# 780-00040_Rev1_Pg1_Super_Sniffer.net
KiCad netlist of a schematic drawn in Altium Designer
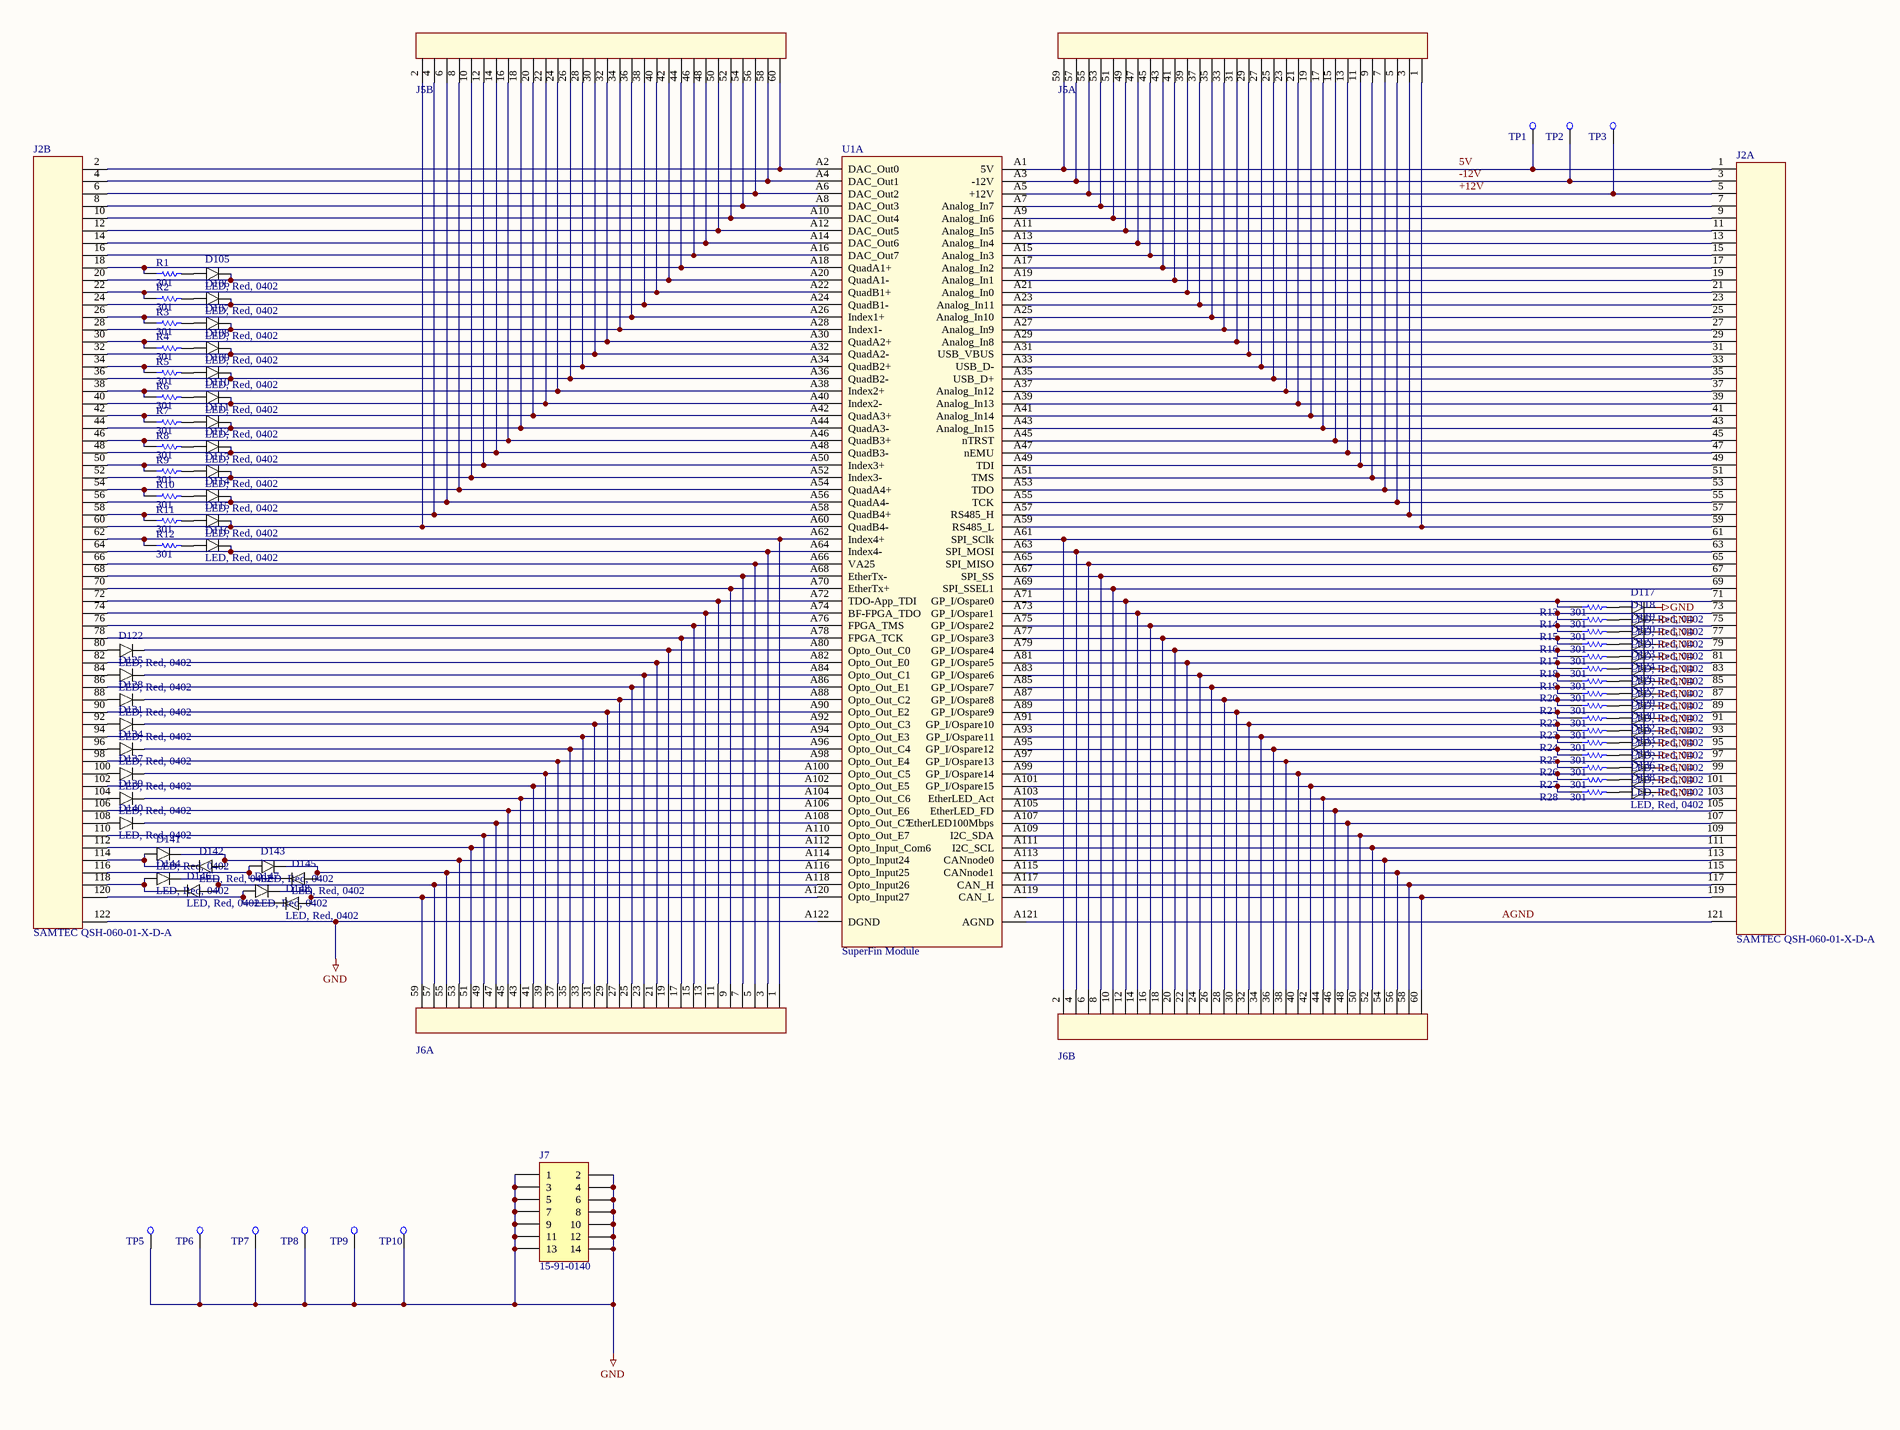
[diagram p0: 780-00040, Rev1, Pg1, Super Sniffer.SchDoc, left]
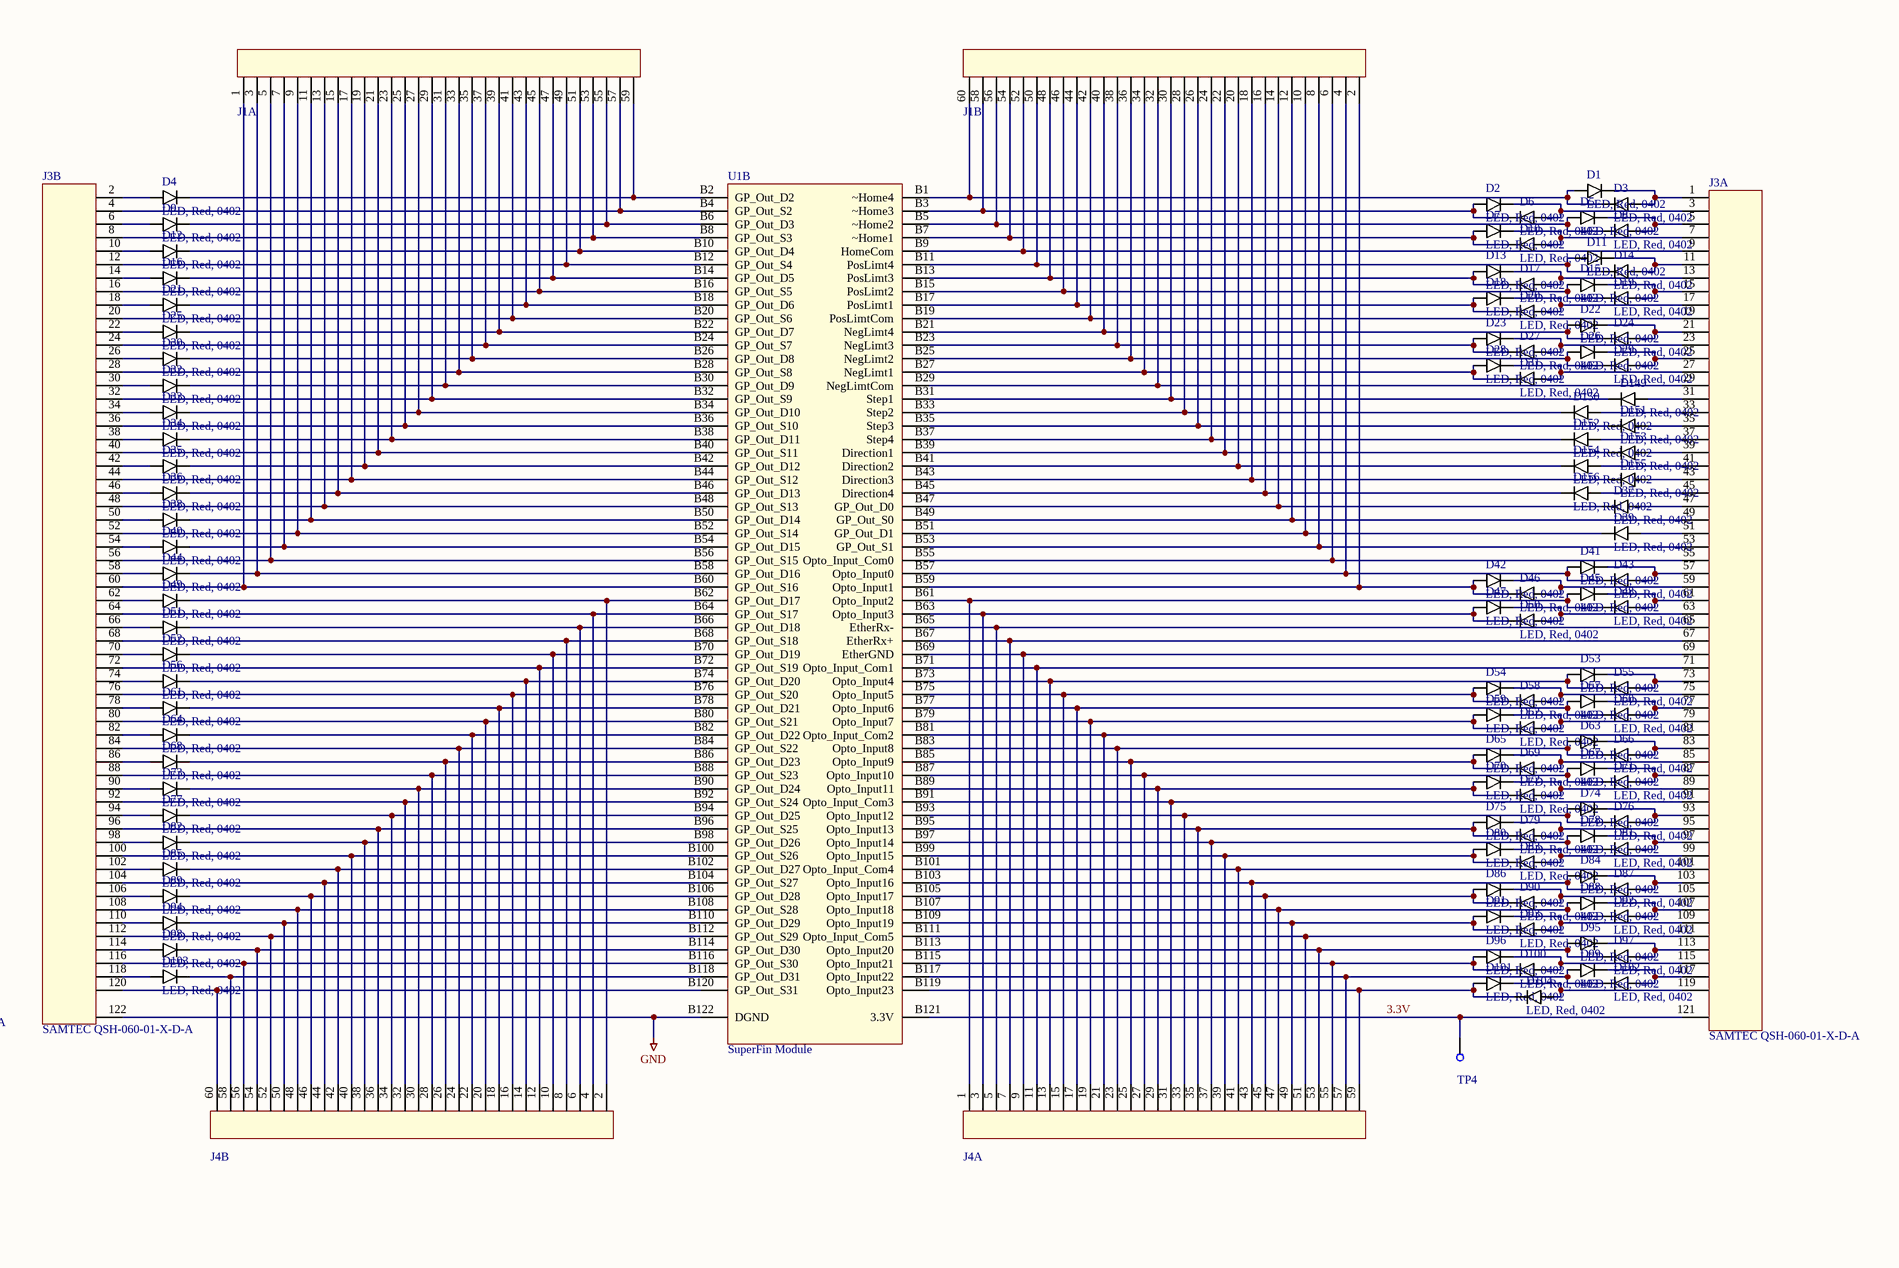
[diagram p1: 780-00040, Rev1, Pg1, Super Sniffer.SchDoc, right]

(export (version "E")
  (design (tool "Eeschema 10.0.6"))
  (components
    (comp (ref "D1")
      (value "LED, Red, 0402")
      (footprint "LED SMD 0402")
      (description "RED LED, 0402 SMD")
      (fields (field (name "MANUFACTURER") "Rohm") (field (name "Comment") "LED SMD 0402"))
      (libsource (lib "Richs Schematic Components") (part "LED SMD 0402"))
    )
    (comp (ref "D2")
      (value "LED, Red, 0402")
      (footprint "LED SMD 0402")
      (description "RED LED, 0402 SMD")
      (fields (field (name "MANUFACTURER") "Rohm") (field (name "Comment") "LED SMD 0402"))
      (libsource (lib "Richs Schematic Components") (part "LED SMD 0402"))
    )
    (comp (ref "D3")
      (value "LED, Red, 0402")
      (footprint "LED SMD 0402")
      (description "RED LED, 0402 SMD")
      (fields (field (name "MANUFACTURER") "Rohm") (field (name "Comment") "LED SMD 0402"))
      (libsource (lib "Richs Schematic Components") (part "LED SMD 0402"))
    )
    (comp (ref "D4")
      (value "LED, Red, 0402")
      (footprint "LED SMD 0402")
      (description "RED LED, 0402 SMD")
      (fields (field (name "MANUFACTURER") "Rohm") (field (name "Comment") "LED SMD 0402"))
      (libsource (lib "Richs Schematic Components") (part "LED SMD 0402"))
    )
    (comp (ref "D5")
      (value "LED, Red, 0402")
      (footprint "LED SMD 0402")
      (description "RED LED, 0402 SMD")
      (fields (field (name "MANUFACTURER") "Rohm") (field (name "Comment") "LED SMD 0402"))
      (libsource (lib "Richs Schematic Components") (part "LED SMD 0402"))
    )
    (comp (ref "D6")
      (value "LED, Red, 0402")
      (footprint "LED SMD 0402")
      (description "RED LED, 0402 SMD")
      (fields (field (name "MANUFACTURER") "Rohm") (field (name "Comment") "LED SMD 0402"))
      (libsource (lib "Richs Schematic Components") (part "LED SMD 0402"))
    )
    (comp (ref "D7")
      (value "LED, Red, 0402")
      (footprint "LED SMD 0402")
      (description "RED LED, 0402 SMD")
      (fields (field (name "MANUFACTURER") "Rohm") (field (name "Comment") "LED SMD 0402"))
      (libsource (lib "Richs Schematic Components") (part "LED SMD 0402"))
    )
    (comp (ref "D8")
      (value "LED, Red, 0402")
      (footprint "LED SMD 0402")
      (description "RED LED, 0402 SMD")
      (fields (field (name "MANUFACTURER") "Rohm") (field (name "Comment") "LED SMD 0402"))
      (libsource (lib "Richs Schematic Components") (part "LED SMD 0402"))
    )
    (comp (ref "D9")
      (value "LED, Red, 0402")
      (footprint "LED SMD 0402")
      (description "RED LED, 0402 SMD")
      (fields (field (name "MANUFACTURER") "Rohm") (field (name "Comment") "LED SMD 0402"))
      (libsource (lib "Richs Schematic Components") (part "LED SMD 0402"))
    )
    (comp (ref "D10")
      (value "LED, Red, 0402")
      (footprint "LED SMD 0402")
      (description "RED LED, 0402 SMD")
      (fields (field (name "MANUFACTURER") "Rohm") (field (name "Comment") "LED SMD 0402"))
      (libsource (lib "Richs Schematic Components") (part "LED SMD 0402"))
    )
    (comp (ref "D11")
      (value "LED, Red, 0402")
      (footprint "LED SMD 0402")
      (description "RED LED, 0402 SMD")
      (fields (field (name "MANUFACTURER") "Rohm") (field (name "Comment") "LED SMD 0402"))
      (libsource (lib "Richs Schematic Components") (part "LED SMD 0402"))
    )
    (comp (ref "D12")
      (value "LED, Red, 0402")
      (footprint "LED SMD 0402")
      (description "RED LED, 0402 SMD")
      (fields (field (name "MANUFACTURER") "Rohm") (field (name "Comment") "LED SMD 0402"))
      (libsource (lib "Richs Schematic Components") (part "LED SMD 0402"))
    )
    (comp (ref "D13")
      (value "LED, Red, 0402")
      (footprint "LED SMD 0402")
      (description "RED LED, 0402 SMD")
      (fields (field (name "MANUFACTURER") "Rohm") (field (name "Comment") "LED SMD 0402"))
      (libsource (lib "Richs Schematic Components") (part "LED SMD 0402"))
    )
    (comp (ref "D14")
      (value "LED, Red, 0402")
      (footprint "LED SMD 0402")
      (description "RED LED, 0402 SMD")
      (fields (field (name "MANUFACTURER") "Rohm") (field (name "Comment") "LED SMD 0402"))
      (libsource (lib "Richs Schematic Components") (part "LED SMD 0402"))
    )
    (comp (ref "D15")
      (value "LED, Red, 0402")
      (footprint "LED SMD 0402")
      (description "RED LED, 0402 SMD")
      (fields (field (name "MANUFACTURER") "Rohm") (field (name "Comment") "LED SMD 0402"))
      (libsource (lib "Richs Schematic Components") (part "LED SMD 0402"))
    )
    (comp (ref "D16")
      (value "LED, Red, 0402")
      (footprint "LED SMD 0402")
      (description "RED LED, 0402 SMD")
      (fields (field (name "MANUFACTURER") "Rohm") (field (name "Comment") "LED SMD 0402"))
      (libsource (lib "Richs Schematic Components") (part "LED SMD 0402"))
    )
    (comp (ref "D17")
      (value "LED, Red, 0402")
      (footprint "LED SMD 0402")
      (description "RED LED, 0402 SMD")
      (fields (field (name "MANUFACTURER") "Rohm") (field (name "Comment") "LED SMD 0402"))
      (libsource (lib "Richs Schematic Components") (part "LED SMD 0402"))
    )
    (comp (ref "D18")
      (value "LED, Red, 0402")
      (footprint "LED SMD 0402")
      (description "RED LED, 0402 SMD")
      (fields (field (name "MANUFACTURER") "Rohm") (field (name "Comment") "LED SMD 0402"))
      (libsource (lib "Richs Schematic Components") (part "LED SMD 0402"))
    )
    (comp (ref "D19")
      (value "LED, Red, 0402")
      (footprint "LED SMD 0402")
      (description "RED LED, 0402 SMD")
      (fields (field (name "MANUFACTURER") "Rohm") (field (name "Comment") "LED SMD 0402"))
      (libsource (lib "Richs Schematic Components") (part "LED SMD 0402"))
    )
    (comp (ref "D20")
      (value "LED, Red, 0402")
      (footprint "LED SMD 0402")
      (description "RED LED, 0402 SMD")
      (fields (field (name "MANUFACTURER") "Rohm") (field (name "Comment") "LED SMD 0402"))
      (libsource (lib "Richs Schematic Components") (part "LED SMD 0402"))
    )
    (comp (ref "D21")
      (value "LED, Red, 0402")
      (footprint "LED SMD 0402")
      (description "RED LED, 0402 SMD")
      (fields (field (name "MANUFACTURER") "Rohm") (field (name "Comment") "LED SMD 0402"))
      (libsource (lib "Richs Schematic Components") (part "LED SMD 0402"))
    )
    (comp (ref "D22")
      (value "LED, Red, 0402")
      (footprint "LED SMD 0402")
      (description "RED LED, 0402 SMD")
      (fields (field (name "MANUFACTURER") "Rohm") (field (name "Comment") "LED SMD 0402"))
      (libsource (lib "Richs Schematic Components") (part "LED SMD 0402"))
    )
    (comp (ref "D23")
      (value "LED, Red, 0402")
      (footprint "LED SMD 0402")
      (description "RED LED, 0402 SMD")
      (fields (field (name "MANUFACTURER") "Rohm") (field (name "Comment") "LED SMD 0402"))
      (libsource (lib "Richs Schematic Components") (part "LED SMD 0402"))
    )
    (comp (ref "D24")
      (value "LED, Red, 0402")
      (footprint "LED SMD 0402")
      (description "RED LED, 0402 SMD")
      (fields (field (name "MANUFACTURER") "Rohm") (field (name "Comment") "LED SMD 0402"))
      (libsource (lib "Richs Schematic Components") (part "LED SMD 0402"))
    )
    (comp (ref "D25")
      (value "LED, Red, 0402")
      (footprint "LED SMD 0402")
      (description "RED LED, 0402 SMD")
      (fields (field (name "MANUFACTURER") "Rohm") (field (name "Comment") "LED SMD 0402"))
      (libsource (lib "Richs Schematic Components") (part "LED SMD 0402"))
    )
    (comp (ref "D26")
      (value "LED, Red, 0402")
      (footprint "LED SMD 0402")
      (description "RED LED, 0402 SMD")
      (fields (field (name "MANUFACTURER") "Rohm") (field (name "Comment") "LED SMD 0402"))
      (libsource (lib "Richs Schematic Components") (part "LED SMD 0402"))
    )
    (comp (ref "D27")
      (value "LED, Red, 0402")
      (footprint "LED SMD 0402")
      (description "RED LED, 0402 SMD")
      (fields (field (name "MANUFACTURER") "Rohm") (field (name "Comment") "LED SMD 0402"))
      (libsource (lib "Richs Schematic Components") (part "LED SMD 0402"))
    )
    (comp (ref "D28")
      (value "LED, Red, 0402")
      (footprint "LED SMD 0402")
      (description "RED LED, 0402 SMD")
      (fields (field (name "MANUFACTURER") "Rohm") (field (name "Comment") "LED SMD 0402"))
      (libsource (lib "Richs Schematic Components") (part "LED SMD 0402"))
    )
    (comp (ref "D29")
      (value "LED, Red, 0402")
      (footprint "LED SMD 0402")
      (description "RED LED, 0402 SMD")
      (fields (field (name "MANUFACTURER") "Rohm") (field (name "Comment") "LED SMD 0402"))
      (libsource (lib "Richs Schematic Components") (part "LED SMD 0402"))
    )
    (comp (ref "D30")
      (value "LED, Red, 0402")
      (footprint "LED SMD 0402")
      (description "RED LED, 0402 SMD")
      (fields (field (name "MANUFACTURER") "Rohm") (field (name "Comment") "LED SMD 0402"))
      (libsource (lib "Richs Schematic Components") (part "LED SMD 0402"))
    )
    (comp (ref "D31")
      (value "LED, Red, 0402")
      (footprint "LED SMD 0402")
      (description "RED LED, 0402 SMD")
      (fields (field (name "MANUFACTURER") "Rohm") (field (name "Comment") "LED SMD 0402"))
      (libsource (lib "Richs Schematic Components") (part "LED SMD 0402"))
    )
    (comp (ref "D32")
      (value "LED, Red, 0402")
      (footprint "LED SMD 0402")
      (description "RED LED, 0402 SMD")
      (fields (field (name "MANUFACTURER") "Rohm") (field (name "Comment") "LED SMD 0402"))
      (libsource (lib "Richs Schematic Components") (part "LED SMD 0402"))
    )
    (comp (ref "D33")
      (value "LED, Red, 0402")
      (footprint "LED SMD 0402")
      (description "RED LED, 0402 SMD")
      (fields (field (name "MANUFACTURER") "Rohm") (field (name "Comment") "LED SMD 0402"))
      (libsource (lib "Richs Schematic Components") (part "LED SMD 0402"))
    )
    (comp (ref "D34")
      (value "LED, Red, 0402")
      (footprint "LED SMD 0402")
      (description "RED LED, 0402 SMD")
      (fields (field (name "MANUFACTURER") "Rohm") (field (name "Comment") "LED SMD 0402"))
      (libsource (lib "Richs Schematic Components") (part "LED SMD 0402"))
    )
    (comp (ref "D35")
      (value "LED, Red, 0402")
      (footprint "LED SMD 0402")
      (description "RED LED, 0402 SMD")
      (fields (field (name "MANUFACTURER") "Rohm") (field (name "Comment") "LED SMD 0402"))
      (libsource (lib "Richs Schematic Components") (part "LED SMD 0402"))
    )
    (comp (ref "D36")
      (value "LED, Red, 0402")
      (footprint "LED SMD 0402")
      (description "RED LED, 0402 SMD")
      (fields (field (name "MANUFACTURER") "Rohm") (field (name "Comment") "LED SMD 0402"))
      (libsource (lib "Richs Schematic Components") (part "LED SMD 0402"))
    )
    (comp (ref "D37")
      (value "LED, Red, 0402")
      (footprint "LED SMD 0402")
      (description "RED LED, 0402 SMD")
      (fields (field (name "MANUFACTURER") "Rohm") (field (name "Comment") "LED SMD 0402"))
      (libsource (lib "Richs Schematic Components") (part "LED SMD 0402"))
    )
    (comp (ref "D38")
      (value "LED, Red, 0402")
      (footprint "LED SMD 0402")
      (description "RED LED, 0402 SMD")
      (fields (field (name "MANUFACTURER") "Rohm") (field (name "Comment") "LED SMD 0402"))
      (libsource (lib "Richs Schematic Components") (part "LED SMD 0402"))
    )
    (comp (ref "D39")
      (value "LED, Red, 0402")
      (footprint "LED SMD 0402")
      (description "RED LED, 0402 SMD")
      (fields (field (name "MANUFACTURER") "Rohm") (field (name "Comment") "LED SMD 0402"))
      (libsource (lib "Richs Schematic Components") (part "LED SMD 0402"))
    )
    (comp (ref "D40")
      (value "LED, Red, 0402")
      (footprint "LED SMD 0402")
      (description "RED LED, 0402 SMD")
      (fields (field (name "MANUFACTURER") "Rohm") (field (name "Comment") "LED SMD 0402"))
      (libsource (lib "Richs Schematic Components") (part "LED SMD 0402"))
    )
    (comp (ref "D41")
      (value "LED, Red, 0402")
      (footprint "LED SMD 0402")
      (description "RED LED, 0402 SMD")
      (fields (field (name "MANUFACTURER") "Rohm") (field (name "Comment") "LED SMD 0402"))
      (libsource (lib "Richs Schematic Components") (part "LED SMD 0402"))
    )
    (comp (ref "D42")
      (value "LED, Red, 0402")
      (footprint "LED SMD 0402")
      (description "RED LED, 0402 SMD")
      (fields (field (name "MANUFACTURER") "Rohm") (field (name "Comment") "LED SMD 0402"))
      (libsource (lib "Richs Schematic Components") (part "LED SMD 0402"))
    )
    (comp (ref "D43")
      (value "LED, Red, 0402")
      (footprint "LED SMD 0402")
      (description "RED LED, 0402 SMD")
      (fields (field (name "MANUFACTURER") "Rohm") (field (name "Comment") "LED SMD 0402"))
      (libsource (lib "Richs Schematic Components") (part "LED SMD 0402"))
    )
    (comp (ref "D44")
      (value "LED, Red, 0402")
      (footprint "LED SMD 0402")
      (description "RED LED, 0402 SMD")
      (fields (field (name "MANUFACTURER") "Rohm") (field (name "Comment") "LED SMD 0402"))
      (libsource (lib "Richs Schematic Components") (part "LED SMD 0402"))
    )
    (comp (ref "D45")
      (value "LED, Red, 0402")
      (footprint "LED SMD 0402")
      (description "RED LED, 0402 SMD")
      (fields (field (name "MANUFACTURER") "Rohm") (field (name "Comment") "LED SMD 0402"))
      (libsource (lib "Richs Schematic Components") (part "LED SMD 0402"))
    )
    (comp (ref "D46")
      (value "LED, Red, 0402")
      (footprint "LED SMD 0402")
      (description "RED LED, 0402 SMD")
      (fields (field (name "MANUFACTURER") "Rohm") (field (name "Comment") "LED SMD 0402"))
      (libsource (lib "Richs Schematic Components") (part "LED SMD 0402"))
    )
    (comp (ref "D47")
      (value "LED, Red, 0402")
      (footprint "LED SMD 0402")
      (description "RED LED, 0402 SMD")
      (fields (field (name "MANUFACTURER") "Rohm") (field (name "Comment") "LED SMD 0402"))
      (libsource (lib "Richs Schematic Components") (part "LED SMD 0402"))
    )
    (comp (ref "D48")
      (value "LED, Red, 0402")
      (footprint "LED SMD 0402")
      (description "RED LED, 0402 SMD")
      (fields (field (name "MANUFACTURER") "Rohm") (field (name "Comment") "LED SMD 0402"))
      (libsource (lib "Richs Schematic Components") (part "LED SMD 0402"))
    )
    (comp (ref "D49")
      (value "LED, Red, 0402")
      (footprint "LED SMD 0402")
      (description "RED LED, 0402 SMD")
      (fields (field (name "MANUFACTURER") "Rohm") (field (name "Comment") "LED SMD 0402"))
      (libsource (lib "Richs Schematic Components") (part "LED SMD 0402"))
    )
    (comp (ref "D50")
      (value "LED, Red, 0402")
      (footprint "LED SMD 0402")
      (description "RED LED, 0402 SMD")
      (fields (field (name "MANUFACTURER") "Rohm") (field (name "Comment") "LED SMD 0402"))
      (libsource (lib "Richs Schematic Components") (part "LED SMD 0402"))
    )
    (comp (ref "D51")
      (value "LED, Red, 0402")
      (footprint "LED SMD 0402")
      (description "RED LED, 0402 SMD")
      (fields (field (name "MANUFACTURER") "Rohm") (field (name "Comment") "LED SMD 0402"))
      (libsource (lib "Richs Schematic Components") (part "LED SMD 0402"))
    )
    (comp (ref "D52")
      (value "LED, Red, 0402")
      (footprint "LED SMD 0402")
      (description "RED LED, 0402 SMD")
      (fields (field (name "MANUFACTURER") "Rohm") (field (name "Comment") "LED SMD 0402"))
      (libsource (lib "Richs Schematic Components") (part "LED SMD 0402"))
    )
    (comp (ref "D53")
      (value "LED, Red, 0402")
      (footprint "LED SMD 0402")
      (description "RED LED, 0402 SMD")
      (fields (field (name "MANUFACTURER") "Rohm") (field (name "Comment") "LED SMD 0402"))
      (libsource (lib "Richs Schematic Components") (part "LED SMD 0402"))
    )
    (comp (ref "D54")
      (value "LED, Red, 0402")
      (footprint "LED SMD 0402")
      (description "RED LED, 0402 SMD")
      (fields (field (name "MANUFACTURER") "Rohm") (field (name "Comment") "LED SMD 0402"))
      (libsource (lib "Richs Schematic Components") (part "LED SMD 0402"))
    )
    (comp (ref "D55")
      (value "LED, Red, 0402")
      (footprint "LED SMD 0402")
      (description "RED LED, 0402 SMD")
      (fields (field (name "MANUFACTURER") "Rohm") (field (name "Comment") "LED SMD 0402"))
      (libsource (lib "Richs Schematic Components") (part "LED SMD 0402"))
    )
    (comp (ref "D56")
      (value "LED, Red, 0402")
      (footprint "LED SMD 0402")
      (description "RED LED, 0402 SMD")
      (fields (field (name "MANUFACTURER") "Rohm") (field (name "Comment") "LED SMD 0402"))
      (libsource (lib "Richs Schematic Components") (part "LED SMD 0402"))
    )
    (comp (ref "D57")
      (value "LED, Red, 0402")
      (footprint "LED SMD 0402")
      (description "RED LED, 0402 SMD")
      (fields (field (name "MANUFACTURER") "Rohm") (field (name "Comment") "LED SMD 0402"))
      (libsource (lib "Richs Schematic Components") (part "LED SMD 0402"))
    )
    (comp (ref "D58")
      (value "LED, Red, 0402")
      (footprint "LED SMD 0402")
      (description "RED LED, 0402 SMD")
      (fields (field (name "MANUFACTURER") "Rohm") (field (name "Comment") "LED SMD 0402"))
      (libsource (lib "Richs Schematic Components") (part "LED SMD 0402"))
    )
    (comp (ref "D59")
      (value "LED, Red, 0402")
      (footprint "LED SMD 0402")
      (description "RED LED, 0402 SMD")
      (fields (field (name "MANUFACTURER") "Rohm") (field (name "Comment") "LED SMD 0402"))
      (libsource (lib "Richs Schematic Components") (part "LED SMD 0402"))
    )
    (comp (ref "D60")
      (value "LED, Red, 0402")
      (footprint "LED SMD 0402")
      (description "RED LED, 0402 SMD")
      (fields (field (name "MANUFACTURER") "Rohm") (field (name "Comment") "LED SMD 0402"))
      (libsource (lib "Richs Schematic Components") (part "LED SMD 0402"))
    )
    (comp (ref "D61")
      (value "LED, Red, 0402")
      (footprint "LED SMD 0402")
      (description "RED LED, 0402 SMD")
      (fields (field (name "MANUFACTURER") "Rohm") (field (name "Comment") "LED SMD 0402"))
      (libsource (lib "Richs Schematic Components") (part "LED SMD 0402"))
    )
    (comp (ref "D62")
      (value "LED, Red, 0402")
      (footprint "LED SMD 0402")
      (description "RED LED, 0402 SMD")
      (fields (field (name "MANUFACTURER") "Rohm") (field (name "Comment") "LED SMD 0402"))
      (libsource (lib "Richs Schematic Components") (part "LED SMD 0402"))
    )
    (comp (ref "D63")
      (value "LED, Red, 0402")
      (footprint "LED SMD 0402")
      (description "RED LED, 0402 SMD")
      (fields (field (name "MANUFACTURER") "Rohm") (field (name "Comment") "LED SMD 0402"))
      (libsource (lib "Richs Schematic Components") (part "LED SMD 0402"))
    )
    (comp (ref "D64")
      (value "LED, Red, 0402")
      (footprint "LED SMD 0402")
      (description "RED LED, 0402 SMD")
      (fields (field (name "MANUFACTURER") "Rohm") (field (name "Comment") "LED SMD 0402"))
      (libsource (lib "Richs Schematic Components") (part "LED SMD 0402"))
    )
    (comp (ref "D65")
      (value "LED, Red, 0402")
      (footprint "LED SMD 0402")
      (description "RED LED, 0402 SMD")
      (fields (field (name "MANUFACTURER") "Rohm") (field (name "Comment") "LED SMD 0402"))
      (libsource (lib "Richs Schematic Components") (part "LED SMD 0402"))
    )
    (comp (ref "D66")
      (value "LED, Red, 0402")
      (footprint "LED SMD 0402")
      (description "RED LED, 0402 SMD")
      (fields (field (name "MANUFACTURER") "Rohm") (field (name "Comment") "LED SMD 0402"))
      (libsource (lib "Richs Schematic Components") (part "LED SMD 0402"))
    )
    (comp (ref "D67")
      (value "LED, Red, 0402")
      (footprint "LED SMD 0402")
      (description "RED LED, 0402 SMD")
      (fields (field (name "MANUFACTURER") "Rohm") (field (name "Comment") "LED SMD 0402"))
      (libsource (lib "Richs Schematic Components") (part "LED SMD 0402"))
    )
    (comp (ref "D68")
      (value "LED, Red, 0402")
      (footprint "LED SMD 0402")
      (description "RED LED, 0402 SMD")
      (fields (field (name "MANUFACTURER") "Rohm") (field (name "Comment") "LED SMD 0402"))
      (libsource (lib "Richs Schematic Components") (part "LED SMD 0402"))
    )
    (comp (ref "D69")
      (value "LED, Red, 0402")
      (footprint "LED SMD 0402")
      (description "RED LED, 0402 SMD")
      (fields (field (name "MANUFACTURER") "Rohm") (field (name "Comment") "LED SMD 0402"))
      (libsource (lib "Richs Schematic Components") (part "LED SMD 0402"))
    )
    (comp (ref "D70")
      (value "LED, Red, 0402")
      (footprint "LED SMD 0402")
      (description "RED LED, 0402 SMD")
      (fields (field (name "MANUFACTURER") "Rohm") (field (name "Comment") "LED SMD 0402"))
      (libsource (lib "Richs Schematic Components") (part "LED SMD 0402"))
    )
    (comp (ref "D71")
      (value "LED, Red, 0402")
      (footprint "LED SMD 0402")
      (description "RED LED, 0402 SMD")
      (fields (field (name "MANUFACTURER") "Rohm") (field (name "Comment") "LED SMD 0402"))
      (libsource (lib "Richs Schematic Components") (part "LED SMD 0402"))
    )
    (comp (ref "D72")
      (value "LED, Red, 0402")
      (footprint "LED SMD 0402")
      (description "RED LED, 0402 SMD")
      (fields (field (name "MANUFACTURER") "Rohm") (field (name "Comment") "LED SMD 0402"))
      (libsource (lib "Richs Schematic Components") (part "LED SMD 0402"))
    )
    (comp (ref "D73")
      (value "LED, Red, 0402")
      (footprint "LED SMD 0402")
      (description "RED LED, 0402 SMD")
      (fields (field (name "MANUFACTURER") "Rohm") (field (name "Comment") "LED SMD 0402"))
      (libsource (lib "Richs Schematic Components") (part "LED SMD 0402"))
    )
    (comp (ref "D74")
      (value "LED, Red, 0402")
      (footprint "LED SMD 0402")
      (description "RED LED, 0402 SMD")
      (fields (field (name "MANUFACTURER") "Rohm") (field (name "Comment") "LED SMD 0402"))
      (libsource (lib "Richs Schematic Components") (part "LED SMD 0402"))
    )
    (comp (ref "D75")
      (value "LED, Red, 0402")
      (footprint "LED SMD 0402")
      (description "RED LED, 0402 SMD")
      (fields (field (name "MANUFACTURER") "Rohm") (field (name "Comment") "LED SMD 0402"))
      (libsource (lib "Richs Schematic Components") (part "LED SMD 0402"))
    )
    (comp (ref "D76")
      (value "LED, Red, 0402")
      (footprint "LED SMD 0402")
      (description "RED LED, 0402 SMD")
      (fields (field (name "MANUFACTURER") "Rohm") (field (name "Comment") "LED SMD 0402"))
      (libsource (lib "Richs Schematic Components") (part "LED SMD 0402"))
    )
    (comp (ref "D77")
      (value "LED, Red, 0402")
      (footprint "LED SMD 0402")
      (description "RED LED, 0402 SMD")
      (fields (field (name "MANUFACTURER") "Rohm") (field (name "Comment") "LED SMD 0402"))
      (libsource (lib "Richs Schematic Components") (part "LED SMD 0402"))
    )
    (comp (ref "D78")
      (value "LED, Red, 0402")
      (footprint "LED SMD 0402")
      (description "RED LED, 0402 SMD")
      (fields (field (name "MANUFACTURER") "Rohm") (field (name "Comment") "LED SMD 0402"))
      (libsource (lib "Richs Schematic Components") (part "LED SMD 0402"))
    )
    (comp (ref "D79")
      (value "LED, Red, 0402")
      (footprint "LED SMD 0402")
      (description "RED LED, 0402 SMD")
      (fields (field (name "MANUFACTURER") "Rohm") (field (name "Comment") "LED SMD 0402"))
      (libsource (lib "Richs Schematic Components") (part "LED SMD 0402"))
    )
    (comp (ref "D80")
      (value "LED, Red, 0402")
      (footprint "LED SMD 0402")
      (description "RED LED, 0402 SMD")
      (fields (field (name "MANUFACTURER") "Rohm") (field (name "Comment") "LED SMD 0402"))
      (libsource (lib "Richs Schematic Components") (part "LED SMD 0402"))
    )
    (comp (ref "D81")
      (value "LED, Red, 0402")
      (footprint "LED SMD 0402")
      (description "RED LED, 0402 SMD")
      (fields (field (name "MANUFACTURER") "Rohm") (field (name "Comment") "LED SMD 0402"))
      (libsource (lib "Richs Schematic Components") (part "LED SMD 0402"))
    )
    (comp (ref "D82")
      (value "LED, Red, 0402")
      (footprint "LED SMD 0402")
      (description "RED LED, 0402 SMD")
      (fields (field (name "MANUFACTURER") "Rohm") (field (name "Comment") "LED SMD 0402"))
      (libsource (lib "Richs Schematic Components") (part "LED SMD 0402"))
    )
    (comp (ref "D83")
      (value "LED, Red, 0402")
      (footprint "LED SMD 0402")
      (description "RED LED, 0402 SMD")
      (fields (field (name "MANUFACTURER") "Rohm") (field (name "Comment") "LED SMD 0402"))
      (libsource (lib "Richs Schematic Components") (part "LED SMD 0402"))
    )
    (comp (ref "D84")
      (value "LED, Red, 0402")
      (footprint "LED SMD 0402")
      (description "RED LED, 0402 SMD")
      (fields (field (name "MANUFACTURER") "Rohm") (field (name "Comment") "LED SMD 0402"))
      (libsource (lib "Richs Schematic Components") (part "LED SMD 0402"))
    )
    (comp (ref "D85")
      (value "LED, Red, 0402")
      (footprint "LED SMD 0402")
      (description "RED LED, 0402 SMD")
      (fields (field (name "MANUFACTURER") "Rohm") (field (name "Comment") "LED SMD 0402"))
      (libsource (lib "Richs Schematic Components") (part "LED SMD 0402"))
    )
    (comp (ref "D86")
      (value "LED, Red, 0402")
      (footprint "LED SMD 0402")
      (description "RED LED, 0402 SMD")
      (fields (field (name "MANUFACTURER") "Rohm") (field (name "Comment") "LED SMD 0402"))
      (libsource (lib "Richs Schematic Components") (part "LED SMD 0402"))
    )
    (comp (ref "D87")
      (value "LED, Red, 0402")
      (footprint "LED SMD 0402")
      (description "RED LED, 0402 SMD")
      (fields (field (name "MANUFACTURER") "Rohm") (field (name "Comment") "LED SMD 0402"))
      (libsource (lib "Richs Schematic Components") (part "LED SMD 0402"))
    )
    (comp (ref "D88")
      (value "LED, Red, 0402")
      (footprint "LED SMD 0402")
      (description "RED LED, 0402 SMD")
      (fields (field (name "MANUFACTURER") "Rohm") (field (name "Comment") "LED SMD 0402"))
      (libsource (lib "Richs Schematic Components") (part "LED SMD 0402"))
    )
    (comp (ref "D89")
      (value "LED, Red, 0402")
      (footprint "LED SMD 0402")
      (description "RED LED, 0402 SMD")
      (fields (field (name "MANUFACTURER") "Rohm") (field (name "Comment") "LED SMD 0402"))
      (libsource (lib "Richs Schematic Components") (part "LED SMD 0402"))
    )
    (comp (ref "D90")
      (value "LED, Red, 0402")
      (footprint "LED SMD 0402")
      (description "RED LED, 0402 SMD")
      (fields (field (name "MANUFACTURER") "Rohm") (field (name "Comment") "LED SMD 0402"))
      (libsource (lib "Richs Schematic Components") (part "LED SMD 0402"))
    )
    (comp (ref "D91")
      (value "LED, Red, 0402")
      (footprint "LED SMD 0402")
      (description "RED LED, 0402 SMD")
      (fields (field (name "MANUFACTURER") "Rohm") (field (name "Comment") "LED SMD 0402"))
      (libsource (lib "Richs Schematic Components") (part "LED SMD 0402"))
    )
    (comp (ref "D92")
      (value "LED, Red, 0402")
      (footprint "LED SMD 0402")
      (description "RED LED, 0402 SMD")
      (fields (field (name "MANUFACTURER") "Rohm") (field (name "Comment") "LED SMD 0402"))
      (libsource (lib "Richs Schematic Components") (part "LED SMD 0402"))
    )
    (comp (ref "D93")
      (value "LED, Red, 0402")
      (footprint "LED SMD 0402")
      (description "RED LED, 0402 SMD")
      (fields (field (name "MANUFACTURER") "Rohm") (field (name "Comment") "LED SMD 0402"))
      (libsource (lib "Richs Schematic Components") (part "LED SMD 0402"))
    )
    (comp (ref "D94")
      (value "LED, Red, 0402")
      (footprint "LED SMD 0402")
      (description "RED LED, 0402 SMD")
      (fields (field (name "MANUFACTURER") "Rohm") (field (name "Comment") "LED SMD 0402"))
      (libsource (lib "Richs Schematic Components") (part "LED SMD 0402"))
    )
    (comp (ref "D95")
      (value "LED, Red, 0402")
      (footprint "LED SMD 0402")
      (description "RED LED, 0402 SMD")
      (fields (field (name "MANUFACTURER") "Rohm") (field (name "Comment") "LED SMD 0402"))
      (libsource (lib "Richs Schematic Components") (part "LED SMD 0402"))
    )
    (comp (ref "D96")
      (value "LED, Red, 0402")
      (footprint "LED SMD 0402")
      (description "RED LED, 0402 SMD")
      (fields (field (name "MANUFACTURER") "Rohm") (field (name "Comment") "LED SMD 0402"))
      (libsource (lib "Richs Schematic Components") (part "LED SMD 0402"))
    )
    (comp (ref "D97")
      (value "LED, Red, 0402")
      (footprint "LED SMD 0402")
      (description "RED LED, 0402 SMD")
      (fields (field (name "MANUFACTURER") "Rohm") (field (name "Comment") "LED SMD 0402"))
      (libsource (lib "Richs Schematic Components") (part "LED SMD 0402"))
    )
    (comp (ref "D98")
      (value "LED, Red, 0402")
      (footprint "LED SMD 0402")
      (description "RED LED, 0402 SMD")
      (fields (field (name "MANUFACTURER") "Rohm") (field (name "Comment") "LED SMD 0402"))
      (libsource (lib "Richs Schematic Components") (part "LED SMD 0402"))
    )
    (comp (ref "D99")
      (value "LED, Red, 0402")
      (footprint "LED SMD 0402")
      (description "RED LED, 0402 SMD")
      (fields (field (name "MANUFACTURER") "Rohm") (field (name "Comment") "LED SMD 0402"))
      (libsource (lib "Richs Schematic Components") (part "LED SMD 0402"))
    )
    (comp (ref "D100")
      (value "LED, Red, 0402")
      (footprint "LED SMD 0402")
      (description "RED LED, 0402 SMD")
      (fields (field (name "MANUFACTURER") "Rohm") (field (name "Comment") "LED SMD 0402"))
      (libsource (lib "Richs Schematic Components") (part "LED SMD 0402"))
    )
    (comp (ref "D101")
      (value "LED, Red, 0402")
      (footprint "LED SMD 0402")
      (description "RED LED, 0402 SMD")
      (fields (field (name "MANUFACTURER") "Rohm") (field (name "Comment") "LED SMD 0402"))
      (libsource (lib "Richs Schematic Components") (part "LED SMD 0402"))
    )
    (comp (ref "D102")
      (value "LED, Red, 0402")
      (footprint "LED SMD 0402")
      (description "RED LED, 0402 SMD")
      (fields (field (name "MANUFACTURER") "Rohm") (field (name "Comment") "LED SMD 0402"))
      (libsource (lib "Richs Schematic Components") (part "LED SMD 0402"))
    )
    (comp (ref "D103")
      (value "LED, Red, 0402")
      (footprint "LED SMD 0402")
      (description "RED LED, 0402 SMD")
      (fields (field (name "MANUFACTURER") "Rohm") (field (name "Comment") "LED SMD 0402"))
      (libsource (lib "Richs Schematic Components") (part "LED SMD 0402"))
    )
    (comp (ref "D104")
      (value "LED, Red, 0402")
      (footprint "LED SMD 0402")
      (description "RED LED, 0402 SMD")
      (fields (field (name "MANUFACTURER") "Rohm") (field (name "Comment") "LED SMD 0402"))
      (libsource (lib "Richs Schematic Components") (part "LED SMD 0402"))
    )
    (comp (ref "D105")
      (value "LED, Red, 0402")
      (footprint "LED SMD 0402")
      (description "RED LED, 0402 SMD")
      (fields (field (name "MANUFACTURER") "Rohm") (field (name "Comment") "LED SMD 0402"))
      (libsource (lib "Richs Schematic Components") (part "LED SMD 0402"))
    )
    (comp (ref "D106")
      (value "LED, Red, 0402")
      (footprint "LED SMD 0402")
      (description "RED LED, 0402 SMD")
      (fields (field (name "MANUFACTURER") "Rohm") (field (name "Comment") "LED SMD 0402"))
      (libsource (lib "Richs Schematic Components") (part "LED SMD 0402"))
    )
    (comp (ref "D107")
      (value "LED, Red, 0402")
      (footprint "LED SMD 0402")
      (description "RED LED, 0402 SMD")
      (fields (field (name "MANUFACTURER") "Rohm") (field (name "Comment") "LED SMD 0402"))
      (libsource (lib "Richs Schematic Components") (part "LED SMD 0402"))
    )
    (comp (ref "D108")
      (value "LED, Red, 0402")
      (footprint "LED SMD 0402")
      (description "RED LED, 0402 SMD")
      (fields (field (name "MANUFACTURER") "Rohm") (field (name "Comment") "LED SMD 0402"))
      (libsource (lib "Richs Schematic Components") (part "LED SMD 0402"))
    )
    (comp (ref "D109")
      (value "LED, Red, 0402")
      (footprint "LED SMD 0402")
      (description "RED LED, 0402 SMD")
      (fields (field (name "MANUFACTURER") "Rohm") (field (name "Comment") "LED SMD 0402"))
      (libsource (lib "Richs Schematic Components") (part "LED SMD 0402"))
    )
    (comp (ref "D110")
      (value "LED, Red, 0402")
      (footprint "LED SMD 0402")
      (description "RED LED, 0402 SMD")
      (fields (field (name "MANUFACTURER") "Rohm") (field (name "Comment") "LED SMD 0402"))
      (libsource (lib "Richs Schematic Components") (part "LED SMD 0402"))
    )
    (comp (ref "D111")
      (value "LED, Red, 0402")
      (footprint "LED SMD 0402")
      (description "RED LED, 0402 SMD")
      (fields (field (name "MANUFACTURER") "Rohm") (field (name "Comment") "LED SMD 0402"))
      (libsource (lib "Richs Schematic Components") (part "LED SMD 0402"))
    )
    (comp (ref "D112")
      (value "LED, Red, 0402")
      (footprint "LED SMD 0402")
      (description "RED LED, 0402 SMD")
      (fields (field (name "MANUFACTURER") "Rohm") (field (name "Comment") "LED SMD 0402"))
      (libsource (lib "Richs Schematic Components") (part "LED SMD 0402"))
    )
    (comp (ref "D113")
      (value "LED, Red, 0402")
      (footprint "LED SMD 0402")
      (description "RED LED, 0402 SMD")
      (fields (field (name "MANUFACTURER") "Rohm") (field (name "Comment") "LED SMD 0402"))
      (libsource (lib "Richs Schematic Components") (part "LED SMD 0402"))
    )
    (comp (ref "D114")
      (value "LED, Red, 0402")
      (footprint "LED SMD 0402")
      (description "RED LED, 0402 SMD")
      (fields (field (name "MANUFACTURER") "Rohm") (field (name "Comment") "LED SMD 0402"))
      (libsource (lib "Richs Schematic Components") (part "LED SMD 0402"))
    )
    (comp (ref "D115")
      (value "LED, Red, 0402")
      (footprint "LED SMD 0402")
      (description "RED LED, 0402 SMD")
      (fields (field (name "MANUFACTURER") "Rohm") (field (name "Comment") "LED SMD 0402"))
      (libsource (lib "Richs Schematic Components") (part "LED SMD 0402"))
    )
    (comp (ref "D116")
      (value "LED, Red, 0402")
      (footprint "LED SMD 0402")
      (description "RED LED, 0402 SMD")
      (fields (field (name "MANUFACTURER") "Rohm") (field (name "Comment") "LED SMD 0402"))
      (libsource (lib "Richs Schematic Components") (part "LED SMD 0402"))
    )
    (comp (ref "D117")
      (value "LED, Red, 0402")
      (footprint "LED SMD 0402")
      (description "RED LED, 0402 SMD")
      (fields (field (name "MANUFACTURER") "Rohm") (field (name "Comment") "LED SMD 0402"))
      (libsource (lib "Richs Schematic Components") (part "LED SMD 0402"))
    )
    (comp (ref "D118")
      (value "LED, Red, 0402")
      (footprint "LED SMD 0402")
      (description "RED LED, 0402 SMD")
      (fields (field (name "MANUFACTURER") "Rohm") (field (name "Comment") "LED SMD 0402"))
      (libsource (lib "Richs Schematic Components") (part "LED SMD 0402"))
    )
    (comp (ref "D119")
      (value "LED, Red, 0402")
      (footprint "LED SMD 0402")
      (description "RED LED, 0402 SMD")
      (fields (field (name "MANUFACTURER") "Rohm") (field (name "Comment") "LED SMD 0402"))
      (libsource (lib "Richs Schematic Components") (part "LED SMD 0402"))
    )
    (comp (ref "D120")
      (value "LED, Red, 0402")
      (footprint "LED SMD 0402")
      (description "RED LED, 0402 SMD")
      (fields (field (name "MANUFACTURER") "Rohm") (field (name "Comment") "LED SMD 0402"))
      (libsource (lib "Richs Schematic Components") (part "LED SMD 0402"))
    )
    (comp (ref "D121")
      (value "LED, Red, 0402")
      (footprint "LED SMD 0402")
      (description "RED LED, 0402 SMD")
      (fields (field (name "MANUFACTURER") "Rohm") (field (name "Comment") "LED SMD 0402"))
      (libsource (lib "Richs Schematic Components") (part "LED SMD 0402"))
    )
    (comp (ref "D122")
      (value "LED, Red, 0402")
      (footprint "LED SMD 0402")
      (description "RED LED, 0402 SMD")
      (fields (field (name "MANUFACTURER") "Rohm") (field (name "Comment") "LED SMD 0402"))
      (libsource (lib "Richs Schematic Components") (part "LED SMD 0402"))
    )
    (comp (ref "D123")
      (value "LED, Red, 0402")
      (footprint "LED SMD 0402")
      (description "RED LED, 0402 SMD")
      (fields (field (name "MANUFACTURER") "Rohm") (field (name "Comment") "LED SMD 0402"))
      (libsource (lib "Richs Schematic Components") (part "LED SMD 0402"))
    )
    (comp (ref "D124")
      (value "LED, Red, 0402")
      (footprint "LED SMD 0402")
      (description "RED LED, 0402 SMD")
      (fields (field (name "MANUFACTURER") "Rohm") (field (name "Comment") "LED SMD 0402"))
      (libsource (lib "Richs Schematic Components") (part "LED SMD 0402"))
    )
    (comp (ref "D125")
      (value "LED, Red, 0402")
      (footprint "LED SMD 0402")
      (description "RED LED, 0402 SMD")
      (fields (field (name "MANUFACTURER") "Rohm") (field (name "Comment") "LED SMD 0402"))
      (libsource (lib "Richs Schematic Components") (part "LED SMD 0402"))
    )
    (comp (ref "D126")
      (value "LED, Red, 0402")
      (footprint "LED SMD 0402")
      (description "RED LED, 0402 SMD")
      (fields (field (name "MANUFACTURER") "Rohm") (field (name "Comment") "LED SMD 0402"))
      (libsource (lib "Richs Schematic Components") (part "LED SMD 0402"))
    )
    (comp (ref "D127")
      (value "LED, Red, 0402")
      (footprint "LED SMD 0402")
      (description "RED LED, 0402 SMD")
      (fields (field (name "MANUFACTURER") "Rohm") (field (name "Comment") "LED SMD 0402"))
      (libsource (lib "Richs Schematic Components") (part "LED SMD 0402"))
    )
    (comp (ref "D128")
      (value "LED, Red, 0402")
      (footprint "LED SMD 0402")
      (description "RED LED, 0402 SMD")
      (fields (field (name "MANUFACTURER") "Rohm") (field (name "Comment") "LED SMD 0402"))
      (libsource (lib "Richs Schematic Components") (part "LED SMD 0402"))
    )
    (comp (ref "D129")
      (value "LED, Red, 0402")
      (footprint "LED SMD 0402")
      (description "RED LED, 0402 SMD")
      (fields (field (name "MANUFACTURER") "Rohm") (field (name "Comment") "LED SMD 0402"))
      (libsource (lib "Richs Schematic Components") (part "LED SMD 0402"))
    )
    (comp (ref "D130")
      (value "LED, Red, 0402")
      (footprint "LED SMD 0402")
      (description "RED LED, 0402 SMD")
      (fields (field (name "MANUFACTURER") "Rohm") (field (name "Comment") "LED SMD 0402"))
      (libsource (lib "Richs Schematic Components") (part "LED SMD 0402"))
    )
    (comp (ref "D131")
      (value "LED, Red, 0402")
      (footprint "LED SMD 0402")
      (description "RED LED, 0402 SMD")
      (fields (field (name "MANUFACTURER") "Rohm") (field (name "Comment") "LED SMD 0402"))
      (libsource (lib "Richs Schematic Components") (part "LED SMD 0402"))
    )
    (comp (ref "D132")
      (value "LED, Red, 0402")
      (footprint "LED SMD 0402")
      (description "RED LED, 0402 SMD")
      (fields (field (name "MANUFACTURER") "Rohm") (field (name "Comment") "LED SMD 0402"))
      (libsource (lib "Richs Schematic Components") (part "LED SMD 0402"))
    )
    (comp (ref "D133")
      (value "LED, Red, 0402")
      (footprint "LED SMD 0402")
      (description "RED LED, 0402 SMD")
      (fields (field (name "MANUFACTURER") "Rohm") (field (name "Comment") "LED SMD 0402"))
      (libsource (lib "Richs Schematic Components") (part "LED SMD 0402"))
    )
    (comp (ref "D134")
      (value "LED, Red, 0402")
      (footprint "LED SMD 0402")
      (description "RED LED, 0402 SMD")
      (fields (field (name "MANUFACTURER") "Rohm") (field (name "Comment") "LED SMD 0402"))
      (libsource (lib "Richs Schematic Components") (part "LED SMD 0402"))
    )
    (comp (ref "D135")
      (value "LED, Red, 0402")
      (footprint "LED SMD 0402")
      (description "RED LED, 0402 SMD")
      (fields (field (name "MANUFACTURER") "Rohm") (field (name "Comment") "LED SMD 0402"))
      (libsource (lib "Richs Schematic Components") (part "LED SMD 0402"))
    )
    (comp (ref "D136")
      (value "LED, Red, 0402")
      (footprint "LED SMD 0402")
      (description "RED LED, 0402 SMD")
      (fields (field (name "MANUFACTURER") "Rohm") (field (name "Comment") "LED SMD 0402"))
      (libsource (lib "Richs Schematic Components") (part "LED SMD 0402"))
    )
    (comp (ref "D137")
      (value "LED, Red, 0402")
      (footprint "LED SMD 0402")
      (description "RED LED, 0402 SMD")
      (fields (field (name "MANUFACTURER") "Rohm") (field (name "Comment") "LED SMD 0402"))
      (libsource (lib "Richs Schematic Components") (part "LED SMD 0402"))
    )
    (comp (ref "D138")
      (value "LED, Red, 0402")
      (footprint "LED SMD 0402")
      (description "RED LED, 0402 SMD")
      (fields (field (name "MANUFACTURER") "Rohm") (field (name "Comment") "LED SMD 0402"))
      (libsource (lib "Richs Schematic Components") (part "LED SMD 0402"))
    )
    (comp (ref "D139")
      (value "LED, Red, 0402")
      (footprint "LED SMD 0402")
      (description "RED LED, 0402 SMD")
      (fields (field (name "MANUFACTURER") "Rohm") (field (name "Comment") "LED SMD 0402"))
      (libsource (lib "Richs Schematic Components") (part "LED SMD 0402"))
    )
    (comp (ref "D140")
      (value "LED, Red, 0402")
      (footprint "LED SMD 0402")
      (description "RED LED, 0402 SMD")
      (fields (field (name "MANUFACTURER") "Rohm") (field (name "Comment") "LED SMD 0402"))
      (libsource (lib "Richs Schematic Components") (part "LED SMD 0402"))
    )
    (comp (ref "D141")
      (value "LED, Red, 0402")
      (footprint "LED SMD 0402")
      (description "RED LED, 0402 SMD")
      (fields (field (name "MANUFACTURER") "Rohm") (field (name "Comment") "LED SMD 0402"))
      (libsource (lib "Richs Schematic Components") (part "LED SMD 0402"))
    )
    (comp (ref "D142")
      (value "LED, Red, 0402")
      (footprint "LED SMD 0402")
      (description "RED LED, 0402 SMD")
      (fields (field (name "MANUFACTURER") "Rohm") (field (name "Comment") "LED SMD 0402"))
      (libsource (lib "Richs Schematic Components") (part "LED SMD 0402"))
    )
    (comp (ref "D143")
      (value "LED, Red, 0402")
      (footprint "LED SMD 0402")
      (description "RED LED, 0402 SMD")
      (fields (field (name "MANUFACTURER") "Rohm") (field (name "Comment") "LED SMD 0402"))
      (libsource (lib "Richs Schematic Components") (part "LED SMD 0402"))
    )
    (comp (ref "D144")
      (value "LED, Red, 0402")
      (footprint "LED SMD 0402")
      (description "RED LED, 0402 SMD")
      (fields (field (name "MANUFACTURER") "Rohm") (field (name "Comment") "LED SMD 0402"))
      (libsource (lib "Richs Schematic Components") (part "LED SMD 0402"))
    )
    (comp (ref "D145")
      (value "LED, Red, 0402")
      (footprint "LED SMD 0402")
      (description "RED LED, 0402 SMD")
      (fields (field (name "MANUFACTURER") "Rohm") (field (name "Comment") "LED SMD 0402"))
      (libsource (lib "Richs Schematic Components") (part "LED SMD 0402"))
    )
    (comp (ref "D146")
      (value "LED, Red, 0402")
      (footprint "LED SMD 0402")
      (description "RED LED, 0402 SMD")
      (fields (field (name "MANUFACTURER") "Rohm") (field (name "Comment") "LED SMD 0402"))
      (libsource (lib "Richs Schematic Components") (part "LED SMD 0402"))
    )
    (comp (ref "D147")
      (value "LED, Red, 0402")
      (footprint "LED SMD 0402")
      (description "RED LED, 0402 SMD")
      (fields (field (name "MANUFACTURER") "Rohm") (field (name "Comment") "LED SMD 0402"))
      (libsource (lib "Richs Schematic Components") (part "LED SMD 0402"))
    )
    (comp (ref "D148")
      (value "LED, Red, 0402")
      (footprint "LED SMD 0402")
      (description "RED LED, 0402 SMD")
      (fields (field (name "MANUFACTURER") "Rohm") (field (name "Comment") "LED SMD 0402"))
      (libsource (lib "Richs Schematic Components") (part "LED SMD 0402"))
    )
    (comp (ref "D149")
      (value "LED, Red, 0402")
      (footprint "LED SMD 0402")
      (description "RED LED, 0402 SMD")
      (fields (field (name "MANUFACTURER") "Rohm") (field (name "Comment") "LED SMD 0402"))
      (libsource (lib "Richs Schematic Components") (part "LED SMD 0402"))
    )
    (comp (ref "D150")
      (value "LED, Red, 0402")
      (footprint "LED SMD 0402")
      (description "RED LED, 0402 SMD")
      (fields (field (name "MANUFACTURER") "Rohm") (field (name "Comment") "LED SMD 0402"))
      (libsource (lib "Richs Schematic Components") (part "LED SMD 0402"))
    )
    (comp (ref "D151")
      (value "LED, Red, 0402")
      (footprint "LED SMD 0402")
      (description "RED LED, 0402 SMD")
      (fields (field (name "MANUFACTURER") "Rohm") (field (name "Comment") "LED SMD 0402"))
      (libsource (lib "Richs Schematic Components") (part "LED SMD 0402"))
    )
    (comp (ref "D152")
      (value "LED, Red, 0402")
      (footprint "LED SMD 0402")
      (description "RED LED, 0402 SMD")
      (fields (field (name "MANUFACTURER") "Rohm") (field (name "Comment") "LED SMD 0402"))
      (libsource (lib "Richs Schematic Components") (part "LED SMD 0402"))
    )
    (comp (ref "D153")
      (value "LED, Red, 0402")
      (footprint "LED SMD 0402")
      (description "RED LED, 0402 SMD")
      (fields (field (name "MANUFACTURER") "Rohm") (field (name "Comment") "LED SMD 0402"))
      (libsource (lib "Richs Schematic Components") (part "LED SMD 0402"))
    )
    (comp (ref "D154")
      (value "LED, Red, 0402")
      (footprint "LED SMD 0402")
      (description "RED LED, 0402 SMD")
      (fields (field (name "MANUFACTURER") "Rohm") (field (name "Comment") "LED SMD 0402"))
      (libsource (lib "Richs Schematic Components") (part "LED SMD 0402"))
    )
    (comp (ref "D155")
      (value "LED, Red, 0402")
      (footprint "LED SMD 0402")
      (description "RED LED, 0402 SMD")
      (fields (field (name "MANUFACTURER") "Rohm") (field (name "Comment") "LED SMD 0402"))
      (libsource (lib "Richs Schematic Components") (part "LED SMD 0402"))
    )
    (comp (ref "D156")
      (value "LED, Red, 0402")
      (footprint "LED SMD 0402")
      (description "RED LED, 0402 SMD")
      (fields (field (name "MANUFACTURER") "Rohm") (field (name "Comment") "LED SMD 0402"))
      (libsource (lib "Richs Schematic Components") (part "LED SMD 0402"))
    )
    (comp (ref "J1")
      (value "HDR 2x30   0.1\"")
      (footprint "HEADER 2X30")
      (fields (field (name "MANUFACTURER") "FCI"))
      (libsource (lib "") (part "HDR 2x30   0.1{dblquote}_1"))
    )
    (comp (ref "J2")
      (value "SAMTEC QSH-060-01-X-D-A")
      (footprint "QSH-060-010-X-D-A")
      (fields (field (name "MANUFACTURER") "SAMTEC"))
      (libsource (lib "") (part "QSH-060-01-X-D-A_1"))
    )
    (comp (ref "J3")
      (value "SAMTEC QSH-060-01-X-D-A")
      (footprint "QSH-060-010-X-D-A")
      (fields (field (name "MANUFACTURER") "SAMTEC"))
      (libsource (lib "") (part "QSH-060-01-X-D-A_1"))
    )
    (comp (ref "J4")
      (value "HDR 2x30   0.1\"")
      (footprint "HEADER 2X30")
      (fields (field (name "MANUFACTURER") "FCI"))
      (libsource (lib "Richs Schematic Components") (part "HDR 2x30   0.1{dblquote}"))
    )
    (comp (ref "J5")
      (value "HDR 2x30   0.1\"")
      (footprint "HEADER 2X30")
      (fields (field (name "MANUFACTURER") "FCI"))
      (libsource (lib "") (part "HDR 2x30   0.1{dblquote}_1"))
    )
    (comp (ref "J6")
      (value "HDR 2x30   0.1\"")
      (footprint "HEADER 2X30")
      (fields (field (name "MANUFACTURER") "FCI"))
      (libsource (lib "Richs Schematic Components") (part "HDR 2x30   0.1{dblquote}"))
    )
    (comp (ref "J7")
      (value "15-91-0140")
      (footprint "HDR2X7")
      (description "Header, 7-Pin, Dual row")
      (fields (field (name "MANUFACTURER") "Molex/Waldom"))
      (libsource (lib "Miscellaneous Connectors") (part "Header 7X2"))
    )
    (comp (ref "R1")
      (value "301")
      (footprint "SMD_0805")
      (description "Resistor 0805")
      (fields (field (name "MANUFACTURER") "Vishay/Dale") (field (name "Comment") "Res 0805"))
      (libsource (lib "Richs Schematic Components") (part "Res SMD"))
    )
    (comp (ref "R2")
      (value "301")
      (footprint "SMD_0805")
      (description "Resistor 0805")
      (fields (field (name "MANUFACTURER") "Vishay/Dale") (field (name "Comment") "Res 0805"))
      (libsource (lib "Richs Schematic Components") (part "Res SMD"))
    )
    (comp (ref "R3")
      (value "301")
      (footprint "SMD_0805")
      (description "Resistor 0805")
      (fields (field (name "MANUFACTURER") "Vishay/Dale") (field (name "Comment") "Res 0805"))
      (libsource (lib "Richs Schematic Components") (part "Res SMD"))
    )
    (comp (ref "R4")
      (value "301")
      (footprint "SMD_0805")
      (description "Resistor 0805")
      (fields (field (name "MANUFACTURER") "Vishay/Dale") (field (name "Comment") "Res 0805"))
      (libsource (lib "Richs Schematic Components") (part "Res SMD"))
    )
    (comp (ref "R5")
      (value "301")
      (footprint "SMD_0805")
      (description "Resistor 0805")
      (fields (field (name "MANUFACTURER") "Vishay/Dale") (field (name "Comment") "Res 0805"))
      (libsource (lib "Richs Schematic Components") (part "Res SMD"))
    )
    (comp (ref "R6")
      (value "301")
      (footprint "SMD_0805")
      (description "Resistor 0805")
      (fields (field (name "MANUFACTURER") "Vishay/Dale") (field (name "Comment") "Res 0805"))
      (libsource (lib "Richs Schematic Components") (part "Res SMD"))
    )
    (comp (ref "R7")
      (value "301")
      (footprint "SMD_0805")
      (description "Resistor 0805")
      (fields (field (name "MANUFACTURER") "Vishay/Dale") (field (name "Comment") "Res 0805"))
      (libsource (lib "Richs Schematic Components") (part "Res SMD"))
    )
    (comp (ref "R8")
      (value "301")
      (footprint "SMD_0805")
      (description "Resistor 0805")
      (fields (field (name "MANUFACTURER") "Vishay/Dale") (field (name "Comment") "Res 0805"))
      (libsource (lib "Richs Schematic Components") (part "Res SMD"))
    )
    (comp (ref "R9")
      (value "301")
      (footprint "SMD_0805")
      (description "Resistor 0805")
      (fields (field (name "MANUFACTURER") "Vishay/Dale") (field (name "Comment") "Res 0805"))
      (libsource (lib "Richs Schematic Components") (part "Res SMD"))
    )
    (comp (ref "R10")
      (value "301")
      (footprint "SMD_0805")
      (description "Resistor 0805")
      (fields (field (name "MANUFACTURER") "Vishay/Dale") (field (name "Comment") "Res 0805"))
      (libsource (lib "Richs Schematic Components") (part "Res SMD"))
    )
    (comp (ref "R11")
      (value "301")
      (footprint "SMD_0805")
      (description "Resistor 0805")
      (fields (field (name "MANUFACTURER") "Vishay/Dale") (field (name "Comment") "Res 0805"))
      (libsource (lib "Richs Schematic Components") (part "Res SMD"))
    )
    (comp (ref "R12")
      (value "301")
      (footprint "SMD_0805")
      (description "Resistor 0805")
      (fields (field (name "MANUFACTURER") "Vishay/Dale") (field (name "Comment") "Res 0805"))
      (libsource (lib "Richs Schematic Components") (part "Res SMD"))
    )
    (comp (ref "R13")
      (value "301")
      (footprint "SMD_0805")
      (description "Resistor 0805")
      (fields (field (name "MANUFACTURER") "Vishay/Dale") (field (name "Comment") "Res 0805"))
      (libsource (lib "Richs Schematic Components") (part "Res SMD"))
    )
    (comp (ref "R14")
      (value "301")
      (footprint "SMD_0805")
      (description "Resistor 0805")
      (fields (field (name "MANUFACTURER") "Vishay/Dale") (field (name "Comment") "Res 0805"))
      (libsource (lib "Richs Schematic Components") (part "Res SMD"))
    )
    (comp (ref "R15")
      (value "301")
      (footprint "SMD_0805")
      (description "Resistor 0805")
      (fields (field (name "MANUFACTURER") "Vishay/Dale") (field (name "Comment") "Res 0805"))
      (libsource (lib "Richs Schematic Components") (part "Res SMD"))
    )
    (comp (ref "R16")
      (value "301")
      (footprint "SMD_0805")
      (description "Resistor 0805")
      (fields (field (name "MANUFACTURER") "Vishay/Dale") (field (name "Comment") "Res 0805"))
      (libsource (lib "Richs Schematic Components") (part "Res SMD"))
    )
    (comp (ref "R17")
      (value "301")
      (footprint "SMD_0805")
      (description "Resistor 0805")
      (fields (field (name "MANUFACTURER") "Vishay/Dale") (field (name "Comment") "Res 0805"))
      (libsource (lib "Richs Schematic Components") (part "Res SMD"))
    )
    (comp (ref "R18")
      (value "301")
      (footprint "SMD_0805")
      (description "Resistor 0805")
      (fields (field (name "MANUFACTURER") "Vishay/Dale") (field (name "Comment") "Res 0805"))
      (libsource (lib "Richs Schematic Components") (part "Res SMD"))
    )
    (comp (ref "R19")
      (value "301")
      (footprint "SMD_0805")
      (description "Resistor 0805")
      (fields (field (name "MANUFACTURER") "Vishay/Dale") (field (name "Comment") "Res 0805"))
      (libsource (lib "Richs Schematic Components") (part "Res SMD"))
    )
    (comp (ref "R20")
      (value "301")
      (footprint "SMD_0805")
      (description "Resistor 0805")
      (fields (field (name "MANUFACTURER") "Vishay/Dale") (field (name "Comment") "Res 0805"))
      (libsource (lib "Richs Schematic Components") (part "Res SMD"))
    )
    (comp (ref "R21")
      (value "301")
      (footprint "SMD_0805")
      (description "Resistor 0805")
      (fields (field (name "MANUFACTURER") "Vishay/Dale") (field (name "Comment") "Res 0805"))
      (libsource (lib "Richs Schematic Components") (part "Res SMD"))
    )
    (comp (ref "R22")
      (value "301")
      (footprint "SMD_0805")
      (description "Resistor 0805")
      (fields (field (name "MANUFACTURER") "Vishay/Dale") (field (name "Comment") "Res 0805"))
      (libsource (lib "Richs Schematic Components") (part "Res SMD"))
    )
    (comp (ref "R23")
      (value "301")
      (footprint "SMD_0805")
      (description "Resistor 0805")
      (fields (field (name "MANUFACTURER") "Vishay/Dale") (field (name "Comment") "Res 0805"))
      (libsource (lib "Richs Schematic Components") (part "Res SMD"))
    )
    (comp (ref "R24")
      (value "301")
      (footprint "SMD_0805")
      (description "Resistor 0805")
      (fields (field (name "MANUFACTURER") "Vishay/Dale") (field (name "Comment") "Res 0805"))
      (libsource (lib "Richs Schematic Components") (part "Res SMD"))
    )
    (comp (ref "R25")
      (value "301")
      (footprint "SMD_0805")
      (description "Resistor 0805")
      (fields (field (name "MANUFACTURER") "Vishay/Dale") (field (name "Comment") "Res 0805"))
      (libsource (lib "Richs Schematic Components") (part "Res SMD"))
    )
    (comp (ref "R26")
      (value "301")
      (footprint "SMD_0805")
      (description "Resistor 0805")
      (fields (field (name "MANUFACTURER") "Vishay/Dale") (field (name "Comment") "Res 0805"))
      (libsource (lib "Richs Schematic Components") (part "Res SMD"))
    )
    (comp (ref "R27")
      (value "301")
      (footprint "SMD_0805")
      (description "Resistor 0805")
      (fields (field (name "MANUFACTURER") "Vishay/Dale") (field (name "Comment") "Res 0805"))
      (libsource (lib "Richs Schematic Components") (part "Res SMD"))
    )
    (comp (ref "R28")
      (value "301")
      (footprint "SMD_0805")
      (description "Resistor 0805")
      (fields (field (name "MANUFACTURER") "Vishay/Dale") (field (name "Comment") "Res 0805"))
      (libsource (lib "Richs Schematic Components") (part "Res SMD"))
    )
    (comp (ref "TP1")
      (value "Test point")
      (footprint "Protel 99SE BANKS PCB:PAD_80D_052H")
      (description "Test Point")
      (fields (field (name "MANUFACTURER") "Keystone"))
      (libsource (lib "Richs Schematic Components") (part "Test point"))
    )
    (comp (ref "TP2")
      (value "Test point")
      (footprint "Protel 99SE BANKS PCB:PAD_80D_052H")
      (description "Test Point")
      (fields (field (name "MANUFACTURER") "Keystone"))
      (libsource (lib "Richs Schematic Components") (part "Test point"))
    )
    (comp (ref "TP3")
      (value "Test point")
      (footprint "Protel 99SE BANKS PCB:PAD_80D_052H")
      (description "Test Point")
      (fields (field (name "MANUFACTURER") "Keystone"))
      (libsource (lib "Richs Schematic Components") (part "Test point"))
    )
    (comp (ref "TP4")
      (value "Test point")
      (footprint "Protel 99SE BANKS PCB:PAD_80D_052H")
      (description "Test Point")
      (fields (field (name "MANUFACTURER") "Keystone"))
      (libsource (lib "Richs Schematic Components") (part "Test point"))
    )
    (comp (ref "TP5")
      (value "Test point")
      (footprint "Protel 99SE BANKS PCB:PAD_80D_052H")
      (description "Test Point")
      (fields (field (name "MANUFACTURER") "Keystone"))
      (libsource (lib "Richs Schematic Components") (part "Test point"))
    )
    (comp (ref "TP6")
      (value "Test point")
      (footprint "Protel 99SE BANKS PCB:PAD_80D_052H")
      (description "Test Point")
      (fields (field (name "MANUFACTURER") "Keystone"))
      (libsource (lib "Richs Schematic Components") (part "Test point"))
    )
    (comp (ref "TP7")
      (value "Test point")
      (footprint "Protel 99SE BANKS PCB:PAD_80D_052H")
      (description "Test Point")
      (fields (field (name "MANUFACTURER") "Keystone"))
      (libsource (lib "Richs Schematic Components") (part "Test point"))
    )
    (comp (ref "TP8")
      (value "Test point")
      (footprint "Protel 99SE BANKS PCB:PAD_80D_052H")
      (description "Test Point")
      (fields (field (name "MANUFACTURER") "Keystone"))
      (libsource (lib "Richs Schematic Components") (part "Test point"))
    )
    (comp (ref "TP9")
      (value "Test point")
      (footprint "Protel 99SE BANKS PCB:PAD_80D_052H")
      (description "Test Point")
      (fields (field (name "MANUFACTURER") "Keystone"))
      (libsource (lib "Richs Schematic Components") (part "Test point"))
    )
    (comp (ref "TP10")
      (value "Test point")
      (footprint "Protel 99SE BANKS PCB:PAD_80D_052H")
      (description "Test Point")
      (fields (field (name "MANUFACTURER") "Keystone"))
      (libsource (lib "Richs Schematic Components") (part "Test point"))
    )
    (comp (ref "U1")
      (value "SuperFin Module")
      (footprint "SuperFin Footprint")
      (libsource (lib "Richs Schematic Components") (part "SuperFin Module"))
    )
  )
  (nets
    (net (code "1") (name "/+12V") (class "Default")
      (node (ref "J2") (pin "5") (pintype "passive"))
      (node (ref "J5") (pin "55") (pintype "passive"))
      (node (ref "TP3") (pin "1") (pinfunction "TP_1") (pintype "passive"))
      (node (ref "U1") (pin "A5") (pinfunction "+12V_A5") (pintype "passive"))
    )
    (net (code "2") (name "/-12V") (class "Default")
      (node (ref "J2") (pin "3") (pintype "passive"))
      (node (ref "J5") (pin "57") (pintype "passive"))
      (node (ref "TP2") (pin "1") (pinfunction "TP_1") (pintype "passive"))
      (node (ref "U1") (pin "A3") (pinfunction "-12V_A3") (pintype "passive"))
    )
    (net (code "3") (name "/3.3V") (class "Default")
      (node (ref "J3") (pin "121") (pintype "passive"))
      (node (ref "TP4") (pin "1") (pinfunction "TP_1") (pintype "passive"))
      (node (ref "U1") (pin "B121") (pinfunction "3.3V_B121") (pintype "passive"))
    )
    (net (code "4") (name "/5V") (class "Default")
      (node (ref "J2") (pin "1") (pinfunction "GND_1") (pintype "passive"))
      (node (ref "J5") (pin "59") (pintype "passive"))
      (node (ref "TP1") (pin "1") (pinfunction "TP_1") (pintype "passive"))
      (node (ref "U1") (pin "A1") (pinfunction "5V_A1") (pintype "passive"))
    )
    (net (code "5") (name "/AGND") (class "Default")
      (node (ref "J2") (pin "121") (pintype "passive"))
      (node (ref "U1") (pin "A121") (pinfunction "AGND_A121") (pintype "passive"))
    )
    (net (code "6") (name "GND") (class "Default")
      (node (ref "D117") (pin "1") (pinfunction "Cathode_1") (pintype "passive"))
      (node (ref "D118") (pin "1") (pinfunction "Cathode_1") (pintype "passive"))
      (node (ref "D119") (pin "1") (pinfunction "Cathode_1") (pintype "passive"))
      (node (ref "D120") (pin "1") (pinfunction "Cathode_1") (pintype "passive"))
      (node (ref "D121") (pin "1") (pinfunction "Cathode_1") (pintype "passive"))
      (node (ref "D123") (pin "1") (pinfunction "Cathode_1") (pintype "passive"))
      (node (ref "D124") (pin "1") (pinfunction "Cathode_1") (pintype "passive"))
      (node (ref "D126") (pin "1") (pinfunction "Cathode_1") (pintype "passive"))
      (node (ref "D127") (pin "1") (pinfunction "Cathode_1") (pintype "passive"))
      (node (ref "D129") (pin "1") (pinfunction "Cathode_1") (pintype "passive"))
      (node (ref "D130") (pin "1") (pinfunction "Cathode_1") (pintype "passive"))
      (node (ref "D132") (pin "1") (pinfunction "Cathode_1") (pintype "passive"))
      (node (ref "D133") (pin "1") (pinfunction "Cathode_1") (pintype "passive"))
      (node (ref "D135") (pin "1") (pinfunction "Cathode_1") (pintype "passive"))
      (node (ref "D136") (pin "1") (pinfunction "Cathode_1") (pintype "passive"))
      (node (ref "D138") (pin "1") (pinfunction "Cathode_1") (pintype "passive"))
      (node (ref "J2") (pin "122") (pintype "passive"))
      (node (ref "J3") (pin "122") (pintype "passive"))
      (node (ref "J7") (pin "1") (pinfunction "1_1") (pintype "passive"))
      (node (ref "J7") (pin "10") (pinfunction "10_10") (pintype "passive"))
      (node (ref "J7") (pin "11") (pinfunction "11_11") (pintype "passive"))
      (node (ref "J7") (pin "12") (pinfunction "12_12") (pintype "passive"))
      (node (ref "J7") (pin "13") (pinfunction "13_13") (pintype "passive"))
      (node (ref "J7") (pin "14") (pinfunction "14_14") (pintype "passive"))
      (node (ref "J7") (pin "2") (pinfunction "2_2") (pintype "passive"))
      (node (ref "J7") (pin "3") (pinfunction "3_3") (pintype "passive"))
      (node (ref "J7") (pin "4") (pinfunction "4_4") (pintype "passive"))
      (node (ref "J7") (pin "5") (pinfunction "5_5") (pintype "passive"))
      (node (ref "J7") (pin "6") (pinfunction "6_6") (pintype "passive"))
      (node (ref "J7") (pin "7") (pinfunction "7_7") (pintype "passive"))
      (node (ref "J7") (pin "8") (pinfunction "8_8") (pintype "passive"))
      (node (ref "J7") (pin "9") (pinfunction "9_9") (pintype "passive"))
      (node (ref "TP10") (pin "1") (pinfunction "TP_1") (pintype "passive"))
      (node (ref "TP5") (pin "1") (pinfunction "TP_1") (pintype "passive"))
      (node (ref "TP6") (pin "1") (pinfunction "TP_1") (pintype "passive"))
      (node (ref "TP7") (pin "1") (pinfunction "TP_1") (pintype "passive"))
      (node (ref "TP8") (pin "1") (pinfunction "TP_1") (pintype "passive"))
      (node (ref "TP9") (pin "1") (pinfunction "TP_1") (pintype "passive"))
      (node (ref "U1") (pin "A122") (pinfunction "DGND_A122") (pintype "passive"))
      (node (ref "U1") (pin "B122") (pinfunction "DGND_B122") (pintype "passive"))
    )
    (net (code "7") (name "Net-(D1-Anode)") (class "Default")
      (node (ref "D1") (pin "2") (pinfunction "Anode_2") (pintype "passive"))
      (node (ref "D3") (pin "1") (pinfunction "Cathode_1") (pintype "passive"))
      (node (ref "J1") (pin "60") (pintype "passive"))
      (node (ref "U1") (pin "B1") (pinfunction "~Home4_B1") (pintype "passive"))
    )
    (net (code "8") (name "Net-(D1-Cathode)") (class "Default")
      (node (ref "D1") (pin "1") (pinfunction "Cathode_1") (pintype "passive"))
      (node (ref "D3") (pin "2") (pinfunction "Anode_2") (pintype "passive"))
      (node (ref "J3") (pin "1") (pinfunction "GND_1") (pintype "passive"))
    )
    (net (code "9") (name "Net-(D2-Anode)") (class "Default")
      (node (ref "D2") (pin "2") (pinfunction "Anode_2") (pintype "passive"))
      (node (ref "D6") (pin "1") (pinfunction "Cathode_1") (pintype "passive"))
      (node (ref "J1") (pin "58") (pintype "passive"))
      (node (ref "U1") (pin "B3") (pinfunction "~Home3_B3") (pintype "passive"))
    )
    (net (code "10") (name "Net-(D2-Cathode)") (class "Default")
      (node (ref "D2") (pin "1") (pinfunction "Cathode_1") (pintype "passive"))
      (node (ref "D6") (pin "2") (pinfunction "Anode_2") (pintype "passive"))
      (node (ref "J3") (pin "3") (pintype "passive"))
    )
    (net (code "11") (name "Net-(D4-Anode)") (class "Default")
      (node (ref "D4") (pin "2") (pinfunction "Anode_2") (pintype "passive"))
      (node (ref "J3") (pin "2") (pintype "passive"))
    )
    (net (code "12") (name "Net-(D4-Cathode)") (class "Default")
      (node (ref "D4") (pin "1") (pinfunction "Cathode_1") (pintype "passive"))
      (node (ref "J1") (pin "59") (pintype "passive"))
      (node (ref "U1") (pin "B2") (pinfunction "GP_Out_D2_B2") (pintype "passive"))
    )
    (net (code "13") (name "Net-(D5-Anode)") (class "Default")
      (node (ref "D5") (pin "2") (pinfunction "Anode_2") (pintype "passive"))
      (node (ref "D8") (pin "1") (pinfunction "Cathode_1") (pintype "passive"))
      (node (ref "J1") (pin "56") (pintype "passive"))
      (node (ref "U1") (pin "B5") (pinfunction "~Home2_B5") (pintype "passive"))
    )
    (net (code "14") (name "Net-(D5-Cathode)") (class "Default")
      (node (ref "D5") (pin "1") (pinfunction "Cathode_1") (pintype "passive"))
      (node (ref "D8") (pin "2") (pinfunction "Anode_2") (pintype "passive"))
      (node (ref "J3") (pin "5") (pintype "passive"))
    )
    (net (code "15") (name "Net-(D9-Anode)") (class "Default")
      (node (ref "D9") (pin "2") (pinfunction "Anode_2") (pintype "passive"))
      (node (ref "J3") (pin "6") (pintype "passive"))
    )
    (net (code "16") (name "Net-(D9-Cathode)") (class "Default")
      (node (ref "D9") (pin "1") (pinfunction "Cathode_1") (pintype "passive"))
      (node (ref "J1") (pin "55") (pintype "passive"))
      (node (ref "U1") (pin "B6") (pinfunction "GP_Out_D3_B6") (pintype "passive"))
    )
    (net (code "17") (name "Net-(D10-Anode)") (class "Default")
      (node (ref "D10") (pin "2") (pinfunction "Anode_2") (pintype "passive"))
      (node (ref "D7") (pin "1") (pinfunction "Cathode_1") (pintype "passive"))
      (node (ref "J3") (pin "7") (pintype "passive"))
    )
    (net (code "18") (name "Net-(D10-Cathode)") (class "Default")
      (node (ref "D10") (pin "1") (pinfunction "Cathode_1") (pintype "passive"))
      (node (ref "D7") (pin "2") (pinfunction "Anode_2") (pintype "passive"))
      (node (ref "J1") (pin "54") (pintype "passive"))
      (node (ref "U1") (pin "B7") (pinfunction "~Home1_B7") (pintype "passive"))
    )
    (net (code "19") (name "Net-(D11-Anode)") (class "Default")
      (node (ref "D11") (pin "2") (pinfunction "Anode_2") (pintype "passive"))
      (node (ref "D14") (pin "1") (pinfunction "Cathode_1") (pintype "passive"))
      (node (ref "J1") (pin "50") (pintype "passive"))
      (node (ref "U1") (pin "B11") (pinfunction "PosLimt4_B11") (pintype "passive"))
    )
    (net (code "20") (name "Net-(D11-Cathode)") (class "Default")
      (node (ref "D11") (pin "1") (pinfunction "Cathode_1") (pintype "passive"))
      (node (ref "D14") (pin "2") (pinfunction "Anode_2") (pintype "passive"))
      (node (ref "J3") (pin "11") (pintype "passive"))
    )
    (net (code "21") (name "Net-(D12-Anode)") (class "Default")
      (node (ref "D12") (pin "2") (pinfunction "Anode_2") (pintype "passive"))
      (node (ref "J3") (pin "10") (pintype "passive"))
    )
    (net (code "22") (name "Net-(D12-Cathode)") (class "Default")
      (node (ref "D12") (pin "1") (pinfunction "Cathode_1") (pintype "passive"))
      (node (ref "J1") (pin "51") (pintype "passive"))
      (node (ref "U1") (pin "B10") (pinfunction "GP_Out_D4_B10") (pintype "passive"))
    )
    (net (code "23") (name "Net-(D13-Anode)") (class "Default")
      (node (ref "D13") (pin "2") (pinfunction "Anode_2") (pintype "passive"))
      (node (ref "D17") (pin "1") (pinfunction "Cathode_1") (pintype "passive"))
      (node (ref "J1") (pin "48") (pintype "passive"))
      (node (ref "U1") (pin "B13") (pinfunction "PosLimt3_B13") (pintype "passive"))
    )
    (net (code "24") (name "Net-(D13-Cathode)") (class "Default")
      (node (ref "D13") (pin "1") (pinfunction "Cathode_1") (pintype "passive"))
      (node (ref "D17") (pin "2") (pinfunction "Anode_2") (pintype "passive"))
      (node (ref "J3") (pin "13") (pintype "passive"))
    )
    (net (code "25") (name "Net-(D15-Anode)") (class "Default")
      (node (ref "D15") (pin "2") (pinfunction "Anode_2") (pintype "passive"))
      (node (ref "D19") (pin "1") (pinfunction "Cathode_1") (pintype "passive"))
      (node (ref "J1") (pin "46") (pintype "passive"))
      (node (ref "U1") (pin "B15") (pinfunction "PosLimt2_B15") (pintype "passive"))
    )
    (net (code "26") (name "Net-(D15-Cathode)") (class "Default")
      (node (ref "D15") (pin "1") (pinfunction "Cathode_1") (pintype "passive"))
      (node (ref "D19") (pin "2") (pinfunction "Anode_2") (pintype "passive"))
      (node (ref "J3") (pin "15") (pintype "passive"))
    )
    (net (code "27") (name "Net-(D16-Anode)") (class "Default")
      (node (ref "D16") (pin "2") (pinfunction "Anode_2") (pintype "passive"))
      (node (ref "J3") (pin "14") (pintype "passive"))
    )
    (net (code "28") (name "Net-(D16-Cathode)") (class "Default")
      (node (ref "D16") (pin "1") (pinfunction "Cathode_1") (pintype "passive"))
      (node (ref "J1") (pin "47") (pintype "passive"))
      (node (ref "U1") (pin "B14") (pinfunction "GP_Out_D5_B14") (pintype "passive"))
    )
    (net (code "29") (name "Net-(D18-Anode)") (class "Default")
      (node (ref "D18") (pin "2") (pinfunction "Anode_2") (pintype "passive"))
      (node (ref "D20") (pin "1") (pinfunction "Cathode_1") (pintype "passive"))
      (node (ref "J1") (pin "44") (pintype "passive"))
      (node (ref "U1") (pin "B17") (pinfunction "PosLimt1_B17") (pintype "passive"))
    )
    (net (code "30") (name "Net-(D18-Cathode)") (class "Default")
      (node (ref "D18") (pin "1") (pinfunction "Cathode_1") (pintype "passive"))
      (node (ref "D20") (pin "2") (pinfunction "Anode_2") (pintype "passive"))
      (node (ref "J3") (pin "17") (pintype "passive"))
    )
    (net (code "31") (name "Net-(D21-Anode)") (class "Default")
      (node (ref "D21") (pin "2") (pinfunction "Anode_2") (pintype "passive"))
      (node (ref "J3") (pin "18") (pintype "passive"))
    )
    (net (code "32") (name "Net-(D21-Cathode)") (class "Default")
      (node (ref "D21") (pin "1") (pinfunction "Cathode_1") (pintype "passive"))
      (node (ref "J1") (pin "43") (pintype "passive"))
      (node (ref "U1") (pin "B18") (pinfunction "GP_Out_D6_B18") (pintype "passive"))
    )
    (net (code "33") (name "Net-(D22-Anode)") (class "Default")
      (node (ref "D22") (pin "2") (pinfunction "Anode_2") (pintype "passive"))
      (node (ref "D24") (pin "1") (pinfunction "Cathode_1") (pintype "passive"))
      (node (ref "J1") (pin "40") (pintype "passive"))
      (node (ref "U1") (pin "B21") (pinfunction "NegLimt4_B21") (pintype "passive"))
    )
    (net (code "34") (name "Net-(D22-Cathode)") (class "Default")
      (node (ref "D22") (pin "1") (pinfunction "Cathode_1") (pintype "passive"))
      (node (ref "D24") (pin "2") (pinfunction "Anode_2") (pintype "passive"))
      (node (ref "J3") (pin "21") (pintype "passive"))
    )
    (net (code "35") (name "Net-(D23-Anode)") (class "Default")
      (node (ref "D23") (pin "2") (pinfunction "Anode_2") (pintype "passive"))
      (node (ref "D27") (pin "1") (pinfunction "Cathode_1") (pintype "passive"))
      (node (ref "J1") (pin "38") (pintype "passive"))
      (node (ref "U1") (pin "B23") (pinfunction "NegLimt3_B23") (pintype "passive"))
    )
    (net (code "36") (name "Net-(D23-Cathode)") (class "Default")
      (node (ref "D23") (pin "1") (pinfunction "Cathode_1") (pintype "passive"))
      (node (ref "D27") (pin "2") (pinfunction "Anode_2") (pintype "passive"))
      (node (ref "J3") (pin "23") (pintype "passive"))
    )
    (net (code "37") (name "Net-(D25-Anode)") (class "Default")
      (node (ref "D25") (pin "2") (pinfunction "Anode_2") (pintype "passive"))
      (node (ref "J3") (pin "22") (pintype "passive"))
    )
    (net (code "38") (name "Net-(D25-Cathode)") (class "Default")
      (node (ref "D25") (pin "1") (pinfunction "Cathode_1") (pintype "passive"))
      (node (ref "J1") (pin "39") (pintype "passive"))
      (node (ref "U1") (pin "B22") (pinfunction "GP_Out_D7_B22") (pintype "passive"))
    )
    (net (code "39") (name "Net-(D26-Anode)") (class "Default")
      (node (ref "D26") (pin "2") (pinfunction "Anode_2") (pintype "passive"))
      (node (ref "D29") (pin "1") (pinfunction "Cathode_1") (pintype "passive"))
      (node (ref "J1") (pin "36") (pintype "passive"))
      (node (ref "U1") (pin "B25") (pinfunction "NegLimt2_B25") (pintype "passive"))
    )
    (net (code "40") (name "Net-(D26-Cathode)") (class "Default")
      (node (ref "D26") (pin "1") (pinfunction "Cathode_1") (pintype "passive"))
      (node (ref "D29") (pin "2") (pinfunction "Anode_2") (pintype "passive"))
      (node (ref "J3") (pin "25") (pintype "passive"))
    )
    (net (code "41") (name "Net-(D28-Anode)") (class "Default")
      (node (ref "D28") (pin "2") (pinfunction "Anode_2") (pintype "passive"))
      (node (ref "D31") (pin "1") (pinfunction "Cathode_1") (pintype "passive"))
      (node (ref "J1") (pin "34") (pintype "passive"))
      (node (ref "U1") (pin "B27") (pinfunction "NegLimt1_B27") (pintype "passive"))
    )
    (net (code "42") (name "Net-(D28-Cathode)") (class "Default")
      (node (ref "D28") (pin "1") (pinfunction "Cathode_1") (pintype "passive"))
      (node (ref "D31") (pin "2") (pinfunction "Anode_2") (pintype "passive"))
      (node (ref "J3") (pin "27") (pintype "passive"))
    )
    (net (code "43") (name "Net-(D30-Anode)") (class "Default")
      (node (ref "D30") (pin "2") (pinfunction "Anode_2") (pintype "passive"))
      (node (ref "J3") (pin "26") (pintype "passive"))
    )
    (net (code "44") (name "Net-(D30-Cathode)") (class "Default")
      (node (ref "D30") (pin "1") (pinfunction "Cathode_1") (pintype "passive"))
      (node (ref "J1") (pin "35") (pintype "passive"))
      (node (ref "U1") (pin "B26") (pinfunction "GP_Out_D8_B26") (pintype "passive"))
    )
    (net (code "45") (name "Net-(D32-Anode)") (class "Default")
      (node (ref "D32") (pin "2") (pinfunction "Anode_2") (pintype "passive"))
      (node (ref "J3") (pin "30") (pintype "passive"))
    )
    (net (code "46") (name "Net-(D32-Cathode)") (class "Default")
      (node (ref "D32") (pin "1") (pinfunction "Cathode_1") (pintype "passive"))
      (node (ref "J1") (pin "31") (pintype "passive"))
      (node (ref "U1") (pin "B30") (pinfunction "GP_Out_D9_B30") (pintype "passive"))
    )
    (net (code "47") (name "Net-(D33-Anode)") (class "Default")
      (node (ref "D33") (pin "2") (pinfunction "Anode_2") (pintype "passive"))
      (node (ref "J3") (pin "34") (pintype "passive"))
    )
    (net (code "48") (name "Net-(D33-Cathode)") (class "Default")
      (node (ref "D33") (pin "1") (pinfunction "Cathode_1") (pintype "passive"))
      (node (ref "J1") (pin "27") (pintype "passive"))
      (node (ref "U1") (pin "B34") (pinfunction "GP_Out_D10_B34") (pintype "passive"))
    )
    (net (code "49") (name "Net-(D34-Anode)") (class "Default")
      (node (ref "D34") (pin "2") (pinfunction "Anode_2") (pintype "passive"))
      (node (ref "J3") (pin "38") (pintype "passive"))
    )
    (net (code "50") (name "Net-(D34-Cathode)") (class "Default")
      (node (ref "D34") (pin "1") (pinfunction "Cathode_1") (pintype "passive"))
      (node (ref "J1") (pin "23") (pintype "passive"))
      (node (ref "U1") (pin "B38") (pinfunction "GP_Out_D11_B38") (pintype "passive"))
    )
    (net (code "51") (name "Net-(D35-Anode)") (class "Default")
      (node (ref "D35") (pin "2") (pinfunction "Anode_2") (pintype "passive"))
      (node (ref "J3") (pin "42") (pintype "passive"))
    )
    (net (code "52") (name "Net-(D35-Cathode)") (class "Default")
      (node (ref "D35") (pin "1") (pinfunction "Cathode_1") (pintype "passive"))
      (node (ref "J1") (pin "19") (pintype "passive"))
      (node (ref "U1") (pin "B42") (pinfunction "GP_Out_D12_B42") (pintype "passive"))
    )
    (net (code "53") (name "Net-(D36-Anode)") (class "Default")
      (node (ref "D36") (pin "2") (pinfunction "Anode_2") (pintype "passive"))
      (node (ref "J3") (pin "46") (pintype "passive"))
    )
    (net (code "54") (name "Net-(D36-Cathode)") (class "Default")
      (node (ref "D36") (pin "1") (pinfunction "Cathode_1") (pintype "passive"))
      (node (ref "J1") (pin "15") (pintype "passive"))
      (node (ref "U1") (pin "B46") (pinfunction "GP_Out_D13_B46") (pintype "passive"))
    )
    (net (code "55") (name "Net-(D37-Anode)") (class "Default")
      (node (ref "D37") (pin "2") (pinfunction "Anode_2") (pintype "passive"))
      (node (ref "J3") (pin "47") (pintype "passive"))
    )
    (net (code "56") (name "Net-(D37-Cathode)") (class "Default")
      (node (ref "D37") (pin "1") (pinfunction "Cathode_1") (pintype "passive"))
      (node (ref "J1") (pin "14") (pintype "passive"))
      (node (ref "U1") (pin "B47") (pinfunction "GP_Out_D0_B47") (pintype "passive"))
    )
    (net (code "57") (name "Net-(D38-Anode)") (class "Default")
      (node (ref "D38") (pin "2") (pinfunction "Anode_2") (pintype "passive"))
      (node (ref "J3") (pin "50") (pintype "passive"))
    )
    (net (code "58") (name "Net-(D38-Cathode)") (class "Default")
      (node (ref "D38") (pin "1") (pinfunction "Cathode_1") (pintype "passive"))
      (node (ref "J1") (pin "11") (pintype "passive"))
      (node (ref "U1") (pin "B50") (pinfunction "GP_Out_D14_B50") (pintype "passive"))
    )
    (net (code "59") (name "Net-(D39-Anode)") (class "Default")
      (node (ref "D39") (pin "2") (pinfunction "Anode_2") (pintype "passive"))
      (node (ref "J3") (pin "51") (pintype "passive"))
    )
    (net (code "60") (name "Net-(D39-Cathode)") (class "Default")
      (node (ref "D39") (pin "1") (pinfunction "Cathode_1") (pintype "passive"))
      (node (ref "J1") (pin "10") (pintype "passive"))
      (node (ref "U1") (pin "B51") (pinfunction "GP_Out_D1_B51") (pintype "passive"))
    )
    (net (code "61") (name "Net-(D40-Anode)") (class "Default")
      (node (ref "D40") (pin "2") (pinfunction "Anode_2") (pintype "passive"))
      (node (ref "J3") (pin "54") (pintype "passive"))
    )
    (net (code "62") (name "Net-(D40-Cathode)") (class "Default")
      (node (ref "D40") (pin "1") (pinfunction "Cathode_1") (pintype "passive"))
      (node (ref "J1") (pin "7") (pintype "passive"))
      (node (ref "U1") (pin "B54") (pinfunction "GP_Out_D15_B54") (pintype "passive"))
    )
    (net (code "63") (name "Net-(D41-Anode)") (class "Default")
      (node (ref "D41") (pin "2") (pinfunction "Anode_2") (pintype "passive"))
      (node (ref "D43") (pin "1") (pinfunction "Cathode_1") (pintype "passive"))
      (node (ref "J1") (pin "4") (pintype "passive"))
      (node (ref "U1") (pin "B57") (pinfunction "Opto_Input0_B57") (pintype "passive"))
    )
    (net (code "64") (name "Net-(D41-Cathode)") (class "Default")
      (node (ref "D41") (pin "1") (pinfunction "Cathode_1") (pintype "passive"))
      (node (ref "D43") (pin "2") (pinfunction "Anode_2") (pintype "passive"))
      (node (ref "J3") (pin "57") (pintype "passive"))
    )
    (net (code "65") (name "Net-(D42-Anode)") (class "Default")
      (node (ref "D42") (pin "2") (pinfunction "Anode_2") (pintype "passive"))
      (node (ref "D46") (pin "1") (pinfunction "Cathode_1") (pintype "passive"))
      (node (ref "J1") (pin "2") (pintype "passive"))
      (node (ref "U1") (pin "B59") (pinfunction "Opto_Input1_B59") (pintype "passive"))
    )
    (net (code "66") (name "Net-(D42-Cathode)") (class "Default")
      (node (ref "D42") (pin "1") (pinfunction "Cathode_1") (pintype "passive"))
      (node (ref "D46") (pin "2") (pinfunction "Anode_2") (pintype "passive"))
      (node (ref "J3") (pin "59") (pintype "passive"))
    )
    (net (code "67") (name "Net-(D44-Anode)") (class "Default")
      (node (ref "D44") (pin "2") (pinfunction "Anode_2") (pintype "passive"))
      (node (ref "J3") (pin "58") (pintype "passive"))
    )
    (net (code "68") (name "Net-(D44-Cathode)") (class "Default")
      (node (ref "D44") (pin "1") (pinfunction "Cathode_1") (pintype "passive"))
      (node (ref "J1") (pin "3") (pintype "passive"))
      (node (ref "U1") (pin "B58") (pinfunction "GP_Out_D16_B58") (pintype "passive"))
    )
    (net (code "69") (name "Net-(D45-Anode)") (class "Default")
      (node (ref "D45") (pin "2") (pinfunction "Anode_2") (pintype "passive"))
      (node (ref "D48") (pin "1") (pinfunction "Cathode_1") (pintype "passive"))
      (node (ref "J4") (pin "1") (pintype "passive"))
      (node (ref "U1") (pin "B61") (pinfunction "Opto_Input2_B61") (pintype "passive"))
    )
    (net (code "70") (name "Net-(D45-Cathode)") (class "Default")
      (node (ref "D45") (pin "1") (pinfunction "Cathode_1") (pintype "passive"))
      (node (ref "D48") (pin "2") (pinfunction "Anode_2") (pintype "passive"))
      (node (ref "J3") (pin "61") (pintype "passive"))
    )
    (net (code "71") (name "Net-(D47-Anode)") (class "Default")
      (node (ref "D47") (pin "2") (pinfunction "Anode_2") (pintype "passive"))
      (node (ref "D50") (pin "1") (pinfunction "Cathode_1") (pintype "passive"))
      (node (ref "J4") (pin "3") (pintype "passive"))
      (node (ref "U1") (pin "B63") (pinfunction "Opto_Input3_B63") (pintype "passive"))
    )
    (net (code "72") (name "Net-(D47-Cathode)") (class "Default")
      (node (ref "D47") (pin "1") (pinfunction "Cathode_1") (pintype "passive"))
      (node (ref "D50") (pin "2") (pinfunction "Anode_2") (pintype "passive"))
      (node (ref "J3") (pin "63") (pintype "passive"))
    )
    (net (code "73") (name "Net-(D49-Anode)") (class "Default")
      (node (ref "D49") (pin "2") (pinfunction "Anode_2") (pintype "passive"))
      (node (ref "J3") (pin "62") (pintype "passive"))
    )
    (net (code "74") (name "Net-(D49-Cathode)") (class "Default")
      (node (ref "D49") (pin "1") (pinfunction "Cathode_1") (pintype "passive"))
      (node (ref "J4") (pin "2") (pintype "passive"))
      (node (ref "U1") (pin "B62") (pinfunction "GP_Out_D17_B62") (pintype "passive"))
    )
    (net (code "75") (name "Net-(D51-Anode)") (class "Default")
      (node (ref "D51") (pin "2") (pinfunction "Anode_2") (pintype "passive"))
      (node (ref "J3") (pin "66") (pintype "passive"))
    )
    (net (code "76") (name "Net-(D51-Cathode)") (class "Default")
      (node (ref "D51") (pin "1") (pinfunction "Cathode_1") (pintype "passive"))
      (node (ref "J4") (pin "6") (pintype "passive"))
      (node (ref "U1") (pin "B66") (pinfunction "GP_Out_D18_B66") (pintype "passive"))
    )
    (net (code "77") (name "Net-(D52-Anode)") (class "Default")
      (node (ref "D52") (pin "2") (pinfunction "Anode_2") (pintype "passive"))
      (node (ref "J3") (pin "70") (pintype "passive"))
    )
    (net (code "78") (name "Net-(D52-Cathode)") (class "Default")
      (node (ref "D52") (pin "1") (pinfunction "Cathode_1") (pintype "passive"))
      (node (ref "J4") (pin "10") (pintype "passive"))
      (node (ref "U1") (pin "B70") (pinfunction "GP_Out_D19_B70") (pintype "passive"))
    )
    (net (code "79") (name "Net-(D53-Anode)") (class "Default")
      (node (ref "D53") (pin "2") (pinfunction "Anode_2") (pintype "passive"))
      (node (ref "D55") (pin "1") (pinfunction "Cathode_1") (pintype "passive"))
      (node (ref "J4") (pin "13") (pintype "passive"))
      (node (ref "U1") (pin "B73") (pinfunction "Opto_Input4_B73") (pintype "passive"))
    )
    (net (code "80") (name "Net-(D53-Cathode)") (class "Default")
      (node (ref "D53") (pin "1") (pinfunction "Cathode_1") (pintype "passive"))
      (node (ref "D55") (pin "2") (pinfunction "Anode_2") (pintype "passive"))
      (node (ref "J3") (pin "73") (pintype "passive"))
    )
    (net (code "81") (name "Net-(D54-Anode)") (class "Default")
      (node (ref "D54") (pin "2") (pinfunction "Anode_2") (pintype "passive"))
      (node (ref "D58") (pin "1") (pinfunction "Cathode_1") (pintype "passive"))
      (node (ref "J4") (pin "15") (pintype "passive"))
      (node (ref "U1") (pin "B75") (pinfunction "Opto_Input5_B75") (pintype "passive"))
    )
    (net (code "82") (name "Net-(D54-Cathode)") (class "Default")
      (node (ref "D54") (pin "1") (pinfunction "Cathode_1") (pintype "passive"))
      (node (ref "D58") (pin "2") (pinfunction "Anode_2") (pintype "passive"))
      (node (ref "J3") (pin "75") (pintype "passive"))
    )
    (net (code "83") (name "Net-(D56-Anode)") (class "Default")
      (node (ref "D56") (pin "2") (pinfunction "Anode_2") (pintype "passive"))
      (node (ref "J3") (pin "74") (pintype "passive"))
    )
    (net (code "84") (name "Net-(D56-Cathode)") (class "Default")
      (node (ref "D56") (pin "1") (pinfunction "Cathode_1") (pintype "passive"))
      (node (ref "J4") (pin "14") (pintype "passive"))
      (node (ref "U1") (pin "B74") (pinfunction "GP_Out_D20_B74") (pintype "passive"))
    )
    (net (code "85") (name "Net-(D57-Anode)") (class "Default")
      (node (ref "D57") (pin "2") (pinfunction "Anode_2") (pintype "passive"))
      (node (ref "D60") (pin "1") (pinfunction "Cathode_1") (pintype "passive"))
      (node (ref "J4") (pin "17") (pintype "passive"))
      (node (ref "U1") (pin "B77") (pinfunction "Opto_Input6_B77") (pintype "passive"))
    )
    (net (code "86") (name "Net-(D57-Cathode)") (class "Default")
      (node (ref "D57") (pin "1") (pinfunction "Cathode_1") (pintype "passive"))
      (node (ref "D60") (pin "2") (pinfunction "Anode_2") (pintype "passive"))
      (node (ref "J3") (pin "77") (pintype "passive"))
    )
    (net (code "87") (name "Net-(D59-Anode)") (class "Default")
      (node (ref "D59") (pin "2") (pinfunction "Anode_2") (pintype "passive"))
      (node (ref "D62") (pin "1") (pinfunction "Cathode_1") (pintype "passive"))
      (node (ref "J4") (pin "19") (pintype "passive"))
      (node (ref "U1") (pin "B79") (pinfunction "Opto_Input7_B79") (pintype "passive"))
    )
    (net (code "88") (name "Net-(D59-Cathode)") (class "Default")
      (node (ref "D59") (pin "1") (pinfunction "Cathode_1") (pintype "passive"))
      (node (ref "D62") (pin "2") (pinfunction "Anode_2") (pintype "passive"))
      (node (ref "J3") (pin "79") (pintype "passive"))
    )
    (net (code "89") (name "Net-(D61-Anode)") (class "Default")
      (node (ref "D61") (pin "2") (pinfunction "Anode_2") (pintype "passive"))
      (node (ref "J3") (pin "78") (pintype "passive"))
    )
    (net (code "90") (name "Net-(D61-Cathode)") (class "Default")
      (node (ref "D61") (pin "1") (pinfunction "Cathode_1") (pintype "passive"))
      (node (ref "J4") (pin "18") (pintype "passive"))
      (node (ref "U1") (pin "B78") (pinfunction "GP_Out_D21_B78") (pintype "passive"))
    )
    (net (code "91") (name "Net-(D63-Anode)") (class "Default")
      (node (ref "D63") (pin "2") (pinfunction "Anode_2") (pintype "passive"))
      (node (ref "D66") (pin "1") (pinfunction "Cathode_1") (pintype "passive"))
      (node (ref "J4") (pin "23") (pintype "passive"))
      (node (ref "U1") (pin "B83") (pinfunction "Opto_Input8_B83") (pintype "passive"))
    )
    (net (code "92") (name "Net-(D63-Cathode)") (class "Default")
      (node (ref "D63") (pin "1") (pinfunction "Cathode_1") (pintype "passive"))
      (node (ref "D66") (pin "2") (pinfunction "Anode_2") (pintype "passive"))
      (node (ref "J3") (pin "83") (pintype "passive"))
    )
    (net (code "93") (name "Net-(D64-Anode)") (class "Default")
      (node (ref "D64") (pin "2") (pinfunction "Anode_2") (pintype "passive"))
      (node (ref "J3") (pin "82") (pintype "passive"))
    )
    (net (code "94") (name "Net-(D64-Cathode)") (class "Default")
      (node (ref "D64") (pin "1") (pinfunction "Cathode_1") (pintype "passive"))
      (node (ref "J4") (pin "22") (pintype "passive"))
      (node (ref "U1") (pin "B82") (pinfunction "GP_Out_D22_B82") (pintype "passive"))
    )
    (net (code "95") (name "Net-(D65-Anode)") (class "Default")
      (node (ref "D65") (pin "2") (pinfunction "Anode_2") (pintype "passive"))
      (node (ref "D69") (pin "1") (pinfunction "Cathode_1") (pintype "passive"))
      (node (ref "J4") (pin "25") (pintype "passive"))
      (node (ref "U1") (pin "B85") (pinfunction "Opto_Input9_B85") (pintype "passive"))
    )
    (net (code "96") (name "Net-(D65-Cathode)") (class "Default")
      (node (ref "D65") (pin "1") (pinfunction "Cathode_1") (pintype "passive"))
      (node (ref "D69") (pin "2") (pinfunction "Anode_2") (pintype "passive"))
      (node (ref "J3") (pin "85") (pintype "passive"))
    )
    (net (code "97") (name "Net-(D67-Anode)") (class "Default")
      (node (ref "D67") (pin "2") (pinfunction "Anode_2") (pintype "passive"))
      (node (ref "D71") (pin "1") (pinfunction "Cathode_1") (pintype "passive"))
      (node (ref "J4") (pin "27") (pintype "passive"))
      (node (ref "U1") (pin "B87") (pinfunction "Opto_Input10_B87") (pintype "passive"))
    )
    (net (code "98") (name "Net-(D67-Cathode)") (class "Default")
      (node (ref "D67") (pin "1") (pinfunction "Cathode_1") (pintype "passive"))
      (node (ref "D71") (pin "2") (pinfunction "Anode_2") (pintype "passive"))
      (node (ref "J3") (pin "87") (pintype "passive"))
    )
    (net (code "99") (name "Net-(D68-Anode)") (class "Default")
      (node (ref "D68") (pin "2") (pinfunction "Anode_2") (pintype "passive"))
      (node (ref "J3") (pin "86") (pintype "passive"))
    )
    (net (code "100") (name "Net-(D68-Cathode)") (class "Default")
      (node (ref "D68") (pin "1") (pinfunction "Cathode_1") (pintype "passive"))
      (node (ref "J4") (pin "26") (pintype "passive"))
      (node (ref "U1") (pin "B86") (pinfunction "GP_Out_D23_B86") (pintype "passive"))
    )
    (net (code "101") (name "Net-(D70-Anode)") (class "Default")
      (node (ref "D70") (pin "2") (pinfunction "Anode_2") (pintype "passive"))
      (node (ref "D72") (pin "1") (pinfunction "Cathode_1") (pintype "passive"))
      (node (ref "J4") (pin "29") (pintype "passive"))
      (node (ref "U1") (pin "B89") (pinfunction "Opto_Input11_B89") (pintype "passive"))
    )
    (net (code "102") (name "Net-(D70-Cathode)") (class "Default")
      (node (ref "D70") (pin "1") (pinfunction "Cathode_1") (pintype "passive"))
      (node (ref "D72") (pin "2") (pinfunction "Anode_2") (pintype "passive"))
      (node (ref "J3") (pin "89") (pintype "passive"))
    )
    (net (code "103") (name "Net-(D73-Anode)") (class "Default")
      (node (ref "D73") (pin "2") (pinfunction "Anode_2") (pintype "passive"))
      (node (ref "J3") (pin "90") (pintype "passive"))
    )
    (net (code "104") (name "Net-(D73-Cathode)") (class "Default")
      (node (ref "D73") (pin "1") (pinfunction "Cathode_1") (pintype "passive"))
      (node (ref "J4") (pin "30") (pintype "passive"))
      (node (ref "U1") (pin "B90") (pinfunction "GP_Out_D24_B90") (pintype "passive"))
    )
    (net (code "105") (name "Net-(D74-Anode)") (class "Default")
      (node (ref "D74") (pin "2") (pinfunction "Anode_2") (pintype "passive"))
      (node (ref "D76") (pin "1") (pinfunction "Cathode_1") (pintype "passive"))
      (node (ref "J4") (pin "33") (pintype "passive"))
      (node (ref "U1") (pin "B93") (pinfunction "Opto_Input12_B93") (pintype "passive"))
    )
    (net (code "106") (name "Net-(D74-Cathode)") (class "Default")
      (node (ref "D74") (pin "1") (pinfunction "Cathode_1") (pintype "passive"))
      (node (ref "D76") (pin "2") (pinfunction "Anode_2") (pintype "passive"))
      (node (ref "J3") (pin "93") (pintype "passive"))
    )
    (net (code "107") (name "Net-(D75-Anode)") (class "Default")
      (node (ref "D75") (pin "2") (pinfunction "Anode_2") (pintype "passive"))
      (node (ref "D79") (pin "1") (pinfunction "Cathode_1") (pintype "passive"))
      (node (ref "J4") (pin "35") (pintype "passive"))
      (node (ref "U1") (pin "B95") (pinfunction "Opto_Input13_B95") (pintype "passive"))
    )
    (net (code "108") (name "Net-(D75-Cathode)") (class "Default")
      (node (ref "D75") (pin "1") (pinfunction "Cathode_1") (pintype "passive"))
      (node (ref "D79") (pin "2") (pinfunction "Anode_2") (pintype "passive"))
      (node (ref "J3") (pin "95") (pintype "passive"))
    )
    (net (code "109") (name "Net-(D77-Anode)") (class "Default")
      (node (ref "D77") (pin "2") (pinfunction "Anode_2") (pintype "passive"))
      (node (ref "J3") (pin "94") (pintype "passive"))
    )
    (net (code "110") (name "Net-(D77-Cathode)") (class "Default")
      (node (ref "D77") (pin "1") (pinfunction "Cathode_1") (pintype "passive"))
      (node (ref "J4") (pin "34") (pintype "passive"))
      (node (ref "U1") (pin "B94") (pinfunction "GP_Out_D25_B94") (pintype "passive"))
    )
    (net (code "111") (name "Net-(D78-Anode)") (class "Default")
      (node (ref "D78") (pin "2") (pinfunction "Anode_2") (pintype "passive"))
      (node (ref "D81") (pin "1") (pinfunction "Cathode_1") (pintype "passive"))
      (node (ref "J4") (pin "37") (pintype "passive"))
      (node (ref "U1") (pin "B97") (pinfunction "Opto_Input14_B97") (pintype "passive"))
    )
    (net (code "112") (name "Net-(D78-Cathode)") (class "Default")
      (node (ref "D78") (pin "1") (pinfunction "Cathode_1") (pintype "passive"))
      (node (ref "D81") (pin "2") (pinfunction "Anode_2") (pintype "passive"))
      (node (ref "J3") (pin "97") (pintype "passive"))
    )
    (net (code "113") (name "Net-(D80-Anode)") (class "Default")
      (node (ref "D80") (pin "2") (pinfunction "Anode_2") (pintype "passive"))
      (node (ref "D83") (pin "1") (pinfunction "Cathode_1") (pintype "passive"))
      (node (ref "J4") (pin "39") (pintype "passive"))
      (node (ref "U1") (pin "B99") (pinfunction "Opto_Input15_B99") (pintype "passive"))
    )
    (net (code "114") (name "Net-(D80-Cathode)") (class "Default")
      (node (ref "D80") (pin "1") (pinfunction "Cathode_1") (pintype "passive"))
      (node (ref "D83") (pin "2") (pinfunction "Anode_2") (pintype "passive"))
      (node (ref "J3") (pin "99") (pintype "passive"))
    )
    (net (code "115") (name "Net-(D82-Anode)") (class "Default")
      (node (ref "D82") (pin "2") (pinfunction "Anode_2") (pintype "passive"))
      (node (ref "J3") (pin "98") (pintype "passive"))
    )
    (net (code "116") (name "Net-(D82-Cathode)") (class "Default")
      (node (ref "D82") (pin "1") (pinfunction "Cathode_1") (pintype "passive"))
      (node (ref "J4") (pin "38") (pintype "passive"))
      (node (ref "U1") (pin "B98") (pinfunction "GP_Out_D26_B98") (pintype "passive"))
    )
    (net (code "117") (name "Net-(D84-Anode)") (class "Default")
      (node (ref "D84") (pin "2") (pinfunction "Anode_2") (pintype "passive"))
      (node (ref "D87") (pin "1") (pinfunction "Cathode_1") (pintype "passive"))
      (node (ref "J4") (pin "43") (pintype "passive"))
      (node (ref "U1") (pin "B103") (pinfunction "Opto_Input16_B103") (pintype "passive"))
    )
    (net (code "118") (name "Net-(D84-Cathode)") (class "Default")
      (node (ref "D84") (pin "1") (pinfunction "Cathode_1") (pintype "passive"))
      (node (ref "D87") (pin "2") (pinfunction "Anode_2") (pintype "passive"))
      (node (ref "J3") (pin "103") (pintype "passive"))
    )
    (net (code "119") (name "Net-(D85-Anode)") (class "Default")
      (node (ref "D85") (pin "2") (pinfunction "Anode_2") (pintype "passive"))
      (node (ref "J3") (pin "102") (pintype "passive"))
    )
    (net (code "120") (name "Net-(D85-Cathode)") (class "Default")
      (node (ref "D85") (pin "1") (pinfunction "Cathode_1") (pintype "passive"))
      (node (ref "J4") (pin "42") (pintype "passive"))
      (node (ref "U1") (pin "B102") (pinfunction "GP_Out_D27_B102") (pintype "passive"))
    )
    (net (code "121") (name "Net-(D86-Anode)") (class "Default")
      (node (ref "D86") (pin "2") (pinfunction "Anode_2") (pintype "passive"))
      (node (ref "D90") (pin "1") (pinfunction "Cathode_1") (pintype "passive"))
      (node (ref "J4") (pin "45") (pintype "passive"))
      (node (ref "U1") (pin "B105") (pinfunction "Opto_Input17_B105") (pintype "passive"))
    )
    (net (code "122") (name "Net-(D86-Cathode)") (class "Default")
      (node (ref "D86") (pin "1") (pinfunction "Cathode_1") (pintype "passive"))
      (node (ref "D90") (pin "2") (pinfunction "Anode_2") (pintype "passive"))
      (node (ref "J3") (pin "105") (pintype "passive"))
    )
    (net (code "123") (name "Net-(D88-Anode)") (class "Default")
      (node (ref "D88") (pin "2") (pinfunction "Anode_2") (pintype "passive"))
      (node (ref "D92") (pin "1") (pinfunction "Cathode_1") (pintype "passive"))
      (node (ref "J4") (pin "47") (pintype "passive"))
      (node (ref "U1") (pin "B107") (pinfunction "Opto_Input18_B107") (pintype "passive"))
    )
    (net (code "124") (name "Net-(D88-Cathode)") (class "Default")
      (node (ref "D88") (pin "1") (pinfunction "Cathode_1") (pintype "passive"))
      (node (ref "D92") (pin "2") (pinfunction "Anode_2") (pintype "passive"))
      (node (ref "J3") (pin "107") (pintype "passive"))
    )
    (net (code "125") (name "Net-(D89-Anode)") (class "Default")
      (node (ref "D89") (pin "2") (pinfunction "Anode_2") (pintype "passive"))
      (node (ref "J3") (pin "106") (pintype "passive"))
    )
    (net (code "126") (name "Net-(D89-Cathode)") (class "Default")
      (node (ref "D89") (pin "1") (pinfunction "Cathode_1") (pintype "passive"))
      (node (ref "J4") (pin "46") (pintype "passive"))
      (node (ref "U1") (pin "B106") (pinfunction "GP_Out_D28_B106") (pintype "passive"))
    )
    (net (code "127") (name "Net-(D91-Anode)") (class "Default")
      (node (ref "D91") (pin "2") (pinfunction "Anode_2") (pintype "passive"))
      (node (ref "D93") (pin "1") (pinfunction "Cathode_1") (pintype "passive"))
      (node (ref "J4") (pin "49") (pintype "passive"))
      (node (ref "U1") (pin "B109") (pinfunction "Opto_Input19_B109") (pintype "passive"))
    )
    (net (code "128") (name "Net-(D91-Cathode)") (class "Default")
      (node (ref "D91") (pin "1") (pinfunction "Cathode_1") (pintype "passive"))
      (node (ref "D93") (pin "2") (pinfunction "Anode_2") (pintype "passive"))
      (node (ref "J3") (pin "109") (pintype "passive"))
    )
    (net (code "129") (name "Net-(D94-Anode)") (class "Default")
      (node (ref "D94") (pin "2") (pinfunction "Anode_2") (pintype "passive"))
      (node (ref "J3") (pin "110") (pintype "passive"))
    )
    (net (code "130") (name "Net-(D94-Cathode)") (class "Default")
      (node (ref "D94") (pin "1") (pinfunction "Cathode_1") (pintype "passive"))
      (node (ref "J4") (pin "50") (pintype "passive"))
      (node (ref "U1") (pin "B110") (pinfunction "GP_Out_D29_B110") (pintype "passive"))
    )
    (net (code "131") (name "Net-(D95-Anode)") (class "Default")
      (node (ref "D95") (pin "2") (pinfunction "Anode_2") (pintype "passive"))
      (node (ref "D97") (pin "1") (pinfunction "Cathode_1") (pintype "passive"))
      (node (ref "J4") (pin "53") (pintype "passive"))
      (node (ref "U1") (pin "B113") (pinfunction "Opto_Input20_B113") (pintype "passive"))
    )
    (net (code "132") (name "Net-(D95-Cathode)") (class "Default")
      (node (ref "D95") (pin "1") (pinfunction "Cathode_1") (pintype "passive"))
      (node (ref "D97") (pin "2") (pinfunction "Anode_2") (pintype "passive"))
      (node (ref "J3") (pin "113") (pintype "passive"))
    )
    (net (code "133") (name "Net-(D98-Anode)") (class "Default")
      (node (ref "D98") (pin "2") (pinfunction "Anode_2") (pintype "passive"))
      (node (ref "J3") (pin "114") (pintype "passive"))
    )
    (net (code "134") (name "Net-(D98-Cathode)") (class "Default")
      (node (ref "D98") (pin "1") (pinfunction "Cathode_1") (pintype "passive"))
      (node (ref "J4") (pin "54") (pintype "passive"))
      (node (ref "U1") (pin "B114") (pinfunction "GP_Out_D30_B114") (pintype "passive"))
    )
    (net (code "135") (name "Net-(D100-Anode)") (class "Default")
      (node (ref "D100") (pin "2") (pinfunction "Anode_2") (pintype "passive"))
      (node (ref "D96") (pin "1") (pinfunction "Cathode_1") (pintype "passive"))
      (node (ref "J3") (pin "115") (pintype "passive"))
    )
    (net (code "136") (name "Net-(D100-Cathode)") (class "Default")
      (node (ref "D100") (pin "1") (pinfunction "Cathode_1") (pintype "passive"))
      (node (ref "D96") (pin "2") (pinfunction "Anode_2") (pintype "passive"))
      (node (ref "J4") (pin "55") (pintype "passive"))
      (node (ref "U1") (pin "B115") (pinfunction "Opto_Input21_B115") (pintype "passive"))
    )
    (net (code "137") (name "Net-(D101-Anode)") (class "Default")
      (node (ref "D101") (pin "2") (pinfunction "Anode_2") (pintype "passive"))
      (node (ref "D104") (pin "1") (pinfunction "Cathode_1") (pintype "passive"))
      (node (ref "J4") (pin "59") (pintype "passive"))
      (node (ref "U1") (pin "B119") (pinfunction "Opto_Input23_B119") (pintype "passive"))
    )
    (net (code "138") (name "Net-(D101-Cathode)") (class "Default")
      (node (ref "D101") (pin "1") (pinfunction "Cathode_1") (pintype "passive"))
      (node (ref "D104") (pin "2") (pinfunction "Anode_2") (pintype "passive"))
      (node (ref "J3") (pin "119") (pintype "passive"))
    )
    (net (code "139") (name "Net-(D102-Anode)") (class "Default")
      (node (ref "D102") (pin "2") (pinfunction "Anode_2") (pintype "passive"))
      (node (ref "D99") (pin "1") (pinfunction "Cathode_1") (pintype "passive"))
      (node (ref "J3") (pin "117") (pintype "passive"))
    )
    (net (code "140") (name "Net-(D102-Cathode)") (class "Default")
      (node (ref "D102") (pin "1") (pinfunction "Cathode_1") (pintype "passive"))
      (node (ref "D99") (pin "2") (pinfunction "Anode_2") (pintype "passive"))
      (node (ref "J4") (pin "57") (pintype "passive"))
      (node (ref "U1") (pin "B117") (pinfunction "Opto_Input22_B117") (pintype "passive"))
    )
    (net (code "141") (name "Net-(D103-Anode)") (class "Default")
      (node (ref "D103") (pin "2") (pinfunction "Anode_2") (pintype "passive"))
      (node (ref "J3") (pin "118") (pintype "passive"))
    )
    (net (code "142") (name "Net-(D103-Cathode)") (class "Default")
      (node (ref "D103") (pin "1") (pinfunction "Cathode_1") (pintype "passive"))
      (node (ref "J4") (pin "58") (pintype "passive"))
      (node (ref "U1") (pin "B118") (pinfunction "GP_Out_D31_B118") (pintype "passive"))
    )
    (net (code "143") (name "Net-(D105-Anode)") (class "Default")
      (node (ref "D105") (pin "2") (pinfunction "Anode_2") (pintype "passive"))
      (node (ref "R1") (pin "2") (pinfunction "2_2") (pintype "passive"))
    )
    (net (code "144") (name "Net-(D105-Cathode)") (class "Default")
      (node (ref "D105") (pin "1") (pinfunction "Cathode_1") (pintype "passive"))
      (node (ref "J2") (pin "20") (pintype "passive"))
      (node (ref "J5") (pin "42") (pintype "passive"))
      (node (ref "U1") (pin "A20") (pinfunction "QuadA1-_A20") (pintype "passive"))
    )
    (net (code "145") (name "Net-(D106-Anode)") (class "Default")
      (node (ref "D106") (pin "2") (pinfunction "Anode_2") (pintype "passive"))
      (node (ref "R2") (pin "2") (pinfunction "2_2") (pintype "passive"))
    )
    (net (code "146") (name "Net-(D106-Cathode)") (class "Default")
      (node (ref "D106") (pin "1") (pinfunction "Cathode_1") (pintype "passive"))
      (node (ref "J2") (pin "24") (pintype "passive"))
      (node (ref "J5") (pin "38") (pintype "passive"))
      (node (ref "U1") (pin "A24") (pinfunction "QuadB1-_A24") (pintype "passive"))
    )
    (net (code "147") (name "Net-(D107-Anode)") (class "Default")
      (node (ref "D107") (pin "2") (pinfunction "Anode_2") (pintype "passive"))
      (node (ref "R3") (pin "2") (pinfunction "2_2") (pintype "passive"))
    )
    (net (code "148") (name "Net-(D107-Cathode)") (class "Default")
      (node (ref "D107") (pin "1") (pinfunction "Cathode_1") (pintype "passive"))
      (node (ref "J2") (pin "28") (pintype "passive"))
      (node (ref "J5") (pin "34") (pintype "passive"))
      (node (ref "U1") (pin "A28") (pinfunction "Index1-_A28") (pintype "passive"))
    )
    (net (code "149") (name "Net-(D108-Anode)") (class "Default")
      (node (ref "D108") (pin "2") (pinfunction "Anode_2") (pintype "passive"))
      (node (ref "R4") (pin "2") (pinfunction "2_2") (pintype "passive"))
    )
    (net (code "150") (name "Net-(D108-Cathode)") (class "Default")
      (node (ref "D108") (pin "1") (pinfunction "Cathode_1") (pintype "passive"))
      (node (ref "J2") (pin "32") (pintype "passive"))
      (node (ref "J5") (pin "30") (pintype "passive"))
      (node (ref "U1") (pin "A32") (pinfunction "QuadA2-_A32") (pintype "passive"))
    )
    (net (code "151") (name "Net-(D109-Anode)") (class "Default")
      (node (ref "D109") (pin "2") (pinfunction "Anode_2") (pintype "passive"))
      (node (ref "R5") (pin "2") (pinfunction "2_2") (pintype "passive"))
    )
    (net (code "152") (name "Net-(D109-Cathode)") (class "Default")
      (node (ref "D109") (pin "1") (pinfunction "Cathode_1") (pintype "passive"))
      (node (ref "J2") (pin "36") (pintype "passive"))
      (node (ref "J5") (pin "26") (pintype "passive"))
      (node (ref "U1") (pin "A36") (pinfunction "QuadB2-_A36") (pintype "passive"))
    )
    (net (code "153") (name "Net-(D110-Anode)") (class "Default")
      (node (ref "D110") (pin "2") (pinfunction "Anode_2") (pintype "passive"))
      (node (ref "R6") (pin "2") (pinfunction "2_2") (pintype "passive"))
    )
    (net (code "154") (name "Net-(D110-Cathode)") (class "Default")
      (node (ref "D110") (pin "1") (pinfunction "Cathode_1") (pintype "passive"))
      (node (ref "J2") (pin "40") (pintype "passive"))
      (node (ref "J5") (pin "22") (pintype "passive"))
      (node (ref "U1") (pin "A40") (pinfunction "Index2-_A40") (pintype "passive"))
    )
    (net (code "155") (name "Net-(D111-Anode)") (class "Default")
      (node (ref "D111") (pin "2") (pinfunction "Anode_2") (pintype "passive"))
      (node (ref "R7") (pin "2") (pinfunction "2_2") (pintype "passive"))
    )
    (net (code "156") (name "Net-(D111-Cathode)") (class "Default")
      (node (ref "D111") (pin "1") (pinfunction "Cathode_1") (pintype "passive"))
      (node (ref "J2") (pin "44") (pintype "passive"))
      (node (ref "J5") (pin "18") (pintype "passive"))
      (node (ref "U1") (pin "A44") (pinfunction "QuadA3-_A44") (pintype "passive"))
    )
    (net (code "157") (name "Net-(D112-Anode)") (class "Default")
      (node (ref "D112") (pin "2") (pinfunction "Anode_2") (pintype "passive"))
      (node (ref "R8") (pin "2") (pinfunction "2_2") (pintype "passive"))
    )
    (net (code "158") (name "Net-(D112-Cathode)") (class "Default")
      (node (ref "D112") (pin "1") (pinfunction "Cathode_1") (pintype "passive"))
      (node (ref "J2") (pin "48") (pintype "passive"))
      (node (ref "J5") (pin "14") (pintype "passive"))
      (node (ref "U1") (pin "A48") (pinfunction "QuadB3-_A48") (pintype "passive"))
    )
    (net (code "159") (name "Net-(D113-Anode)") (class "Default")
      (node (ref "D113") (pin "2") (pinfunction "Anode_2") (pintype "passive"))
      (node (ref "R9") (pin "2") (pinfunction "2_2") (pintype "passive"))
    )
    (net (code "160") (name "Net-(D113-Cathode)") (class "Default")
      (node (ref "D113") (pin "1") (pinfunction "Cathode_1") (pintype "passive"))
      (node (ref "J2") (pin "52") (pintype "passive"))
      (node (ref "J5") (pin "10") (pintype "passive"))
      (node (ref "U1") (pin "A52") (pinfunction "Index3-_A52") (pintype "passive"))
    )
    (net (code "161") (name "Net-(D114-Anode)") (class "Default")
      (node (ref "D114") (pin "2") (pinfunction "Anode_2") (pintype "passive"))
      (node (ref "R10") (pin "2") (pinfunction "2_2") (pintype "passive"))
    )
    (net (code "162") (name "Net-(D114-Cathode)") (class "Default")
      (node (ref "D114") (pin "1") (pinfunction "Cathode_1") (pintype "passive"))
      (node (ref "J2") (pin "56") (pintype "passive"))
      (node (ref "J5") (pin "6") (pintype "passive"))
      (node (ref "U1") (pin "A56") (pinfunction "QuadA4-_A56") (pintype "passive"))
    )
    (net (code "163") (name "Net-(D115-Anode)") (class "Default")
      (node (ref "D115") (pin "2") (pinfunction "Anode_2") (pintype "passive"))
      (node (ref "R11") (pin "2") (pinfunction "2_2") (pintype "passive"))
    )
    (net (code "164") (name "Net-(D115-Cathode)") (class "Default")
      (node (ref "D115") (pin "1") (pinfunction "Cathode_1") (pintype "passive"))
      (node (ref "J2") (pin "60") (pintype "passive"))
      (node (ref "J5") (pin "2") (pintype "passive"))
      (node (ref "U1") (pin "A60") (pinfunction "QuadB4-_A60") (pintype "passive"))
    )
    (net (code "165") (name "Net-(D116-Anode)") (class "Default")
      (node (ref "D116") (pin "2") (pinfunction "Anode_2") (pintype "passive"))
      (node (ref "R12") (pin "2") (pinfunction "2_2") (pintype "passive"))
    )
    (net (code "166") (name "Net-(D116-Cathode)") (class "Default")
      (node (ref "D116") (pin "1") (pinfunction "Cathode_1") (pintype "passive"))
      (node (ref "J2") (pin "64") (pintype "passive"))
      (node (ref "J6") (pin "3") (pintype "passive"))
      (node (ref "U1") (pin "A64") (pinfunction "Index4-_A64") (pintype "passive"))
    )
    (net (code "167") (name "Net-(D117-Anode)") (class "Default")
      (node (ref "D117") (pin "2") (pinfunction "Anode_2") (pintype "passive"))
      (node (ref "R13") (pin "2") (pinfunction "2_2") (pintype "passive"))
    )
    (net (code "168") (name "Net-(D118-Anode)") (class "Default")
      (node (ref "D118") (pin "2") (pinfunction "Anode_2") (pintype "passive"))
      (node (ref "R14") (pin "2") (pinfunction "2_2") (pintype "passive"))
    )
    (net (code "169") (name "Net-(D119-Anode)") (class "Default")
      (node (ref "D119") (pin "2") (pinfunction "Anode_2") (pintype "passive"))
      (node (ref "R15") (pin "2") (pinfunction "2_2") (pintype "passive"))
    )
    (net (code "170") (name "Net-(D120-Anode)") (class "Default")
      (node (ref "D120") (pin "2") (pinfunction "Anode_2") (pintype "passive"))
      (node (ref "R16") (pin "2") (pinfunction "2_2") (pintype "passive"))
    )
    (net (code "171") (name "Net-(D121-Anode)") (class "Default")
      (node (ref "D121") (pin "2") (pinfunction "Anode_2") (pintype "passive"))
      (node (ref "R17") (pin "2") (pinfunction "2_2") (pintype "passive"))
    )
    (net (code "172") (name "Net-(D122-Anode)") (class "Default")
      (node (ref "D122") (pin "2") (pinfunction "Anode_2") (pintype "passive"))
      (node (ref "J2") (pin "80") (pintype "passive"))
    )
    (net (code "173") (name "Net-(D122-Cathode)") (class "Default")
      (node (ref "D122") (pin "1") (pinfunction "Cathode_1") (pintype "passive"))
      (node (ref "J6") (pin "19") (pintype "passive"))
      (node (ref "U1") (pin "A80") (pinfunction "Opto_Out_C0_A80") (pintype "passive"))
    )
    (net (code "174") (name "Net-(D123-Anode)") (class "Default")
      (node (ref "D123") (pin "2") (pinfunction "Anode_2") (pintype "passive"))
      (node (ref "R18") (pin "2") (pinfunction "2_2") (pintype "passive"))
    )
    (net (code "175") (name "Net-(D124-Anode)") (class "Default")
      (node (ref "D124") (pin "2") (pinfunction "Anode_2") (pintype "passive"))
      (node (ref "R19") (pin "2") (pinfunction "2_2") (pintype "passive"))
    )
    (net (code "176") (name "Net-(D125-Anode)") (class "Default")
      (node (ref "D125") (pin "2") (pinfunction "Anode_2") (pintype "passive"))
      (node (ref "J2") (pin "84") (pintype "passive"))
    )
    (net (code "177") (name "Net-(D125-Cathode)") (class "Default")
      (node (ref "D125") (pin "1") (pinfunction "Cathode_1") (pintype "passive"))
      (node (ref "J6") (pin "23") (pintype "passive"))
      (node (ref "U1") (pin "A84") (pinfunction "Opto_Out_C1_A84") (pintype "passive"))
    )
    (net (code "178") (name "Net-(D126-Anode)") (class "Default")
      (node (ref "D126") (pin "2") (pinfunction "Anode_2") (pintype "passive"))
      (node (ref "R20") (pin "2") (pinfunction "2_2") (pintype "passive"))
    )
    (net (code "179") (name "Net-(D127-Anode)") (class "Default")
      (node (ref "D127") (pin "2") (pinfunction "Anode_2") (pintype "passive"))
      (node (ref "R21") (pin "2") (pinfunction "2_2") (pintype "passive"))
    )
    (net (code "180") (name "Net-(D128-Anode)") (class "Default")
      (node (ref "D128") (pin "2") (pinfunction "Anode_2") (pintype "passive"))
      (node (ref "J2") (pin "88") (pintype "passive"))
    )
    (net (code "181") (name "Net-(D128-Cathode)") (class "Default")
      (node (ref "D128") (pin "1") (pinfunction "Cathode_1") (pintype "passive"))
      (node (ref "J6") (pin "27") (pintype "passive"))
      (node (ref "U1") (pin "A88") (pinfunction "Opto_Out_C2_A88") (pintype "passive"))
    )
    (net (code "182") (name "Net-(D129-Anode)") (class "Default")
      (node (ref "D129") (pin "2") (pinfunction "Anode_2") (pintype "passive"))
      (node (ref "R22") (pin "2") (pinfunction "2_2") (pintype "passive"))
    )
    (net (code "183") (name "Net-(D130-Anode)") (class "Default")
      (node (ref "D130") (pin "2") (pinfunction "Anode_2") (pintype "passive"))
      (node (ref "R23") (pin "2") (pinfunction "2_2") (pintype "passive"))
    )
    (net (code "184") (name "Net-(D131-Anode)") (class "Default")
      (node (ref "D131") (pin "2") (pinfunction "Anode_2") (pintype "passive"))
      (node (ref "J2") (pin "92") (pintype "passive"))
    )
    (net (code "185") (name "Net-(D131-Cathode)") (class "Default")
      (node (ref "D131") (pin "1") (pinfunction "Cathode_1") (pintype "passive"))
      (node (ref "J6") (pin "31") (pintype "passive"))
      (node (ref "U1") (pin "A92") (pinfunction "Opto_Out_C3_A92") (pintype "passive"))
    )
    (net (code "186") (name "Net-(D132-Anode)") (class "Default")
      (node (ref "D132") (pin "2") (pinfunction "Anode_2") (pintype "passive"))
      (node (ref "R24") (pin "2") (pinfunction "2_2") (pintype "passive"))
    )
    (net (code "187") (name "Net-(D133-Anode)") (class "Default")
      (node (ref "D133") (pin "2") (pinfunction "Anode_2") (pintype "passive"))
      (node (ref "R25") (pin "2") (pinfunction "2_2") (pintype "passive"))
    )
    (net (code "188") (name "Net-(D134-Anode)") (class "Default")
      (node (ref "D134") (pin "2") (pinfunction "Anode_2") (pintype "passive"))
      (node (ref "J2") (pin "96") (pintype "passive"))
    )
    (net (code "189") (name "Net-(D134-Cathode)") (class "Default")
      (node (ref "D134") (pin "1") (pinfunction "Cathode_1") (pintype "passive"))
      (node (ref "J6") (pin "35") (pintype "passive"))
      (node (ref "U1") (pin "A96") (pinfunction "Opto_Out_C4_A96") (pintype "passive"))
    )
    (net (code "190") (name "Net-(D135-Anode)") (class "Default")
      (node (ref "D135") (pin "2") (pinfunction "Anode_2") (pintype "passive"))
      (node (ref "R26") (pin "2") (pinfunction "2_2") (pintype "passive"))
    )
    (net (code "191") (name "Net-(D136-Anode)") (class "Default")
      (node (ref "D136") (pin "2") (pinfunction "Anode_2") (pintype "passive"))
      (node (ref "R27") (pin "2") (pinfunction "2_2") (pintype "passive"))
    )
    (net (code "192") (name "Net-(D137-Anode)") (class "Default")
      (node (ref "D137") (pin "2") (pinfunction "Anode_2") (pintype "passive"))
      (node (ref "J2") (pin "100") (pintype "passive"))
    )
    (net (code "193") (name "Net-(D137-Cathode)") (class "Default")
      (node (ref "D137") (pin "1") (pinfunction "Cathode_1") (pintype "passive"))
      (node (ref "J6") (pin "39") (pintype "passive"))
      (node (ref "U1") (pin "A100") (pinfunction "Opto_Out_C5_A100") (pintype "passive"))
    )
    (net (code "194") (name "Net-(D138-Anode)") (class "Default")
      (node (ref "D138") (pin "2") (pinfunction "Anode_2") (pintype "passive"))
      (node (ref "R28") (pin "2") (pinfunction "2_2") (pintype "passive"))
    )
    (net (code "195") (name "Net-(D139-Anode)") (class "Default")
      (node (ref "D139") (pin "2") (pinfunction "Anode_2") (pintype "passive"))
      (node (ref "J2") (pin "104") (pintype "passive"))
    )
    (net (code "196") (name "Net-(D139-Cathode)") (class "Default")
      (node (ref "D139") (pin "1") (pinfunction "Cathode_1") (pintype "passive"))
      (node (ref "J6") (pin "43") (pintype "passive"))
      (node (ref "U1") (pin "A104") (pinfunction "Opto_Out_C6_A104") (pintype "passive"))
    )
    (net (code "197") (name "Net-(D140-Anode)") (class "Default")
      (node (ref "D140") (pin "2") (pinfunction "Anode_2") (pintype "passive"))
      (node (ref "J2") (pin "108") (pintype "passive"))
    )
    (net (code "198") (name "Net-(D140-Cathode)") (class "Default")
      (node (ref "D140") (pin "1") (pinfunction "Cathode_1") (pintype "passive"))
      (node (ref "J6") (pin "47") (pintype "passive"))
      (node (ref "U1") (pin "A108") (pinfunction "Opto_Out_C7_A108") (pintype "passive"))
    )
    (net (code "199") (name "Net-(D141-Anode)") (class "Default")
      (node (ref "D141") (pin "2") (pinfunction "Anode_2") (pintype "passive"))
      (node (ref "D142") (pin "1") (pinfunction "Cathode_1") (pintype "passive"))
      (node (ref "J2") (pin "114") (pintype "passive"))
    )
    (net (code "200") (name "Net-(D141-Cathode)") (class "Default")
      (node (ref "D141") (pin "1") (pinfunction "Cathode_1") (pintype "passive"))
      (node (ref "D142") (pin "2") (pinfunction "Anode_2") (pintype "passive"))
      (node (ref "J6") (pin "53") (pintype "passive"))
      (node (ref "U1") (pin "A114") (pinfunction "Opto_Input24_A114") (pintype "passive"))
    )
    (net (code "201") (name "Net-(D143-Anode)") (class "Default")
      (node (ref "D143") (pin "2") (pinfunction "Anode_2") (pintype "passive"))
      (node (ref "D145") (pin "1") (pinfunction "Cathode_1") (pintype "passive"))
      (node (ref "J2") (pin "116") (pintype "passive"))
    )
    (net (code "202") (name "Net-(D143-Cathode)") (class "Default")
      (node (ref "D143") (pin "1") (pinfunction "Cathode_1") (pintype "passive"))
      (node (ref "D145") (pin "2") (pinfunction "Anode_2") (pintype "passive"))
      (node (ref "J6") (pin "55") (pintype "passive"))
      (node (ref "U1") (pin "A116") (pinfunction "Opto_Input25_A116") (pintype "passive"))
    )
    (net (code "203") (name "Net-(D144-Anode)") (class "Default")
      (node (ref "D144") (pin "2") (pinfunction "Anode_2") (pintype "passive"))
      (node (ref "D146") (pin "1") (pinfunction "Cathode_1") (pintype "passive"))
      (node (ref "J2") (pin "118") (pintype "passive"))
    )
    (net (code "204") (name "Net-(D144-Cathode)") (class "Default")
      (node (ref "D144") (pin "1") (pinfunction "Cathode_1") (pintype "passive"))
      (node (ref "D146") (pin "2") (pinfunction "Anode_2") (pintype "passive"))
      (node (ref "J6") (pin "57") (pintype "passive"))
      (node (ref "U1") (pin "A118") (pinfunction "Opto_Input26_A118") (pintype "passive"))
    )
    (net (code "205") (name "Net-(D147-Anode)") (class "Default")
      (node (ref "D147") (pin "2") (pinfunction "Anode_2") (pintype "passive"))
      (node (ref "D148") (pin "1") (pinfunction "Cathode_1") (pintype "passive"))
      (node (ref "J2") (pin "120") (pintype "passive"))
    )
    (net (code "206") (name "Net-(D147-Cathode)") (class "Default")
      (node (ref "D147") (pin "1") (pinfunction "Cathode_1") (pintype "passive"))
      (node (ref "D148") (pin "2") (pinfunction "Anode_2") (pintype "passive"))
      (node (ref "J6") (pin "59") (pintype "passive"))
      (node (ref "U1") (pin "A120") (pinfunction "Opto_Input27_A120") (pintype "passive"))
    )
    (net (code "207") (name "Net-(D149-Anode)") (class "Default")
      (node (ref "D149") (pin "2") (pinfunction "Anode_2") (pintype "passive"))
      (node (ref "J3") (pin "31") (pintype "passive"))
    )
    (net (code "208") (name "Net-(D149-Cathode)") (class "Default")
      (node (ref "D149") (pin "1") (pinfunction "Cathode_1") (pintype "passive"))
      (node (ref "J1") (pin "30") (pintype "passive"))
      (node (ref "U1") (pin "B31") (pinfunction "Step1_B31") (pintype "passive"))
    )
    (net (code "209") (name "Net-(D150-Anode)") (class "Default")
      (node (ref "D150") (pin "2") (pinfunction "Anode_2") (pintype "passive"))
      (node (ref "J3") (pin "33") (pintype "passive"))
    )
    (net (code "210") (name "Net-(D150-Cathode)") (class "Default")
      (node (ref "D150") (pin "1") (pinfunction "Cathode_1") (pintype "passive"))
      (node (ref "J1") (pin "28") (pintype "passive"))
      (node (ref "U1") (pin "B33") (pinfunction "Step2_B33") (pintype "passive"))
    )
    (net (code "211") (name "Net-(D151-Anode)") (class "Default")
      (node (ref "D151") (pin "2") (pinfunction "Anode_2") (pintype "passive"))
      (node (ref "J3") (pin "35") (pintype "passive"))
    )
    (net (code "212") (name "Net-(D151-Cathode)") (class "Default")
      (node (ref "D151") (pin "1") (pinfunction "Cathode_1") (pintype "passive"))
      (node (ref "J1") (pin "26") (pintype "passive"))
      (node (ref "U1") (pin "B35") (pinfunction "Step3_B35") (pintype "passive"))
    )
    (net (code "213") (name "Net-(D152-Anode)") (class "Default")
      (node (ref "D152") (pin "2") (pinfunction "Anode_2") (pintype "passive"))
      (node (ref "J3") (pin "37") (pintype "passive"))
    )
    (net (code "214") (name "Net-(D152-Cathode)") (class "Default")
      (node (ref "D152") (pin "1") (pinfunction "Cathode_1") (pintype "passive"))
      (node (ref "J1") (pin "24") (pintype "passive"))
      (node (ref "U1") (pin "B37") (pinfunction "Step4_B37") (pintype "passive"))
    )
    (net (code "215") (name "Net-(D153-Anode)") (class "Default")
      (node (ref "D153") (pin "2") (pinfunction "Anode_2") (pintype "passive"))
      (node (ref "J3") (pin "39") (pintype "passive"))
    )
    (net (code "216") (name "Net-(D153-Cathode)") (class "Default")
      (node (ref "D153") (pin "1") (pinfunction "Cathode_1") (pintype "passive"))
      (node (ref "J1") (pin "22") (pintype "passive"))
      (node (ref "U1") (pin "B39") (pinfunction "Direction1_B39") (pintype "passive"))
    )
    (net (code "217") (name "Net-(D154-Anode)") (class "Default")
      (node (ref "D154") (pin "2") (pinfunction "Anode_2") (pintype "passive"))
      (node (ref "J3") (pin "41") (pintype "passive"))
    )
    (net (code "218") (name "Net-(D154-Cathode)") (class "Default")
      (node (ref "D154") (pin "1") (pinfunction "Cathode_1") (pintype "passive"))
      (node (ref "J1") (pin "20") (pintype "passive"))
      (node (ref "U1") (pin "B41") (pinfunction "Direction2_B41") (pintype "passive"))
    )
    (net (code "219") (name "Net-(D155-Anode)") (class "Default")
      (node (ref "D155") (pin "2") (pinfunction "Anode_2") (pintype "passive"))
      (node (ref "J3") (pin "43") (pintype "passive"))
    )
    (net (code "220") (name "Net-(D155-Cathode)") (class "Default")
      (node (ref "D155") (pin "1") (pinfunction "Cathode_1") (pintype "passive"))
      (node (ref "J1") (pin "18") (pintype "passive"))
      (node (ref "U1") (pin "B43") (pinfunction "Direction3_B43") (pintype "passive"))
    )
    (net (code "221") (name "Net-(D156-Anode)") (class "Default")
      (node (ref "D156") (pin "2") (pinfunction "Anode_2") (pintype "passive"))
      (node (ref "J3") (pin "45") (pintype "passive"))
    )
    (net (code "222") (name "Net-(D156-Cathode)") (class "Default")
      (node (ref "D156") (pin "1") (pinfunction "Cathode_1") (pintype "passive"))
      (node (ref "J1") (pin "16") (pintype "passive"))
      (node (ref "U1") (pin "B45") (pinfunction "Direction4_B45") (pintype "passive"))
    )
    (net (code "223") (name "Net-(U1A-Analog_In0)") (class "Default")
      (node (ref "J2") (pin "21") (pintype "passive"))
      (node (ref "J5") (pin "39") (pintype "passive"))
      (node (ref "U1") (pin "A21") (pinfunction "Analog_In0_A21") (pintype "passive"))
    )
    (net (code "224") (name "Net-(U1A-Analog_In1)") (class "Default")
      (node (ref "J2") (pin "19") (pintype "passive"))
      (node (ref "J5") (pin "41") (pintype "passive"))
      (node (ref "U1") (pin "A19") (pinfunction "Analog_In1_A19") (pintype "passive"))
    )
    (net (code "225") (name "Net-(U1A-Analog_In2)") (class "Default")
      (node (ref "J2") (pin "17") (pintype "passive"))
      (node (ref "J5") (pin "43") (pintype "passive"))
      (node (ref "U1") (pin "A17") (pinfunction "Analog_In2_A17") (pintype "passive"))
    )
    (net (code "226") (name "Net-(U1A-Analog_In3)") (class "Default")
      (node (ref "J2") (pin "15") (pintype "passive"))
      (node (ref "J5") (pin "45") (pintype "passive"))
      (node (ref "U1") (pin "A15") (pinfunction "Analog_In3_A15") (pintype "passive"))
    )
    (net (code "227") (name "Net-(U1A-Analog_In4)") (class "Default")
      (node (ref "J2") (pin "13") (pintype "passive"))
      (node (ref "J5") (pin "47") (pintype "passive"))
      (node (ref "U1") (pin "A13") (pinfunction "Analog_In4_A13") (pintype "passive"))
    )
    (net (code "228") (name "Net-(U1A-Analog_In5)") (class "Default")
      (node (ref "J2") (pin "11") (pintype "passive"))
      (node (ref "J5") (pin "49") (pintype "passive"))
      (node (ref "U1") (pin "A11") (pinfunction "Analog_In5_A11") (pintype "passive"))
    )
    (net (code "229") (name "Net-(U1A-Analog_In6)") (class "Default")
      (node (ref "J2") (pin "9") (pintype "passive"))
      (node (ref "J5") (pin "51") (pintype "passive"))
      (node (ref "U1") (pin "A9") (pinfunction "Analog_In6_A9") (pintype "passive"))
    )
    (net (code "230") (name "Net-(U1A-Analog_In7)") (class "Default")
      (node (ref "J2") (pin "7") (pintype "passive"))
      (node (ref "J5") (pin "53") (pintype "passive"))
      (node (ref "U1") (pin "A7") (pinfunction "Analog_In7_A7") (pintype "passive"))
    )
    (net (code "231") (name "Net-(U1A-Analog_In8)") (class "Default")
      (node (ref "J2") (pin "29") (pintype "passive"))
      (node (ref "J5") (pin "31") (pintype "passive"))
      (node (ref "U1") (pin "A29") (pinfunction "Analog_In8_A29") (pintype "passive"))
    )
    (net (code "232") (name "Net-(U1A-Analog_In9)") (class "Default")
      (node (ref "J2") (pin "27") (pintype "passive"))
      (node (ref "J5") (pin "33") (pintype "passive"))
      (node (ref "U1") (pin "A27") (pinfunction "Analog_In9_A27") (pintype "passive"))
    )
    (net (code "233") (name "Net-(U1A-Analog_In10)") (class "Default")
      (node (ref "J2") (pin "25") (pintype "passive"))
      (node (ref "J5") (pin "35") (pintype "passive"))
      (node (ref "U1") (pin "A25") (pinfunction "Analog_In10_A25") (pintype "passive"))
    )
    (net (code "234") (name "Net-(U1A-Analog_In11)") (class "Default")
      (node (ref "J2") (pin "23") (pintype "passive"))
      (node (ref "J5") (pin "37") (pintype "passive"))
      (node (ref "U1") (pin "A23") (pinfunction "Analog_In11_A23") (pintype "passive"))
    )
    (net (code "235") (name "Net-(U1A-Analog_In12)") (class "Default")
      (node (ref "J2") (pin "37") (pintype "passive"))
      (node (ref "J5") (pin "23") (pintype "passive"))
      (node (ref "U1") (pin "A37") (pinfunction "Analog_In12_A37") (pintype "passive"))
    )
    (net (code "236") (name "Net-(U1A-Analog_In13)") (class "Default")
      (node (ref "J2") (pin "39") (pintype "passive"))
      (node (ref "J5") (pin "21") (pintype "passive"))
      (node (ref "U1") (pin "A39") (pinfunction "Analog_In13_A39") (pintype "passive"))
    )
    (net (code "237") (name "Net-(U1A-Analog_In14)") (class "Default")
      (node (ref "J2") (pin "41") (pintype "passive"))
      (node (ref "J5") (pin "19") (pintype "passive"))
      (node (ref "U1") (pin "A41") (pinfunction "Analog_In14_A41") (pintype "passive"))
    )
    (net (code "238") (name "Net-(U1A-Analog_In15)") (class "Default")
      (node (ref "J2") (pin "43") (pintype "passive"))
      (node (ref "J5") (pin "17") (pintype "passive"))
      (node (ref "U1") (pin "A43") (pinfunction "Analog_In15_A43") (pintype "passive"))
    )
    (net (code "239") (name "Net-(U1A-BF-FPGA_TDO)") (class "Default")
      (node (ref "J2") (pin "74") (pintype "passive"))
      (node (ref "J6") (pin "13") (pintype "passive"))
      (node (ref "U1") (pin "A74") (pinfunction "BF-FPGA_TDO_A74") (pintype "passive"))
    )
    (net (code "240") (name "Net-(U1A-CAN_H)") (class "Default")
      (node (ref "J2") (pin "117") (pintype "passive"))
      (node (ref "J6") (pin "58") (pintype "passive"))
      (node (ref "U1") (pin "A117") (pinfunction "CAN_H_A117") (pintype "passive"))
    )
    (net (code "241") (name "Net-(U1A-CAN_L)") (class "Default")
      (node (ref "J2") (pin "119") (pintype "passive"))
      (node (ref "J6") (pin "60") (pintype "passive"))
      (node (ref "U1") (pin "A119") (pinfunction "CAN_L_A119") (pintype "passive"))
    )
    (net (code "242") (name "Net-(U1A-CANnode0)") (class "Default")
      (node (ref "J2") (pin "113") (pintype "passive"))
      (node (ref "J6") (pin "54") (pintype "passive"))
      (node (ref "U1") (pin "A113") (pinfunction "CANnode0_A113") (pintype "passive"))
    )
    (net (code "243") (name "Net-(U1A-CANnode1)") (class "Default")
      (node (ref "J2") (pin "115") (pintype "passive"))
      (node (ref "J6") (pin "56") (pintype "passive"))
      (node (ref "U1") (pin "A115") (pinfunction "CANnode1_A115") (pintype "passive"))
    )
    (net (code "244") (name "Net-(U1A-DAC_Out0)") (class "Default")
      (node (ref "J2") (pin "2") (pintype "passive"))
      (node (ref "J5") (pin "60") (pintype "passive"))
      (node (ref "U1") (pin "A2") (pinfunction "DAC_Out0_A2") (pintype "passive"))
    )
    (net (code "245") (name "Net-(U1A-DAC_Out1)") (class "Default")
      (node (ref "J2") (pin "4") (pintype "passive"))
      (node (ref "J5") (pin "58") (pintype "passive"))
      (node (ref "U1") (pin "A4") (pinfunction "DAC_Out1_A4") (pintype "passive"))
    )
    (net (code "246") (name "Net-(U1A-DAC_Out2)") (class "Default")
      (node (ref "J2") (pin "6") (pintype "passive"))
      (node (ref "J5") (pin "56") (pintype "passive"))
      (node (ref "U1") (pin "A6") (pinfunction "DAC_Out2_A6") (pintype "passive"))
    )
    (net (code "247") (name "Net-(U1A-DAC_Out3)") (class "Default")
      (node (ref "J2") (pin "8") (pintype "passive"))
      (node (ref "J5") (pin "54") (pintype "passive"))
      (node (ref "U1") (pin "A8") (pinfunction "DAC_Out3_A8") (pintype "passive"))
    )
    (net (code "248") (name "Net-(U1A-DAC_Out4)") (class "Default")
      (node (ref "J2") (pin "10") (pintype "passive"))
      (node (ref "J5") (pin "52") (pintype "passive"))
      (node (ref "U1") (pin "A10") (pinfunction "DAC_Out4_A10") (pintype "passive"))
    )
    (net (code "249") (name "Net-(U1A-DAC_Out5)") (class "Default")
      (node (ref "J2") (pin "12") (pintype "passive"))
      (node (ref "J5") (pin "50") (pintype "passive"))
      (node (ref "U1") (pin "A12") (pinfunction "DAC_Out5_A12") (pintype "passive"))
    )
    (net (code "250") (name "Net-(U1A-DAC_Out6)") (class "Default")
      (node (ref "J2") (pin "14") (pintype "passive"))
      (node (ref "J5") (pin "48") (pintype "passive"))
      (node (ref "U1") (pin "A14") (pinfunction "DAC_Out6_A14") (pintype "passive"))
    )
    (net (code "251") (name "Net-(U1A-DAC_Out7)") (class "Default")
      (node (ref "J2") (pin "16") (pintype "passive"))
      (node (ref "J5") (pin "46") (pintype "passive"))
      (node (ref "U1") (pin "A16") (pinfunction "DAC_Out7_A16") (pintype "passive"))
    )
    (net (code "252") (name "Net-(U1A-EtherLED100Mbps)") (class "Default")
      (node (ref "J2") (pin "107") (pintype "passive"))
      (node (ref "J6") (pin "48") (pintype "passive"))
      (node (ref "U1") (pin "A107") (pinfunction "EtherLED100Mbps_A107") (pintype "passive"))
    )
    (net (code "253") (name "Net-(U1A-EtherLED_Act)") (class "Default")
      (node (ref "J2") (pin "103") (pintype "passive"))
      (node (ref "J6") (pin "44") (pintype "passive"))
      (node (ref "U1") (pin "A103") (pinfunction "EtherLED_Act_A103") (pintype "passive"))
    )
    (net (code "254") (name "Net-(U1A-EtherLED_FD)") (class "Default")
      (node (ref "J2") (pin "105") (pintype "passive"))
      (node (ref "J6") (pin "46") (pintype "passive"))
      (node (ref "U1") (pin "A105") (pinfunction "EtherLED_FD_A105") (pintype "passive"))
    )
    (net (code "255") (name "Net-(U1A-EtherTx+)") (class "Default")
      (node (ref "J2") (pin "70") (pintype "passive"))
      (node (ref "J6") (pin "9") (pintype "passive"))
      (node (ref "U1") (pin "A70") (pinfunction "EtherTx+_A70") (pintype "passive"))
    )
    (net (code "256") (name "Net-(U1A-EtherTx-)") (class "Default")
      (node (ref "J2") (pin "68") (pintype "passive"))
      (node (ref "J6") (pin "7") (pintype "passive"))
      (node (ref "U1") (pin "A68") (pinfunction "EtherTx-_A68") (pintype "passive"))
    )
    (net (code "257") (name "Net-(U1A-FPGA_TCK)") (class "Default")
      (node (ref "J2") (pin "78") (pintype "passive"))
      (node (ref "J6") (pin "17") (pintype "passive"))
      (node (ref "U1") (pin "A78") (pinfunction "FPGA_TCK_A78") (pintype "passive"))
    )
    (net (code "258") (name "Net-(U1A-FPGA_TMS)") (class "Default")
      (node (ref "J2") (pin "76") (pintype "passive"))
      (node (ref "J6") (pin "15") (pintype "passive"))
      (node (ref "U1") (pin "A76") (pinfunction "FPGA_TMS_A76") (pintype "passive"))
    )
    (net (code "259") (name "Net-(U1A-GP_I{slash}Ospare0)") (class "Default")
      (node (ref "J2") (pin "71") (pintype "passive"))
      (node (ref "J6") (pin "12") (pintype "passive"))
      (node (ref "R13") (pin "1") (pinfunction "1_1") (pintype "passive"))
      (node (ref "U1") (pin "A71") (pinfunction "GP_I/Ospare0_A71") (pintype "passive"))
    )
    (net (code "260") (name "Net-(U1A-GP_I{slash}Ospare1)") (class "Default")
      (node (ref "J2") (pin "73") (pintype "passive"))
      (node (ref "J6") (pin "14") (pintype "passive"))
      (node (ref "R14") (pin "1") (pinfunction "1_1") (pintype "passive"))
      (node (ref "U1") (pin "A73") (pinfunction "GP_I/Ospare1_A73") (pintype "passive"))
    )
    (net (code "261") (name "Net-(U1A-GP_I{slash}Ospare2)") (class "Default")
      (node (ref "J2") (pin "75") (pintype "passive"))
      (node (ref "J6") (pin "16") (pintype "passive"))
      (node (ref "R15") (pin "1") (pinfunction "1_1") (pintype "passive"))
      (node (ref "U1") (pin "A75") (pinfunction "GP_I/Ospare2_A75") (pintype "passive"))
    )
    (net (code "262") (name "Net-(U1A-GP_I{slash}Ospare3)") (class "Default")
      (node (ref "J2") (pin "77") (pintype "passive"))
      (node (ref "J6") (pin "18") (pintype "passive"))
      (node (ref "R16") (pin "1") (pinfunction "1_1") (pintype "passive"))
      (node (ref "U1") (pin "A77") (pinfunction "GP_I/Ospare3_A77") (pintype "passive"))
    )
    (net (code "263") (name "Net-(U1A-GP_I{slash}Ospare4)") (class "Default")
      (node (ref "J2") (pin "79") (pintype "passive"))
      (node (ref "J6") (pin "20") (pintype "passive"))
      (node (ref "R17") (pin "1") (pinfunction "1_1") (pintype "passive"))
      (node (ref "U1") (pin "A79") (pinfunction "GP_I/Ospare4_A79") (pintype "passive"))
    )
    (net (code "264") (name "Net-(U1A-GP_I{slash}Ospare5)") (class "Default")
      (node (ref "J2") (pin "81") (pintype "passive"))
      (node (ref "J6") (pin "22") (pintype "passive"))
      (node (ref "R18") (pin "1") (pinfunction "1_1") (pintype "passive"))
      (node (ref "U1") (pin "A81") (pinfunction "GP_I/Ospare5_A81") (pintype "passive"))
    )
    (net (code "265") (name "Net-(U1A-GP_I{slash}Ospare6)") (class "Default")
      (node (ref "J2") (pin "83") (pintype "passive"))
      (node (ref "J6") (pin "24") (pintype "passive"))
      (node (ref "R19") (pin "1") (pinfunction "1_1") (pintype "passive"))
      (node (ref "U1") (pin "A83") (pinfunction "GP_I/Ospare6_A83") (pintype "passive"))
    )
    (net (code "266") (name "Net-(U1A-GP_I{slash}Ospare7)") (class "Default")
      (node (ref "J2") (pin "85") (pintype "passive"))
      (node (ref "J6") (pin "26") (pintype "passive"))
      (node (ref "R20") (pin "1") (pinfunction "1_1") (pintype "passive"))
      (node (ref "U1") (pin "A85") (pinfunction "GP_I/Ospare7_A85") (pintype "passive"))
    )
    (net (code "267") (name "Net-(U1A-GP_I{slash}Ospare8)") (class "Default")
      (node (ref "J2") (pin "87") (pintype "passive"))
      (node (ref "J6") (pin "28") (pintype "passive"))
      (node (ref "R21") (pin "1") (pinfunction "1_1") (pintype "passive"))
      (node (ref "U1") (pin "A87") (pinfunction "GP_I/Ospare8_A87") (pintype "passive"))
    )
    (net (code "268") (name "Net-(U1A-GP_I{slash}Ospare9)") (class "Default")
      (node (ref "J2") (pin "89") (pintype "passive"))
      (node (ref "J6") (pin "30") (pintype "passive"))
      (node (ref "R22") (pin "1") (pinfunction "1_1") (pintype "passive"))
      (node (ref "U1") (pin "A89") (pinfunction "GP_I/Ospare9_A89") (pintype "passive"))
    )
    (net (code "269") (name "Net-(U1A-GP_I{slash}Ospare10)") (class "Default")
      (node (ref "J2") (pin "91") (pintype "passive"))
      (node (ref "J6") (pin "32") (pintype "passive"))
      (node (ref "R23") (pin "1") (pinfunction "1_1") (pintype "passive"))
      (node (ref "U1") (pin "A91") (pinfunction "GP_I/Ospare10_A91") (pintype "passive"))
    )
    (net (code "270") (name "Net-(U1A-GP_I{slash}Ospare11)") (class "Default")
      (node (ref "J2") (pin "93") (pintype "passive"))
      (node (ref "J6") (pin "34") (pintype "passive"))
      (node (ref "R24") (pin "1") (pinfunction "1_1") (pintype "passive"))
      (node (ref "U1") (pin "A93") (pinfunction "GP_I/Ospare11_A93") (pintype "passive"))
    )
    (net (code "271") (name "Net-(U1A-GP_I{slash}Ospare12)") (class "Default")
      (node (ref "J2") (pin "95") (pintype "passive"))
      (node (ref "J6") (pin "36") (pintype "passive"))
      (node (ref "R25") (pin "1") (pinfunction "1_1") (pintype "passive"))
      (node (ref "U1") (pin "A95") (pinfunction "GP_I/Ospare12_A95") (pintype "passive"))
    )
    (net (code "272") (name "Net-(U1A-GP_I{slash}Ospare13)") (class "Default")
      (node (ref "J2") (pin "97") (pintype "passive"))
      (node (ref "J6") (pin "38") (pintype "passive"))
      (node (ref "R26") (pin "1") (pinfunction "1_1") (pintype "passive"))
      (node (ref "U1") (pin "A97") (pinfunction "GP_I/Ospare13_A97") (pintype "passive"))
    )
    (net (code "273") (name "Net-(U1A-GP_I{slash}Ospare14)") (class "Default")
      (node (ref "J2") (pin "99") (pintype "passive"))
      (node (ref "J6") (pin "40") (pintype "passive"))
      (node (ref "R27") (pin "1") (pinfunction "1_1") (pintype "passive"))
      (node (ref "U1") (pin "A99") (pinfunction "GP_I/Ospare14_A99") (pintype "passive"))
    )
    (net (code "274") (name "Net-(U1A-GP_I{slash}Ospare15)") (class "Default")
      (node (ref "J2") (pin "101") (pintype "passive"))
      (node (ref "J6") (pin "42") (pintype "passive"))
      (node (ref "R28") (pin "1") (pinfunction "1_1") (pintype "passive"))
      (node (ref "U1") (pin "A101") (pinfunction "GP_I/Ospare15_A101") (pintype "passive"))
    )
    (net (code "275") (name "Net-(U1A-I2C_SCL)") (class "Default")
      (node (ref "J2") (pin "111") (pintype "passive"))
      (node (ref "J6") (pin "52") (pintype "passive"))
      (node (ref "U1") (pin "A111") (pinfunction "I2C_SCL_A111") (pintype "passive"))
    )
    (net (code "276") (name "Net-(U1A-I2C_SDA)") (class "Default")
      (node (ref "J2") (pin "109") (pintype "passive"))
      (node (ref "J6") (pin "50") (pintype "passive"))
      (node (ref "U1") (pin "A109") (pinfunction "I2C_SDA_A109") (pintype "passive"))
    )
    (net (code "277") (name "Net-(U1A-Index1+)") (class "Default")
      (node (ref "J2") (pin "26") (pintype "passive"))
      (node (ref "J5") (pin "36") (pintype "passive"))
      (node (ref "R3") (pin "1") (pinfunction "1_1") (pintype "passive"))
      (node (ref "U1") (pin "A26") (pinfunction "Index1+_A26") (pintype "passive"))
    )
    (net (code "278") (name "Net-(U1A-Index2+)") (class "Default")
      (node (ref "J2") (pin "38") (pintype "passive"))
      (node (ref "J5") (pin "24") (pintype "passive"))
      (node (ref "R6") (pin "1") (pinfunction "1_1") (pintype "passive"))
      (node (ref "U1") (pin "A38") (pinfunction "Index2+_A38") (pintype "passive"))
    )
    (net (code "279") (name "Net-(U1A-Index3+)") (class "Default")
      (node (ref "J2") (pin "50") (pintype "passive"))
      (node (ref "J5") (pin "12") (pintype "passive"))
      (node (ref "R9") (pin "1") (pinfunction "1_1") (pintype "passive"))
      (node (ref "U1") (pin "A50") (pinfunction "Index3+_A50") (pintype "passive"))
    )
    (net (code "280") (name "Net-(U1A-Index4+)") (class "Default")
      (node (ref "J2") (pin "62") (pintype "passive"))
      (node (ref "J6") (pin "1") (pintype "passive"))
      (node (ref "R12") (pin "1") (pinfunction "1_1") (pintype "passive"))
      (node (ref "U1") (pin "A62") (pinfunction "Index4+_A62") (pintype "passive"))
    )
    (net (code "281") (name "Net-(U1A-Opto_Input_Com6)") (class "Default")
      (node (ref "J2") (pin "112") (pintype "passive"))
      (node (ref "J6") (pin "51") (pintype "passive"))
      (node (ref "U1") (pin "A112") (pinfunction "Opto_Input_Com6_A112") (pintype "passive"))
    )
    (net (code "282") (name "Net-(U1A-Opto_Out_E0)") (class "Default")
      (node (ref "J2") (pin "82") (pintype "passive"))
      (node (ref "J6") (pin "21") (pintype "passive"))
      (node (ref "U1") (pin "A82") (pinfunction "Opto_Out_E0_A82") (pintype "passive"))
    )
    (net (code "283") (name "Net-(U1A-Opto_Out_E1)") (class "Default")
      (node (ref "J2") (pin "86") (pintype "passive"))
      (node (ref "J6") (pin "25") (pintype "passive"))
      (node (ref "U1") (pin "A86") (pinfunction "Opto_Out_E1_A86") (pintype "passive"))
    )
    (net (code "284") (name "Net-(U1A-Opto_Out_E2)") (class "Default")
      (node (ref "J2") (pin "90") (pintype "passive"))
      (node (ref "J6") (pin "29") (pintype "passive"))
      (node (ref "U1") (pin "A90") (pinfunction "Opto_Out_E2_A90") (pintype "passive"))
    )
    (net (code "285") (name "Net-(U1A-Opto_Out_E3)") (class "Default")
      (node (ref "J2") (pin "94") (pintype "passive"))
      (node (ref "J6") (pin "33") (pintype "passive"))
      (node (ref "U1") (pin "A94") (pinfunction "Opto_Out_E3_A94") (pintype "passive"))
    )
    (net (code "286") (name "Net-(U1A-Opto_Out_E4)") (class "Default")
      (node (ref "J2") (pin "98") (pintype "passive"))
      (node (ref "J6") (pin "37") (pintype "passive"))
      (node (ref "U1") (pin "A98") (pinfunction "Opto_Out_E4_A98") (pintype "passive"))
    )
    (net (code "287") (name "Net-(U1A-Opto_Out_E5)") (class "Default")
      (node (ref "J2") (pin "102") (pintype "passive"))
      (node (ref "J6") (pin "41") (pintype "passive"))
      (node (ref "U1") (pin "A102") (pinfunction "Opto_Out_E5_A102") (pintype "passive"))
    )
    (net (code "288") (name "Net-(U1A-Opto_Out_E6)") (class "Default")
      (node (ref "J2") (pin "106") (pintype "passive"))
      (node (ref "J6") (pin "45") (pintype "passive"))
      (node (ref "U1") (pin "A106") (pinfunction "Opto_Out_E6_A106") (pintype "passive"))
    )
    (net (code "289") (name "Net-(U1A-Opto_Out_E7)") (class "Default")
      (node (ref "J2") (pin "110") (pintype "passive"))
      (node (ref "J6") (pin "49") (pintype "passive"))
      (node (ref "U1") (pin "A110") (pinfunction "Opto_Out_E7_A110") (pintype "passive"))
    )
    (net (code "290") (name "Net-(U1A-QuadA1+)") (class "Default")
      (node (ref "J2") (pin "18") (pintype "passive"))
      (node (ref "J5") (pin "44") (pintype "passive"))
      (node (ref "R1") (pin "1") (pinfunction "1_1") (pintype "passive"))
      (node (ref "U1") (pin "A18") (pinfunction "QuadA1+_A18") (pintype "passive"))
    )
    (net (code "291") (name "Net-(U1A-QuadA2+)") (class "Default")
      (node (ref "J2") (pin "30") (pintype "passive"))
      (node (ref "J5") (pin "32") (pintype "passive"))
      (node (ref "R4") (pin "1") (pinfunction "1_1") (pintype "passive"))
      (node (ref "U1") (pin "A30") (pinfunction "QuadA2+_A30") (pintype "passive"))
    )
    (net (code "292") (name "Net-(U1A-QuadA3+)") (class "Default")
      (node (ref "J2") (pin "42") (pintype "passive"))
      (node (ref "J5") (pin "20") (pintype "passive"))
      (node (ref "R7") (pin "1") (pinfunction "1_1") (pintype "passive"))
      (node (ref "U1") (pin "A42") (pinfunction "QuadA3+_A42") (pintype "passive"))
    )
    (net (code "293") (name "Net-(U1A-QuadA4+)") (class "Default")
      (node (ref "J2") (pin "54") (pintype "passive"))
      (node (ref "J5") (pin "8") (pintype "passive"))
      (node (ref "R10") (pin "1") (pinfunction "1_1") (pintype "passive"))
      (node (ref "U1") (pin "A54") (pinfunction "QuadA4+_A54") (pintype "passive"))
    )
    (net (code "294") (name "Net-(U1A-QuadB1+)") (class "Default")
      (node (ref "J2") (pin "22") (pintype "passive"))
      (node (ref "J5") (pin "40") (pintype "passive"))
      (node (ref "R2") (pin "1") (pinfunction "1_1") (pintype "passive"))
      (node (ref "U1") (pin "A22") (pinfunction "QuadB1+_A22") (pintype "passive"))
    )
    (net (code "295") (name "Net-(U1A-QuadB2+)") (class "Default")
      (node (ref "J2") (pin "34") (pintype "passive"))
      (node (ref "J5") (pin "28") (pintype "passive"))
      (node (ref "R5") (pin "1") (pinfunction "1_1") (pintype "passive"))
      (node (ref "U1") (pin "A34") (pinfunction "QuadB2+_A34") (pintype "passive"))
    )
    (net (code "296") (name "Net-(U1A-QuadB3+)") (class "Default")
      (node (ref "J2") (pin "46") (pintype "passive"))
      (node (ref "J5") (pin "16") (pintype "passive"))
      (node (ref "R8") (pin "1") (pinfunction "1_1") (pintype "passive"))
      (node (ref "U1") (pin "A46") (pinfunction "QuadB3+_A46") (pintype "passive"))
    )
    (net (code "297") (name "Net-(U1A-QuadB4+)") (class "Default")
      (node (ref "J2") (pin "58") (pintype "passive"))
      (node (ref "J5") (pin "4") (pintype "passive"))
      (node (ref "R11") (pin "1") (pinfunction "1_1") (pintype "passive"))
      (node (ref "U1") (pin "A58") (pinfunction "QuadB4+_A58") (pintype "passive"))
    )
    (net (code "298") (name "Net-(U1A-RS485_H)") (class "Default")
      (node (ref "J2") (pin "57") (pintype "passive"))
      (node (ref "J5") (pin "3") (pintype "passive"))
      (node (ref "U1") (pin "A57") (pinfunction "RS485_H_A57") (pintype "passive"))
    )
    (net (code "299") (name "Net-(U1A-RS485_L)") (class "Default")
      (node (ref "J2") (pin "59") (pintype "passive"))
      (node (ref "J5") (pin "1") (pintype "passive"))
      (node (ref "U1") (pin "A59") (pinfunction "RS485_L_A59") (pintype "passive"))
    )
    (net (code "300") (name "Net-(U1A-SPI_MISO)") (class "Default")
      (node (ref "J2") (pin "65") (pintype "passive"))
      (node (ref "J6") (pin "6") (pintype "passive"))
      (node (ref "U1") (pin "A65") (pinfunction "SPI_MISO_A65") (pintype "passive"))
    )
    (net (code "301") (name "Net-(U1A-SPI_MOSI)") (class "Default")
      (node (ref "J2") (pin "63") (pintype "passive"))
      (node (ref "J6") (pin "4") (pintype "passive"))
      (node (ref "U1") (pin "A63") (pinfunction "SPI_MOSI_A63") (pintype "passive"))
    )
    (net (code "302") (name "Net-(U1A-SPI_SClk)") (class "Default")
      (node (ref "J2") (pin "61") (pintype "passive"))
      (node (ref "J6") (pin "2") (pintype "passive"))
      (node (ref "U1") (pin "A61") (pinfunction "SPI_SClk_A61") (pintype "passive"))
    )
    (net (code "303") (name "Net-(U1A-SPI_SS)") (class "Default")
      (node (ref "J2") (pin "67") (pintype "passive"))
      (node (ref "J6") (pin "8") (pintype "passive"))
      (node (ref "U1") (pin "A67") (pinfunction "SPI_SS_A67") (pintype "passive"))
    )
    (net (code "304") (name "Net-(U1A-SPI_SSEL1)") (class "Default")
      (node (ref "J2") (pin "69") (pintype "passive"))
      (node (ref "J6") (pin "10") (pintype "passive"))
      (node (ref "U1") (pin "A69") (pinfunction "SPI_SSEL1_A69") (pintype "passive"))
    )
    (net (code "305") (name "Net-(U1A-TCK)") (class "Default")
      (node (ref "J2") (pin "55") (pintype "passive"))
      (node (ref "J5") (pin "5") (pintype "passive"))
      (node (ref "U1") (pin "A55") (pinfunction "TCK_A55") (pintype "passive"))
    )
    (net (code "306") (name "Net-(U1A-TDI)") (class "Default")
      (node (ref "J2") (pin "49") (pintype "passive"))
      (node (ref "J5") (pin "11") (pintype "passive"))
      (node (ref "U1") (pin "A49") (pinfunction "TDI_A49") (pintype "passive"))
    )
    (net (code "307") (name "Net-(U1A-TDO)") (class "Default")
      (node (ref "J2") (pin "53") (pintype "passive"))
      (node (ref "J5") (pin "7") (pintype "passive"))
      (node (ref "U1") (pin "A53") (pinfunction "TDO_A53") (pintype "passive"))
    )
    (net (code "308") (name "Net-(U1A-TDO-App_TDI)") (class "Default")
      (node (ref "J2") (pin "72") (pintype "passive"))
      (node (ref "J6") (pin "11") (pintype "passive"))
      (node (ref "U1") (pin "A72") (pinfunction "TDO-App_TDI_A72") (pintype "passive"))
    )
    (net (code "309") (name "Net-(U1A-TMS)") (class "Default")
      (node (ref "J2") (pin "51") (pintype "passive"))
      (node (ref "J5") (pin "9") (pintype "passive"))
      (node (ref "U1") (pin "A51") (pinfunction "TMS_A51") (pintype "passive"))
    )
    (net (code "310") (name "Net-(U1A-USB_D+)") (class "Default")
      (node (ref "J2") (pin "35") (pintype "passive"))
      (node (ref "J5") (pin "25") (pintype "passive"))
      (node (ref "U1") (pin "A35") (pinfunction "USB_D+_A35") (pintype "passive"))
    )
    (net (code "311") (name "Net-(U1A-USB_D-)") (class "Default")
      (node (ref "J2") (pin "33") (pintype "passive"))
      (node (ref "J5") (pin "27") (pintype "passive"))
      (node (ref "U1") (pin "A33") (pinfunction "USB_D-_A33") (pintype "passive"))
    )
    (net (code "312") (name "Net-(U1A-USB_VBUS)") (class "Default")
      (node (ref "J2") (pin "31") (pintype "passive"))
      (node (ref "J5") (pin "29") (pintype "passive"))
      (node (ref "U1") (pin "A31") (pinfunction "USB_VBUS_A31") (pintype "passive"))
    )
    (net (code "313") (name "Net-(U1A-VA25)") (class "Default")
      (node (ref "J2") (pin "66") (pintype "passive"))
      (node (ref "J6") (pin "5") (pintype "passive"))
      (node (ref "U1") (pin "A66") (pinfunction "VA25_A66") (pintype "passive"))
    )
    (net (code "314") (name "Net-(U1A-nEMU)") (class "Default")
      (node (ref "J2") (pin "47") (pintype "passive"))
      (node (ref "J5") (pin "13") (pintype "passive"))
      (node (ref "U1") (pin "A47") (pinfunction "nEMU_A47") (pintype "passive"))
    )
    (net (code "315") (name "Net-(U1A-nTRST)") (class "Default")
      (node (ref "J2") (pin "45") (pintype "passive"))
      (node (ref "J5") (pin "15") (pintype "passive"))
      (node (ref "U1") (pin "A45") (pinfunction "nTRST_A45") (pintype "passive"))
    )
    (net (code "316") (name "Net-(U1B-EtherGND)") (class "Default")
      (node (ref "J3") (pin "69") (pintype "passive"))
      (node (ref "J4") (pin "9") (pintype "passive"))
      (node (ref "U1") (pin "B69") (pinfunction "EtherGND_B69") (pintype "passive"))
    )
    (net (code "317") (name "Net-(U1B-EtherRx+)") (class "Default")
      (node (ref "J3") (pin "67") (pintype "passive"))
      (node (ref "J4") (pin "7") (pintype "passive"))
      (node (ref "U1") (pin "B67") (pinfunction "EtherRx+_B67") (pintype "passive"))
    )
    (net (code "318") (name "Net-(U1B-EtherRx-)") (class "Default")
      (node (ref "J3") (pin "65") (pintype "passive"))
      (node (ref "J4") (pin "5") (pintype "passive"))
      (node (ref "U1") (pin "B65") (pinfunction "EtherRx-_B65") (pintype "passive"))
    )
    (net (code "319") (name "Net-(U1B-GP_Out_S0)") (class "Default")
      (node (ref "J1") (pin "12") (pintype "passive"))
      (node (ref "J3") (pin "49") (pintype "passive"))
      (node (ref "U1") (pin "B49") (pinfunction "GP_Out_S0_B49") (pintype "passive"))
    )
    (net (code "320") (name "Net-(U1B-GP_Out_S1)") (class "Default")
      (node (ref "J1") (pin "8") (pintype "passive"))
      (node (ref "J3") (pin "53") (pintype "passive"))
      (node (ref "U1") (pin "B53") (pinfunction "GP_Out_S1_B53") (pintype "passive"))
    )
    (net (code "321") (name "Net-(U1B-GP_Out_S2)") (class "Default")
      (node (ref "J1") (pin "57") (pintype "passive"))
      (node (ref "J3") (pin "4") (pintype "passive"))
      (node (ref "U1") (pin "B4") (pinfunction "GP_Out_S2_B4") (pintype "passive"))
    )
    (net (code "322") (name "Net-(U1B-GP_Out_S3)") (class "Default")
      (node (ref "J1") (pin "53") (pintype "passive"))
      (node (ref "J3") (pin "8") (pintype "passive"))
      (node (ref "U1") (pin "B8") (pinfunction "GP_Out_S3_B8") (pintype "passive"))
    )
    (net (code "323") (name "Net-(U1B-GP_Out_S4)") (class "Default")
      (node (ref "J1") (pin "49") (pintype "passive"))
      (node (ref "J3") (pin "12") (pintype "passive"))
      (node (ref "U1") (pin "B12") (pinfunction "GP_Out_S4_B12") (pintype "passive"))
    )
    (net (code "324") (name "Net-(U1B-GP_Out_S5)") (class "Default")
      (node (ref "J1") (pin "45") (pintype "passive"))
      (node (ref "J3") (pin "16") (pintype "passive"))
      (node (ref "U1") (pin "B16") (pinfunction "GP_Out_S5_B16") (pintype "passive"))
    )
    (net (code "325") (name "Net-(U1B-GP_Out_S6)") (class "Default")
      (node (ref "J1") (pin "41") (pintype "passive"))
      (node (ref "J3") (pin "20") (pintype "passive"))
      (node (ref "U1") (pin "B20") (pinfunction "GP_Out_S6_B20") (pintype "passive"))
    )
    (net (code "326") (name "Net-(U1B-GP_Out_S7)") (class "Default")
      (node (ref "J1") (pin "37") (pintype "passive"))
      (node (ref "J3") (pin "24") (pintype "passive"))
      (node (ref "U1") (pin "B24") (pinfunction "GP_Out_S7_B24") (pintype "passive"))
    )
    (net (code "327") (name "Net-(U1B-GP_Out_S8)") (class "Default")
      (node (ref "J1") (pin "33") (pintype "passive"))
      (node (ref "J3") (pin "28") (pintype "passive"))
      (node (ref "U1") (pin "B28") (pinfunction "GP_Out_S8_B28") (pintype "passive"))
    )
    (net (code "328") (name "Net-(U1B-GP_Out_S9)") (class "Default")
      (node (ref "J1") (pin "29") (pintype "passive"))
      (node (ref "J3") (pin "32") (pintype "passive"))
      (node (ref "U1") (pin "B32") (pinfunction "GP_Out_S9_B32") (pintype "passive"))
    )
    (net (code "329") (name "Net-(U1B-GP_Out_S10)") (class "Default")
      (node (ref "J1") (pin "25") (pintype "passive"))
      (node (ref "J3") (pin "36") (pintype "passive"))
      (node (ref "U1") (pin "B36") (pinfunction "GP_Out_S10_B36") (pintype "passive"))
    )
    (net (code "330") (name "Net-(U1B-GP_Out_S11)") (class "Default")
      (node (ref "J1") (pin "21") (pintype "passive"))
      (node (ref "J3") (pin "40") (pintype "passive"))
      (node (ref "U1") (pin "B40") (pinfunction "GP_Out_S11_B40") (pintype "passive"))
    )
    (net (code "331") (name "Net-(U1B-GP_Out_S12)") (class "Default")
      (node (ref "J1") (pin "17") (pintype "passive"))
      (node (ref "J3") (pin "44") (pintype "passive"))
      (node (ref "U1") (pin "B44") (pinfunction "GP_Out_S12_B44") (pintype "passive"))
    )
    (net (code "332") (name "Net-(U1B-GP_Out_S13)") (class "Default")
      (node (ref "J1") (pin "13") (pintype "passive"))
      (node (ref "J3") (pin "48") (pintype "passive"))
      (node (ref "U1") (pin "B48") (pinfunction "GP_Out_S13_B48") (pintype "passive"))
    )
    (net (code "333") (name "Net-(U1B-GP_Out_S14)") (class "Default")
      (node (ref "J1") (pin "9") (pintype "passive"))
      (node (ref "J3") (pin "52") (pintype "passive"))
      (node (ref "U1") (pin "B52") (pinfunction "GP_Out_S14_B52") (pintype "passive"))
    )
    (net (code "334") (name "Net-(U1B-GP_Out_S15)") (class "Default")
      (node (ref "J1") (pin "5") (pintype "passive"))
      (node (ref "J3") (pin "56") (pintype "passive"))
      (node (ref "U1") (pin "B56") (pinfunction "GP_Out_S15_B56") (pintype "passive"))
    )
    (net (code "335") (name "Net-(U1B-GP_Out_S16)") (class "Default")
      (node (ref "J1") (pin "1") (pintype "passive"))
      (node (ref "J3") (pin "60") (pintype "passive"))
      (node (ref "U1") (pin "B60") (pinfunction "GP_Out_S16_B60") (pintype "passive"))
    )
    (net (code "336") (name "Net-(U1B-GP_Out_S17)") (class "Default")
      (node (ref "J3") (pin "64") (pintype "passive"))
      (node (ref "J4") (pin "4") (pintype "passive"))
      (node (ref "U1") (pin "B64") (pinfunction "GP_Out_S17_B64") (pintype "passive"))
    )
    (net (code "337") (name "Net-(U1B-GP_Out_S18)") (class "Default")
      (node (ref "J3") (pin "68") (pintype "passive"))
      (node (ref "J4") (pin "8") (pintype "passive"))
      (node (ref "U1") (pin "B68") (pinfunction "GP_Out_S18_B68") (pintype "passive"))
    )
    (net (code "338") (name "Net-(U1B-GP_Out_S19)") (class "Default")
      (node (ref "J3") (pin "72") (pintype "passive"))
      (node (ref "J4") (pin "12") (pintype "passive"))
      (node (ref "U1") (pin "B72") (pinfunction "GP_Out_S19_B72") (pintype "passive"))
    )
    (net (code "339") (name "Net-(U1B-GP_Out_S20)") (class "Default")
      (node (ref "J3") (pin "76") (pintype "passive"))
      (node (ref "J4") (pin "16") (pintype "passive"))
      (node (ref "U1") (pin "B76") (pinfunction "GP_Out_S20_B76") (pintype "passive"))
    )
    (net (code "340") (name "Net-(U1B-GP_Out_S21)") (class "Default")
      (node (ref "J3") (pin "80") (pintype "passive"))
      (node (ref "J4") (pin "20") (pintype "passive"))
      (node (ref "U1") (pin "B80") (pinfunction "GP_Out_S21_B80") (pintype "passive"))
    )
    (net (code "341") (name "Net-(U1B-GP_Out_S22)") (class "Default")
      (node (ref "J3") (pin "84") (pintype "passive"))
      (node (ref "J4") (pin "24") (pintype "passive"))
      (node (ref "U1") (pin "B84") (pinfunction "GP_Out_S22_B84") (pintype "passive"))
    )
    (net (code "342") (name "Net-(U1B-GP_Out_S23)") (class "Default")
      (node (ref "J3") (pin "88") (pintype "passive"))
      (node (ref "J4") (pin "28") (pintype "passive"))
      (node (ref "U1") (pin "B88") (pinfunction "GP_Out_S23_B88") (pintype "passive"))
    )
    (net (code "343") (name "Net-(U1B-GP_Out_S24)") (class "Default")
      (node (ref "J3") (pin "92") (pintype "passive"))
      (node (ref "J4") (pin "32") (pintype "passive"))
      (node (ref "U1") (pin "B92") (pinfunction "GP_Out_S24_B92") (pintype "passive"))
    )
    (net (code "344") (name "Net-(U1B-GP_Out_S25)") (class "Default")
      (node (ref "J3") (pin "96") (pintype "passive"))
      (node (ref "J4") (pin "36") (pintype "passive"))
      (node (ref "U1") (pin "B96") (pinfunction "GP_Out_S25_B96") (pintype "passive"))
    )
    (net (code "345") (name "Net-(U1B-GP_Out_S26)") (class "Default")
      (node (ref "J3") (pin "100") (pintype "passive"))
      (node (ref "J4") (pin "40") (pintype "passive"))
      (node (ref "U1") (pin "B100") (pinfunction "GP_Out_S26_B100") (pintype "passive"))
    )
    (net (code "346") (name "Net-(U1B-GP_Out_S27)") (class "Default")
      (node (ref "J3") (pin "104") (pintype "passive"))
      (node (ref "J4") (pin "44") (pintype "passive"))
      (node (ref "U1") (pin "B104") (pinfunction "GP_Out_S27_B104") (pintype "passive"))
    )
    (net (code "347") (name "Net-(U1B-GP_Out_S28)") (class "Default")
      (node (ref "J3") (pin "108") (pintype "passive"))
      (node (ref "J4") (pin "48") (pintype "passive"))
      (node (ref "U1") (pin "B108") (pinfunction "GP_Out_S28_B108") (pintype "passive"))
    )
    (net (code "348") (name "Net-(U1B-GP_Out_S29)") (class "Default")
      (node (ref "J3") (pin "112") (pintype "passive"))
      (node (ref "J4") (pin "52") (pintype "passive"))
      (node (ref "U1") (pin "B112") (pinfunction "GP_Out_S29_B112") (pintype "passive"))
    )
    (net (code "349") (name "Net-(U1B-GP_Out_S30)") (class "Default")
      (node (ref "J3") (pin "116") (pintype "passive"))
      (node (ref "J4") (pin "56") (pintype "passive"))
      (node (ref "U1") (pin "B116") (pinfunction "GP_Out_S30_B116") (pintype "passive"))
    )
    (net (code "350") (name "Net-(U1B-GP_Out_S31)") (class "Default")
      (node (ref "J3") (pin "120") (pintype "passive"))
      (node (ref "J4") (pin "60") (pintype "passive"))
      (node (ref "U1") (pin "B120") (pinfunction "GP_Out_S31_B120") (pintype "passive"))
    )
    (net (code "351") (name "Net-(U1B-HomeCom)") (class "Default")
      (node (ref "J1") (pin "52") (pintype "passive"))
      (node (ref "J3") (pin "9") (pintype "passive"))
      (node (ref "U1") (pin "B9") (pinfunction "HomeCom_B9") (pintype "passive"))
    )
    (net (code "352") (name "Net-(U1B-NegLimtCom)") (class "Default")
      (node (ref "J1") (pin "32") (pintype "passive"))
      (node (ref "J3") (pin "29") (pintype "passive"))
      (node (ref "U1") (pin "B29") (pinfunction "NegLimtCom_B29") (pintype "passive"))
    )
    (net (code "353") (name "Net-(U1B-Opto_Input_Com0)") (class "Default")
      (node (ref "J1") (pin "6") (pintype "passive"))
      (node (ref "J3") (pin "55") (pintype "passive"))
      (node (ref "U1") (pin "B55") (pinfunction "Opto_Input_Com0_B55") (pintype "passive"))
    )
    (net (code "354") (name "Net-(U1B-Opto_Input_Com1)") (class "Default")
      (node (ref "J3") (pin "71") (pintype "passive"))
      (node (ref "J4") (pin "11") (pintype "passive"))
      (node (ref "U1") (pin "B71") (pinfunction "Opto_Input_Com1_B71") (pintype "passive"))
    )
    (net (code "355") (name "Net-(U1B-Opto_Input_Com2)") (class "Default")
      (node (ref "J3") (pin "81") (pintype "passive"))
      (node (ref "J4") (pin "21") (pintype "passive"))
      (node (ref "U1") (pin "B81") (pinfunction "Opto_Input_Com2_B81") (pintype "passive"))
    )
    (net (code "356") (name "Net-(U1B-Opto_Input_Com3)") (class "Default")
      (node (ref "J3") (pin "91") (pintype "passive"))
      (node (ref "J4") (pin "31") (pintype "passive"))
      (node (ref "U1") (pin "B91") (pinfunction "Opto_Input_Com3_B91") (pintype "passive"))
    )
    (net (code "357") (name "Net-(U1B-Opto_Input_Com4)") (class "Default")
      (node (ref "J3") (pin "101") (pintype "passive"))
      (node (ref "J4") (pin "41") (pintype "passive"))
      (node (ref "U1") (pin "B101") (pinfunction "Opto_Input_Com4_B101") (pintype "passive"))
    )
    (net (code "358") (name "Net-(U1B-Opto_Input_Com5)") (class "Default")
      (node (ref "J3") (pin "111") (pintype "passive"))
      (node (ref "J4") (pin "51") (pintype "passive"))
      (node (ref "U1") (pin "B111") (pinfunction "Opto_Input_Com5_B111") (pintype "passive"))
    )
    (net (code "359") (name "Net-(U1B-PosLimtCom)") (class "Default")
      (node (ref "J1") (pin "42") (pintype "passive"))
      (node (ref "J3") (pin "19") (pintype "passive"))
      (node (ref "U1") (pin "B19") (pinfunction "PosLimtCom_B19") (pintype "passive"))
    )
  )
)
